# Mainboard.net
KiCad netlist of a schematic drawn in EAGLE
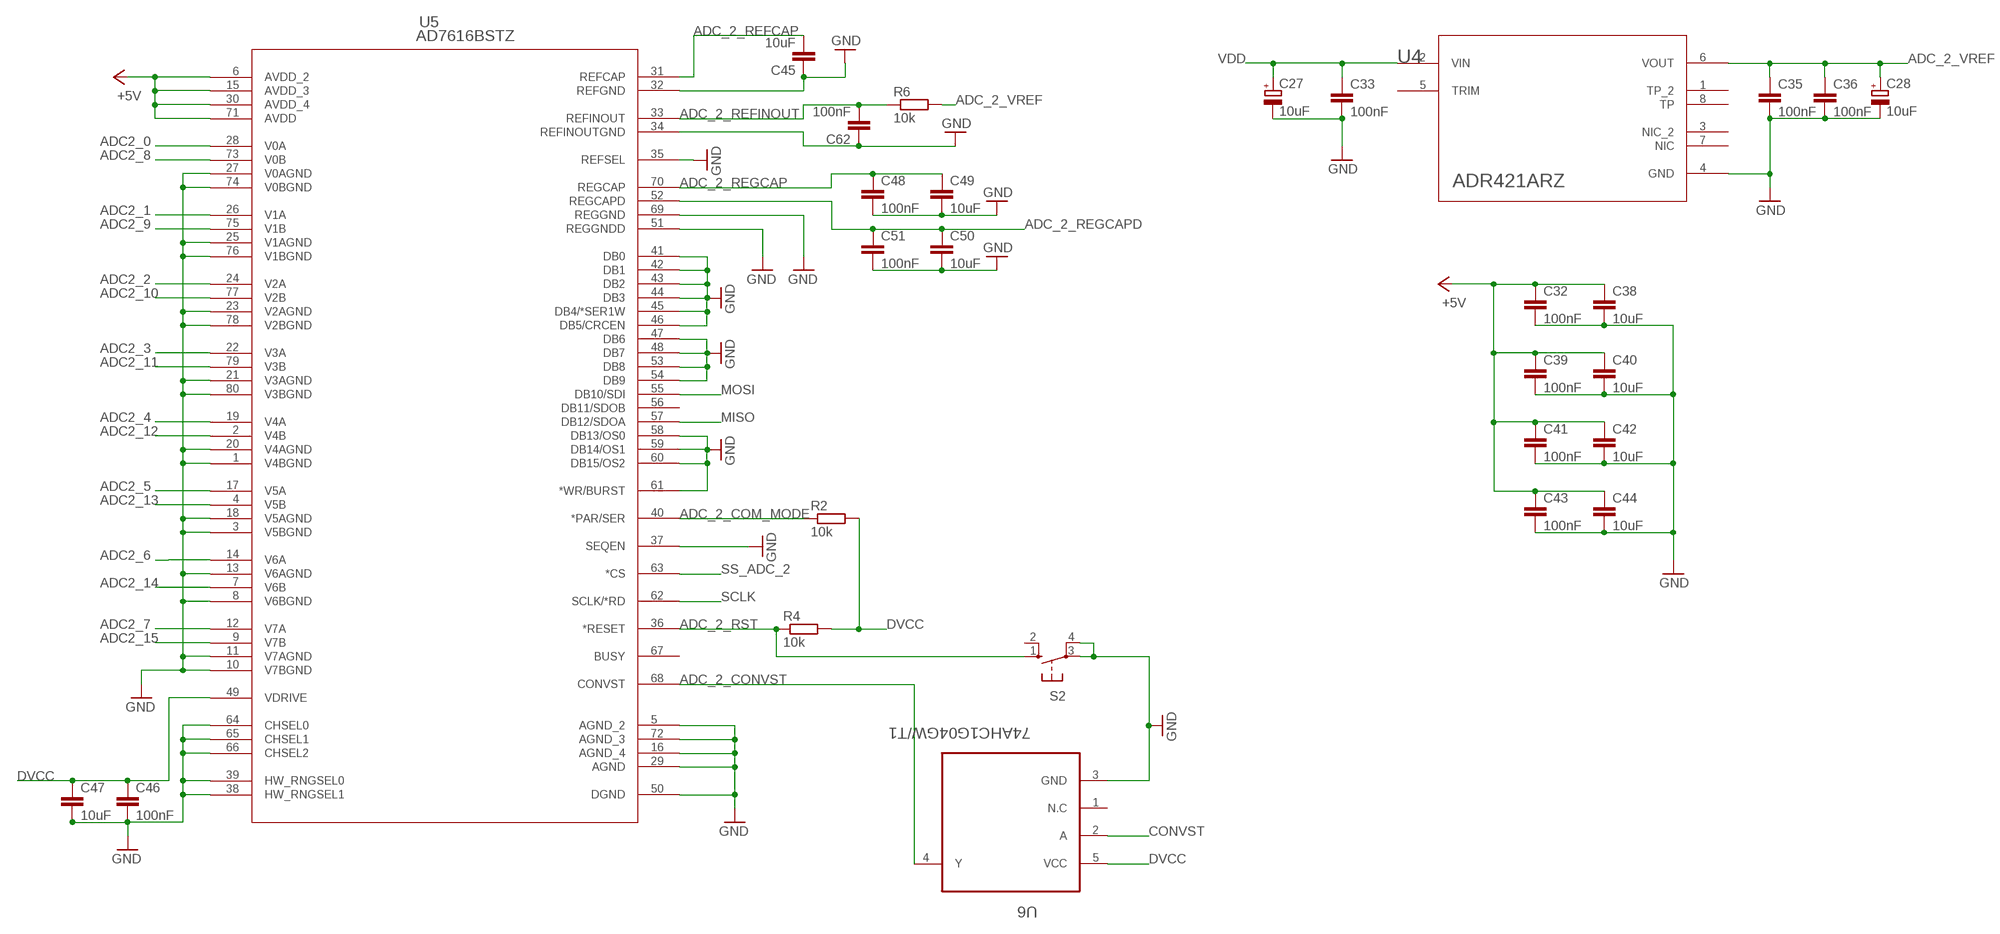
[diagram p0: schematic, sheet 1, part 1 of 2]
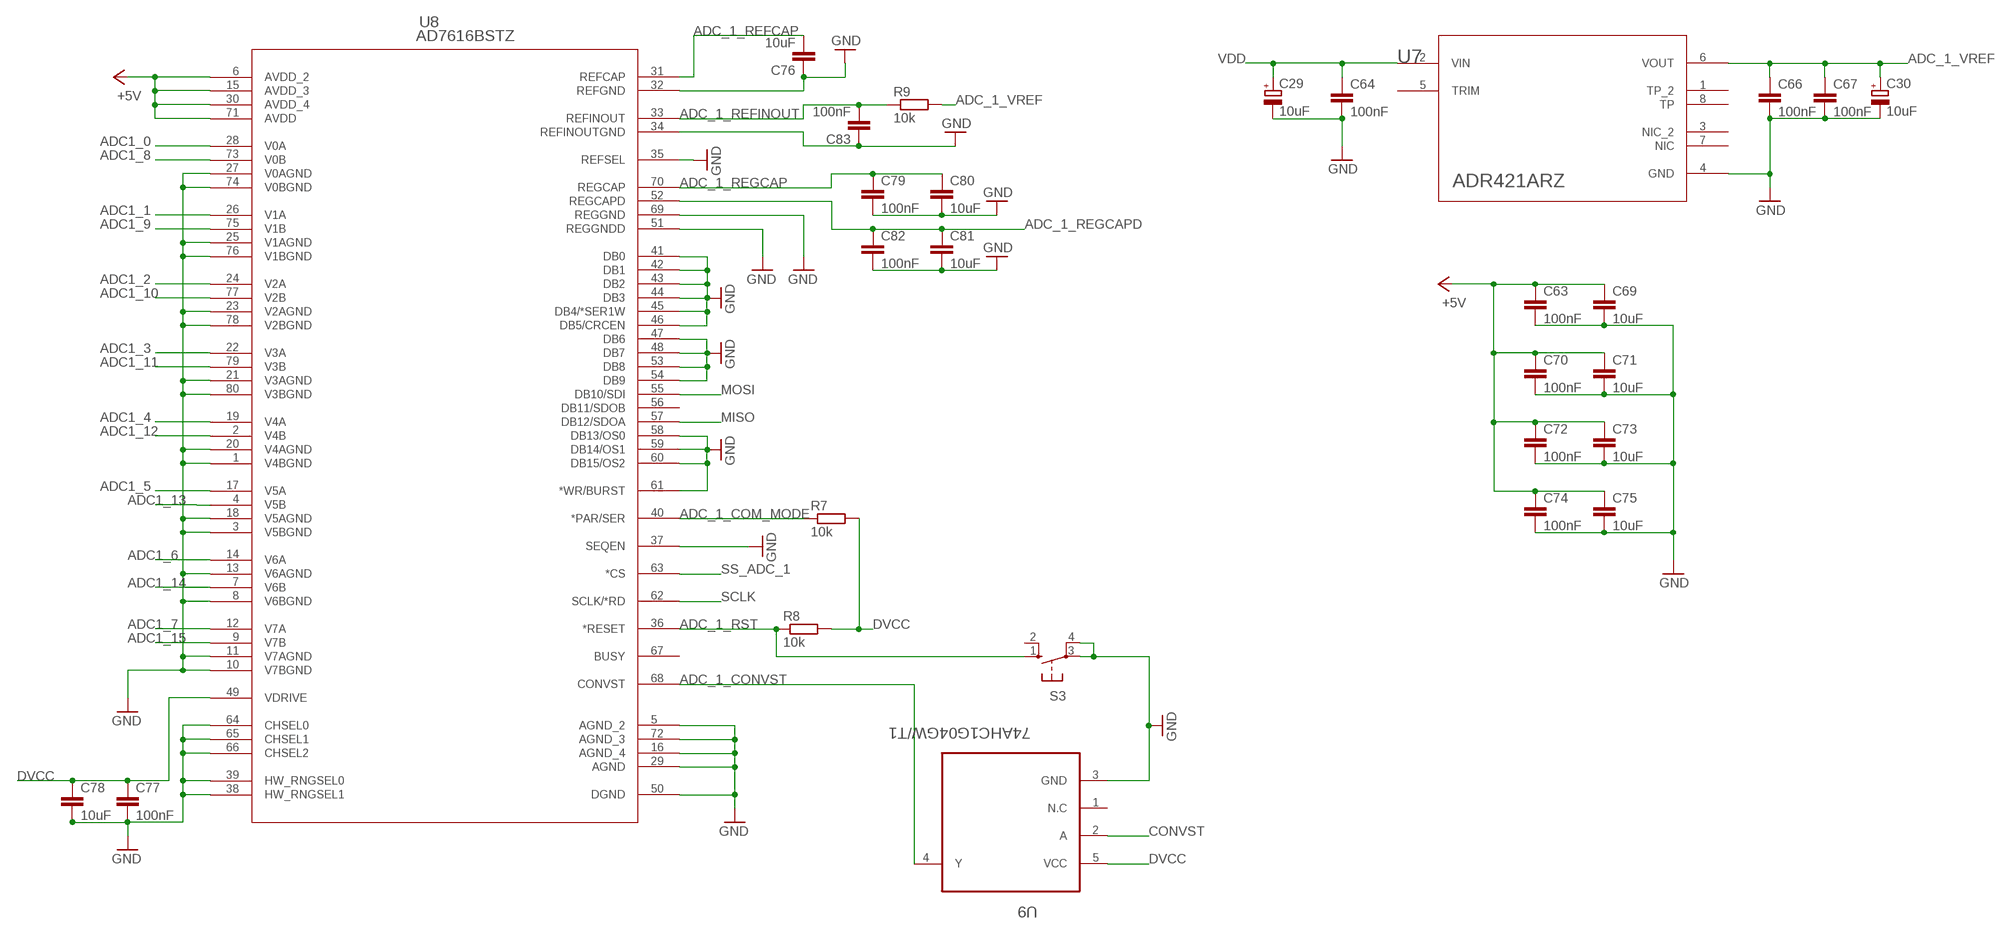
[diagram p1: schematic, sheet 1, part 2 of 2]
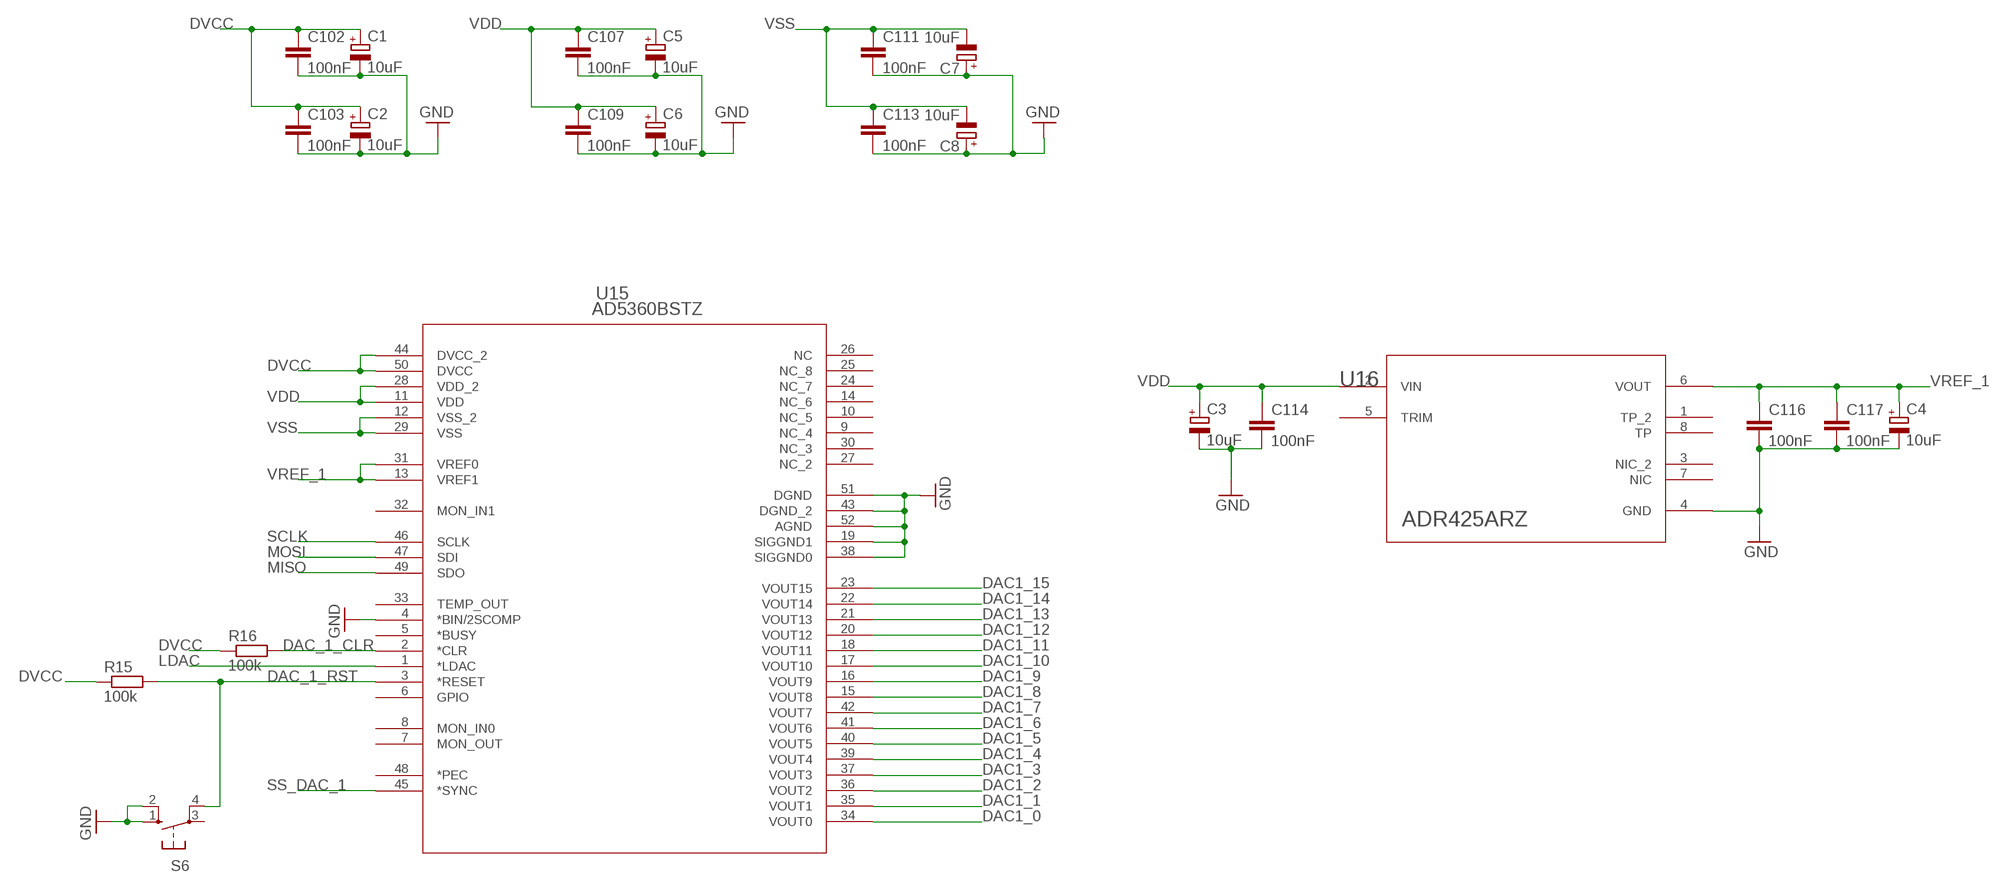
[diagram p2: schematic, sheet 2, part 1 of 2]
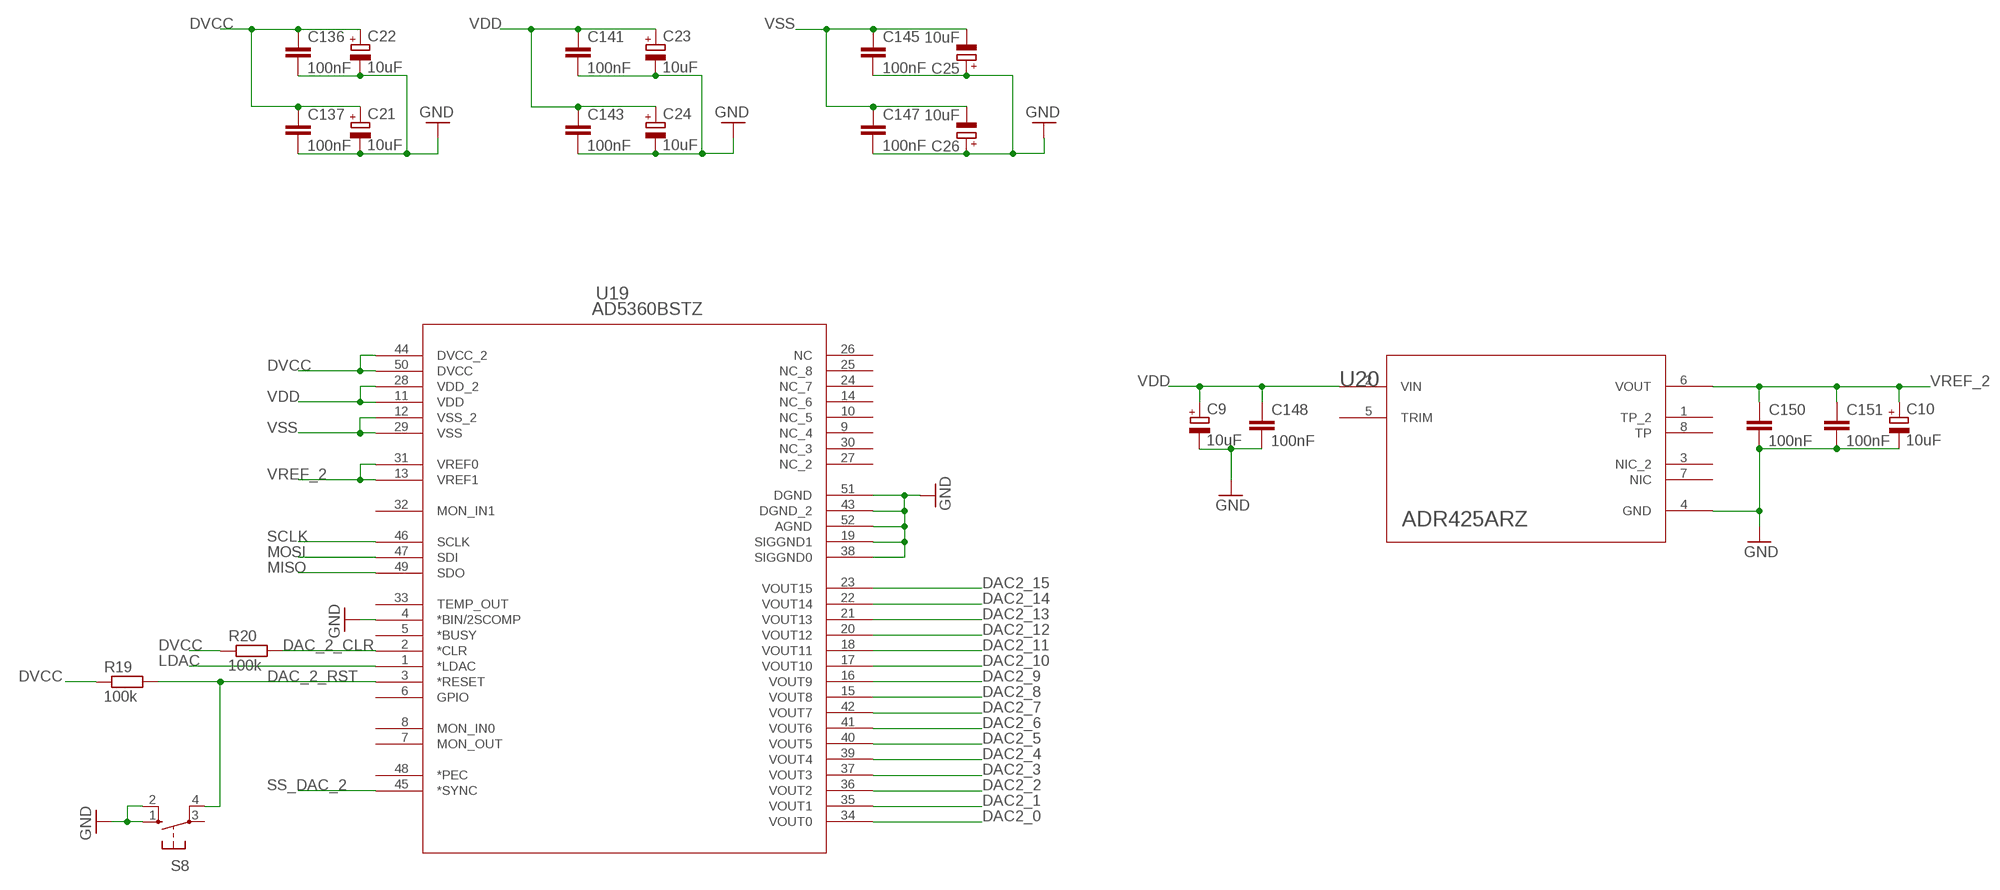
[diagram p3: schematic, sheet 2, part 2 of 2]
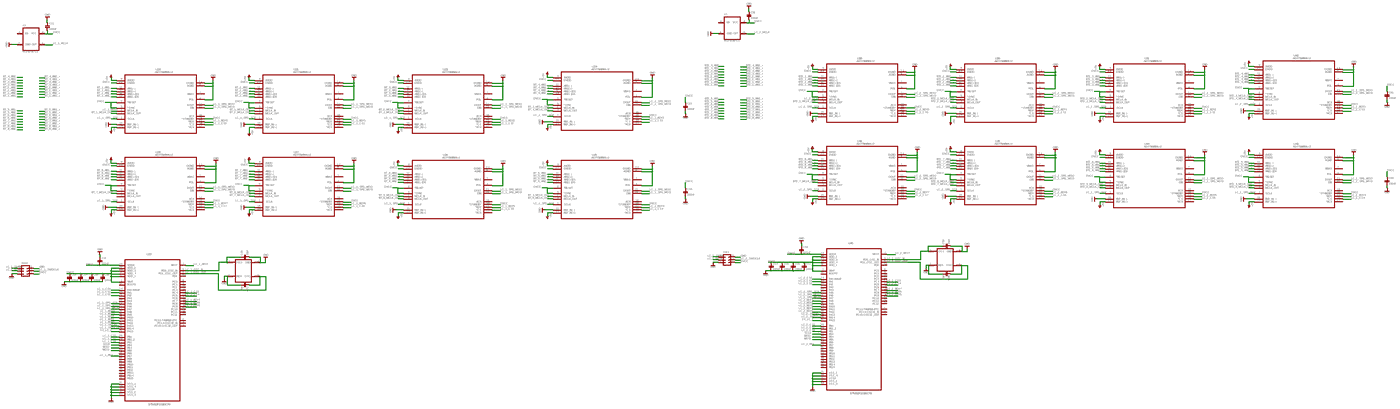
[diagram p4: schematic, sheet 3, overview]
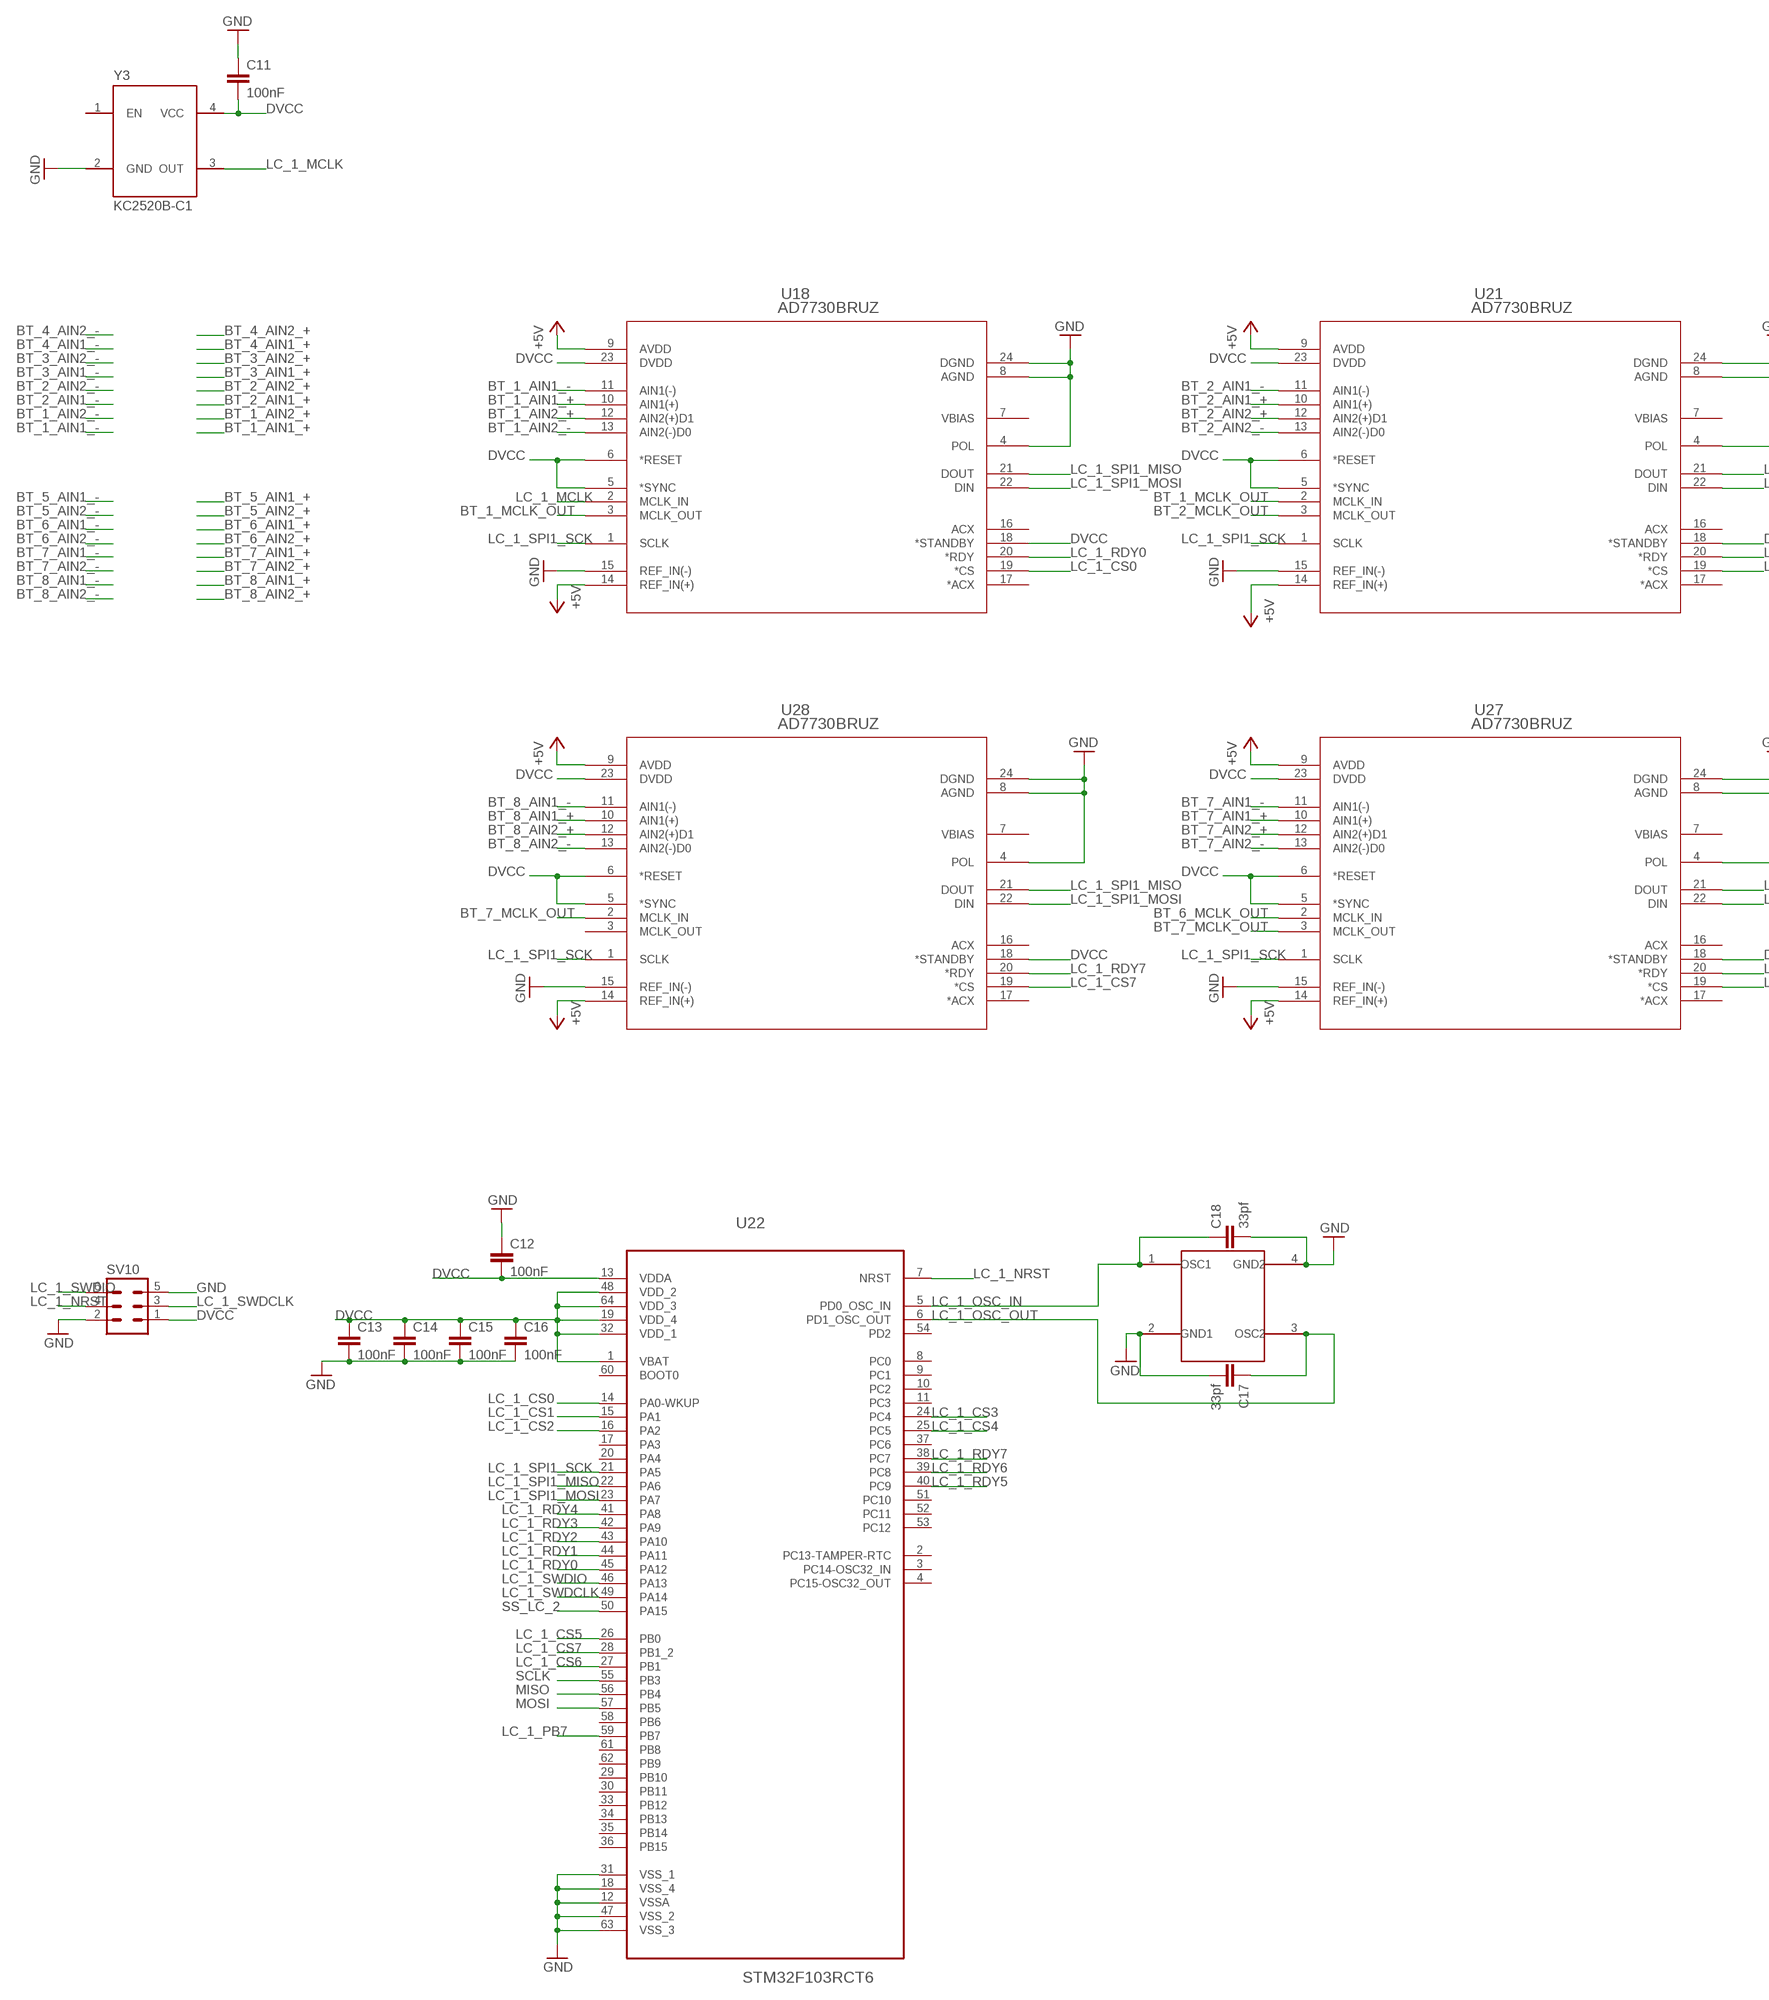
[diagram p5: schematic, sheet 3, part 1 of 4]
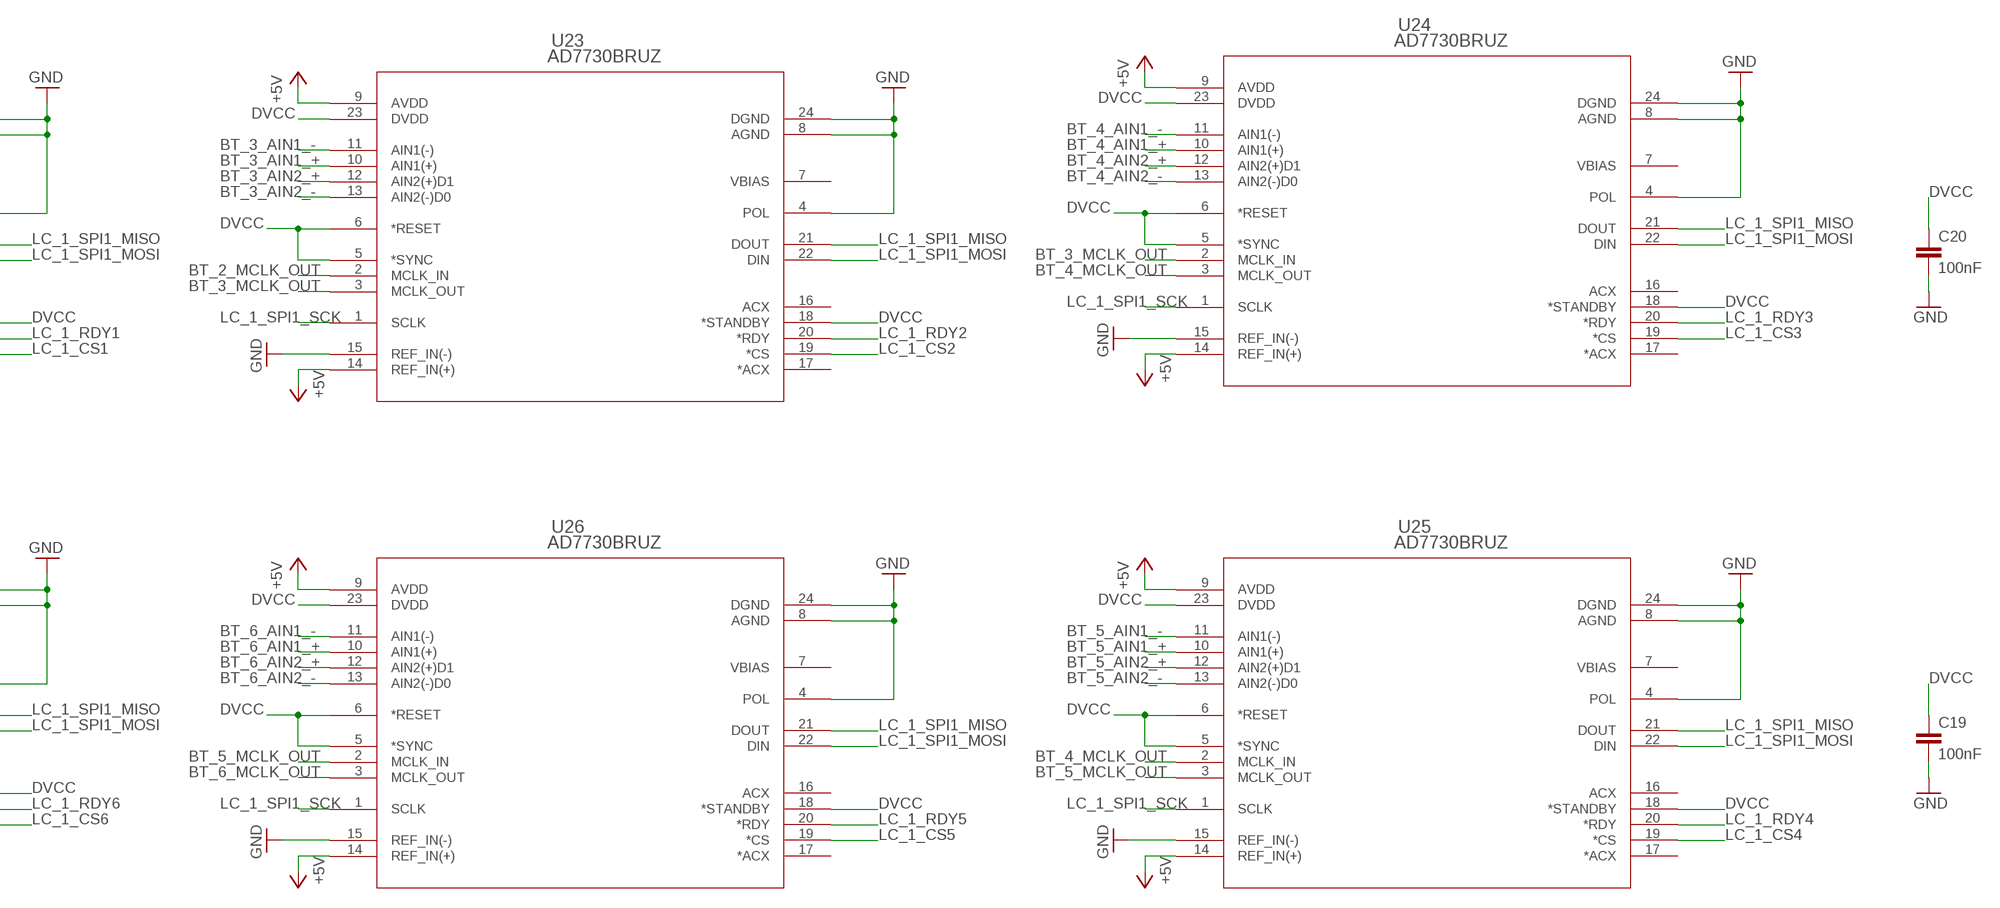
[diagram p6: schematic, sheet 3, part 2 of 4]
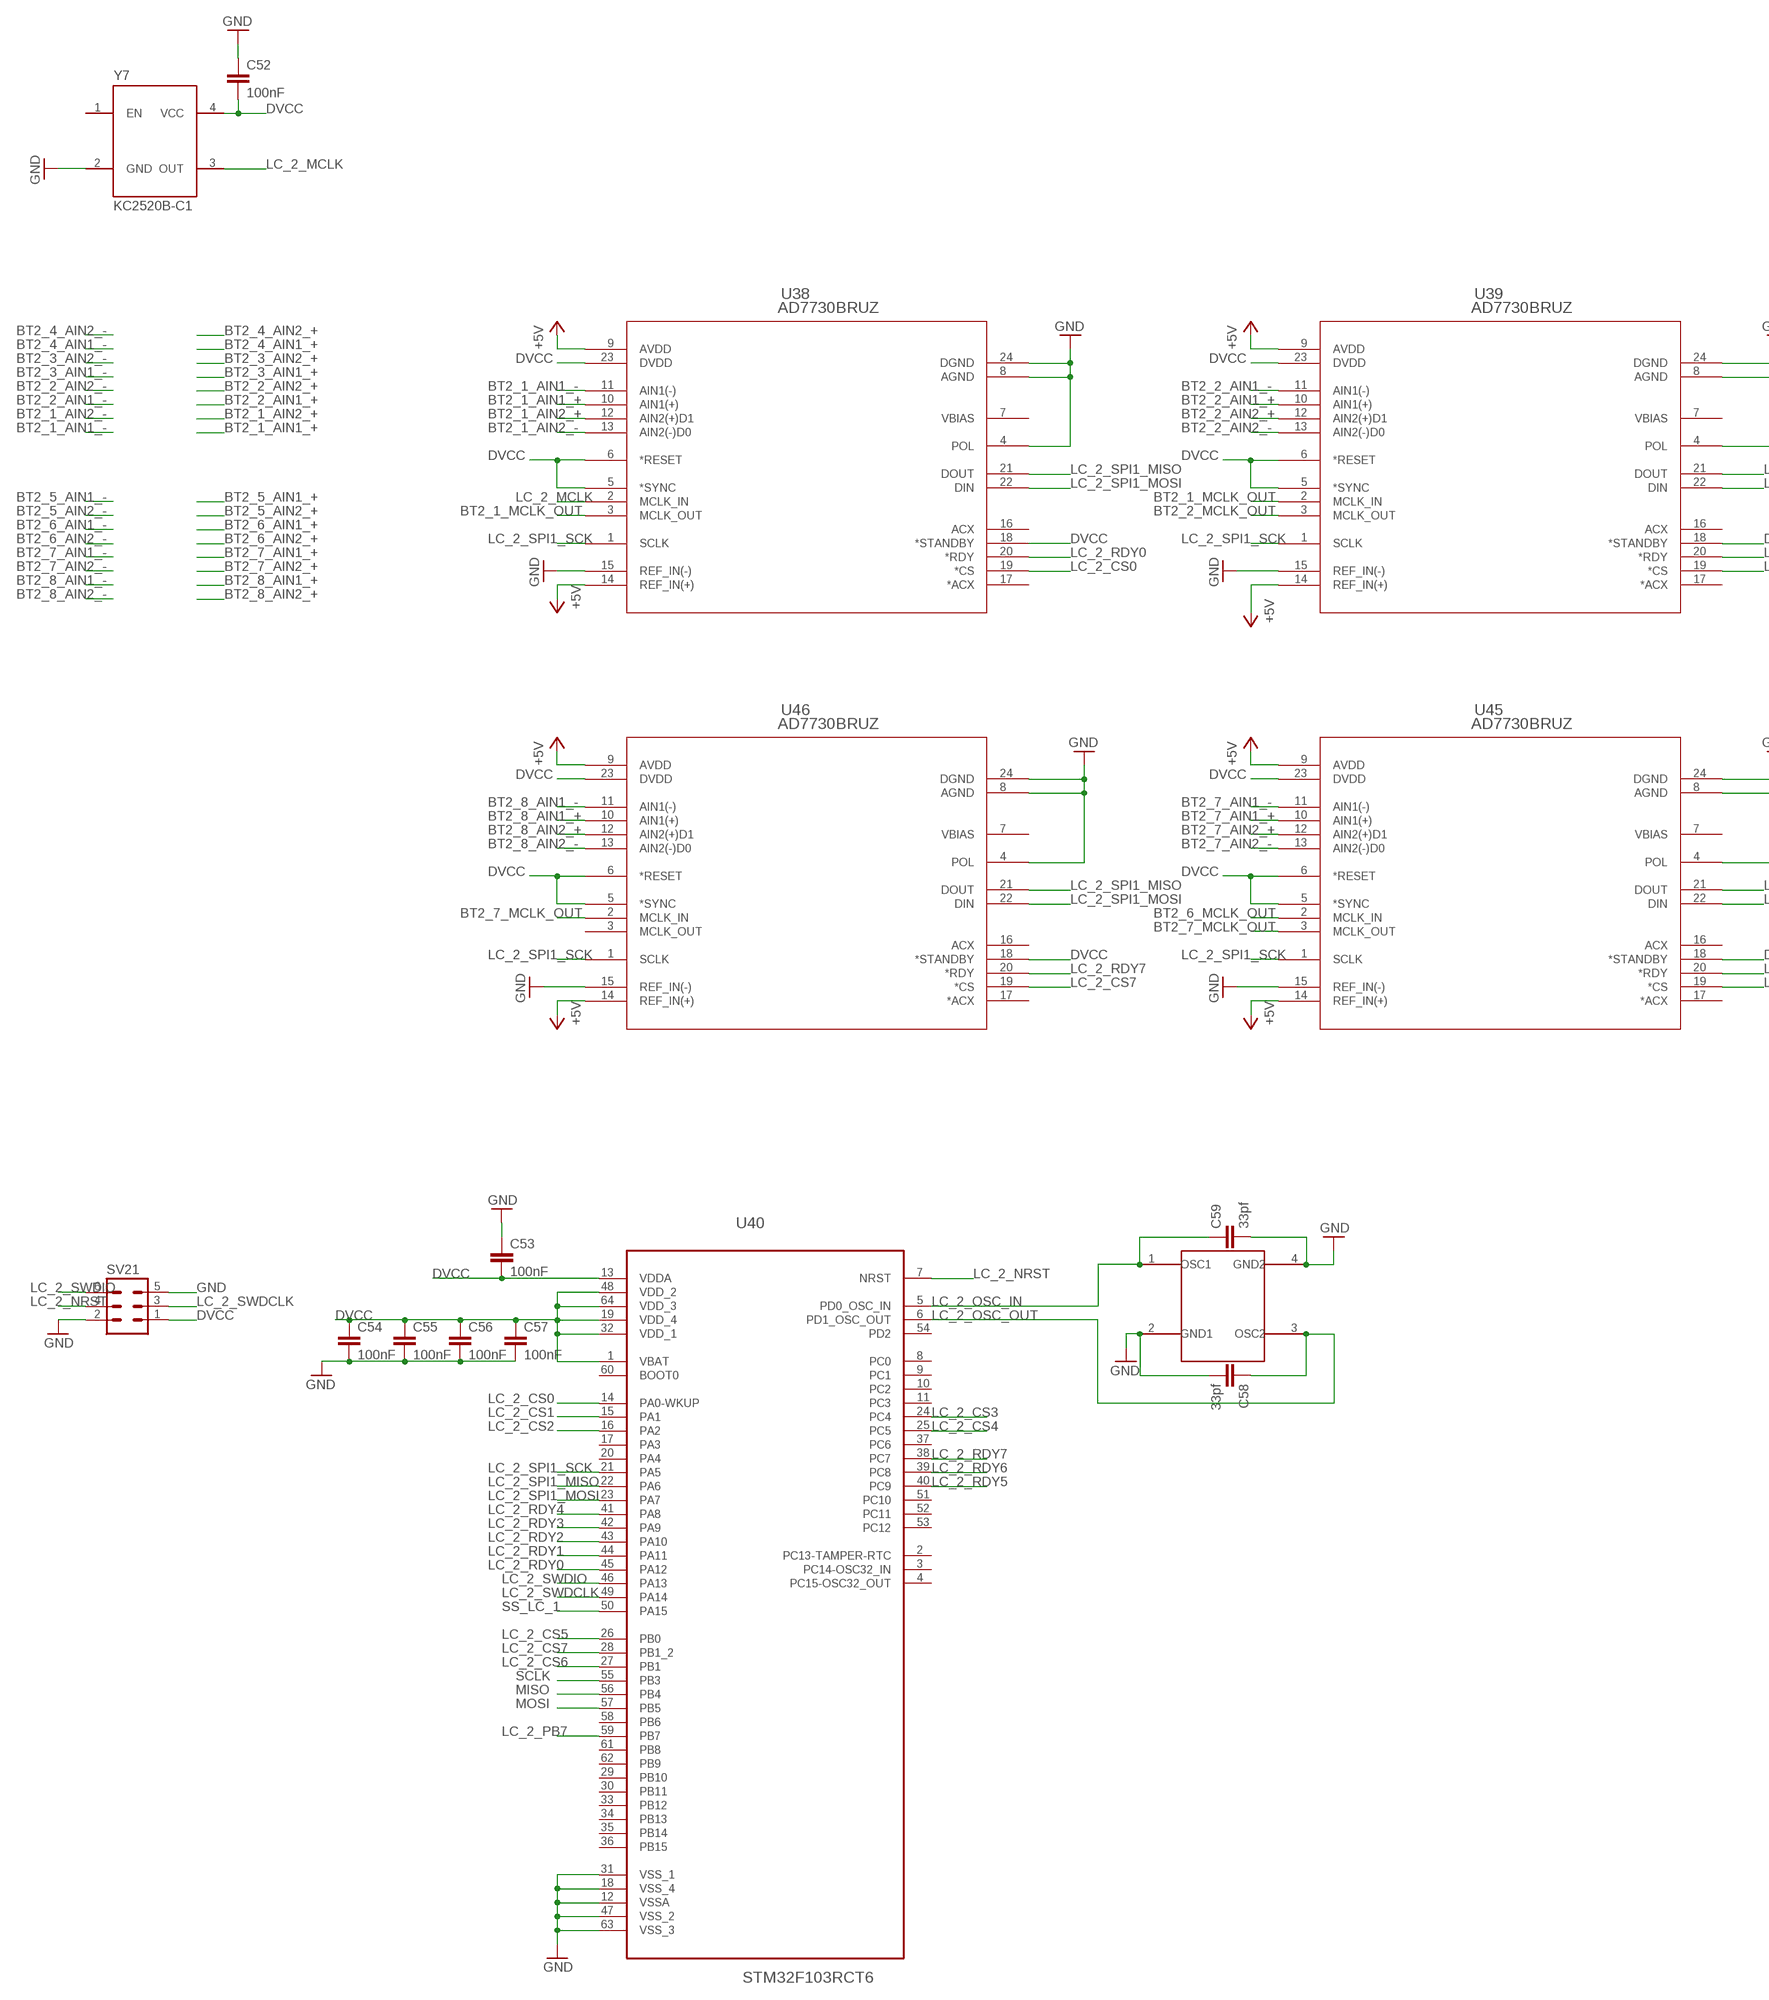
[diagram p7: schematic, sheet 3, part 3 of 4]
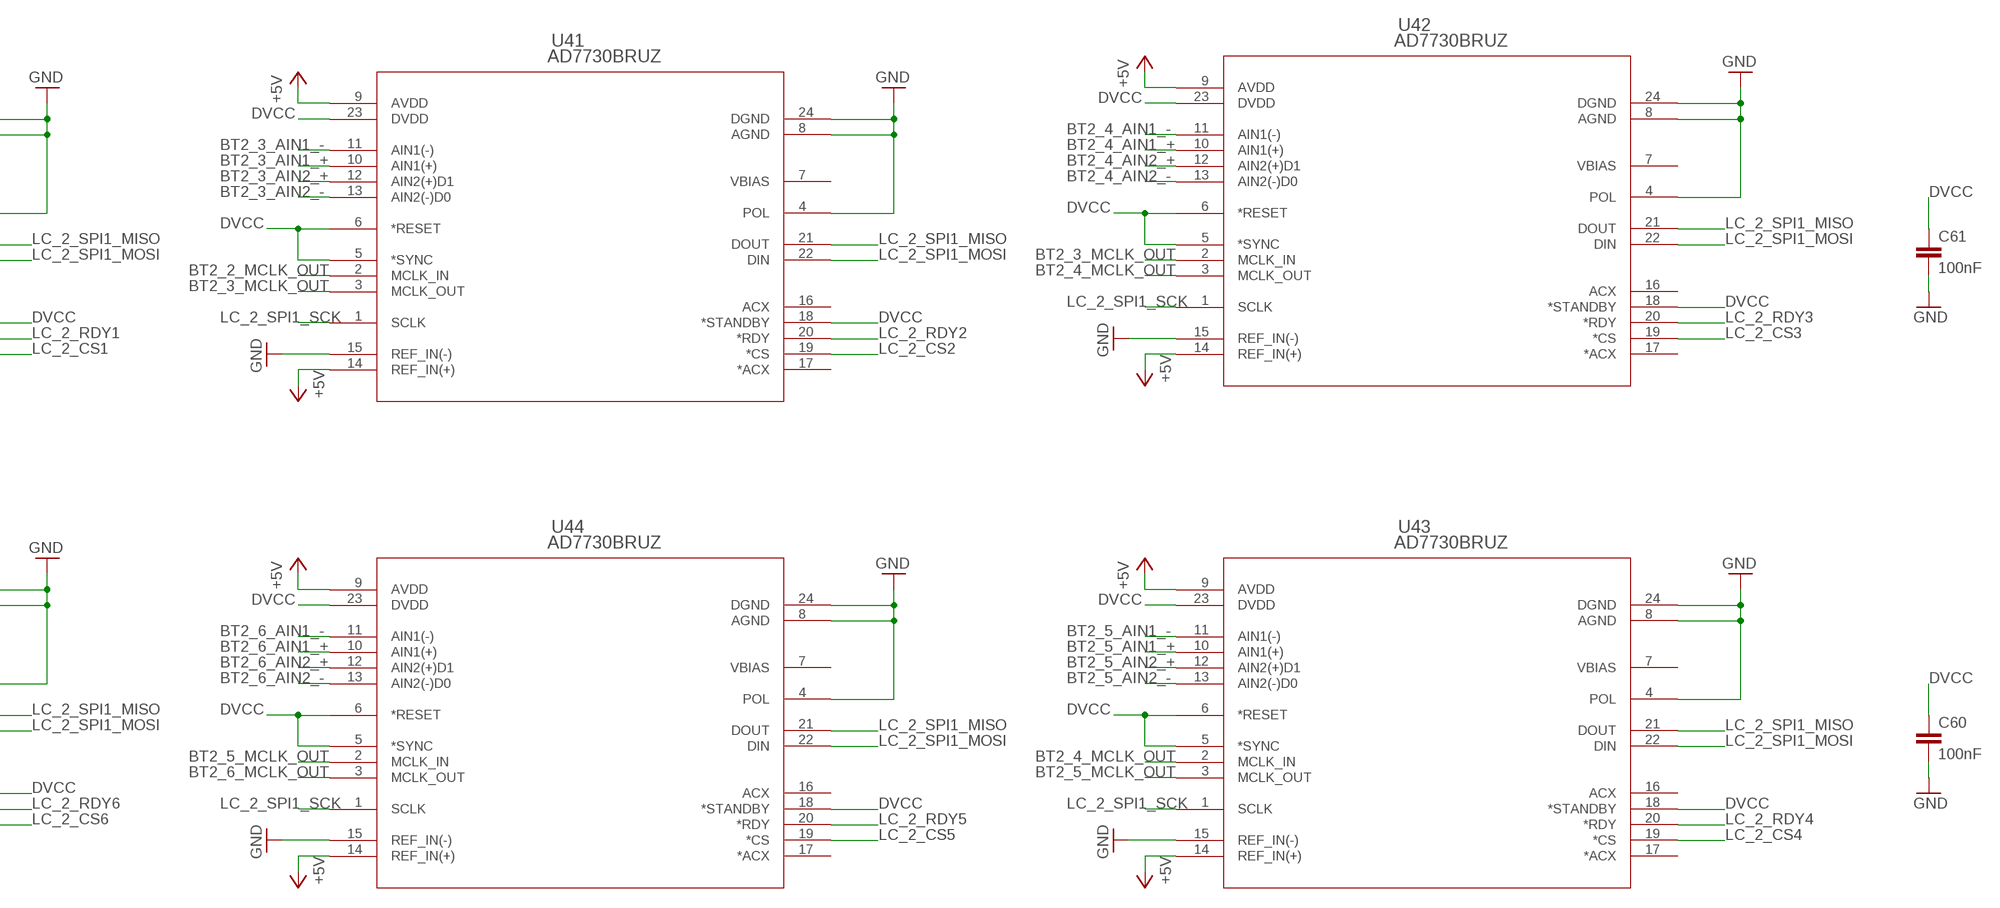
[diagram p8: schematic, sheet 3, part 4 of 4]
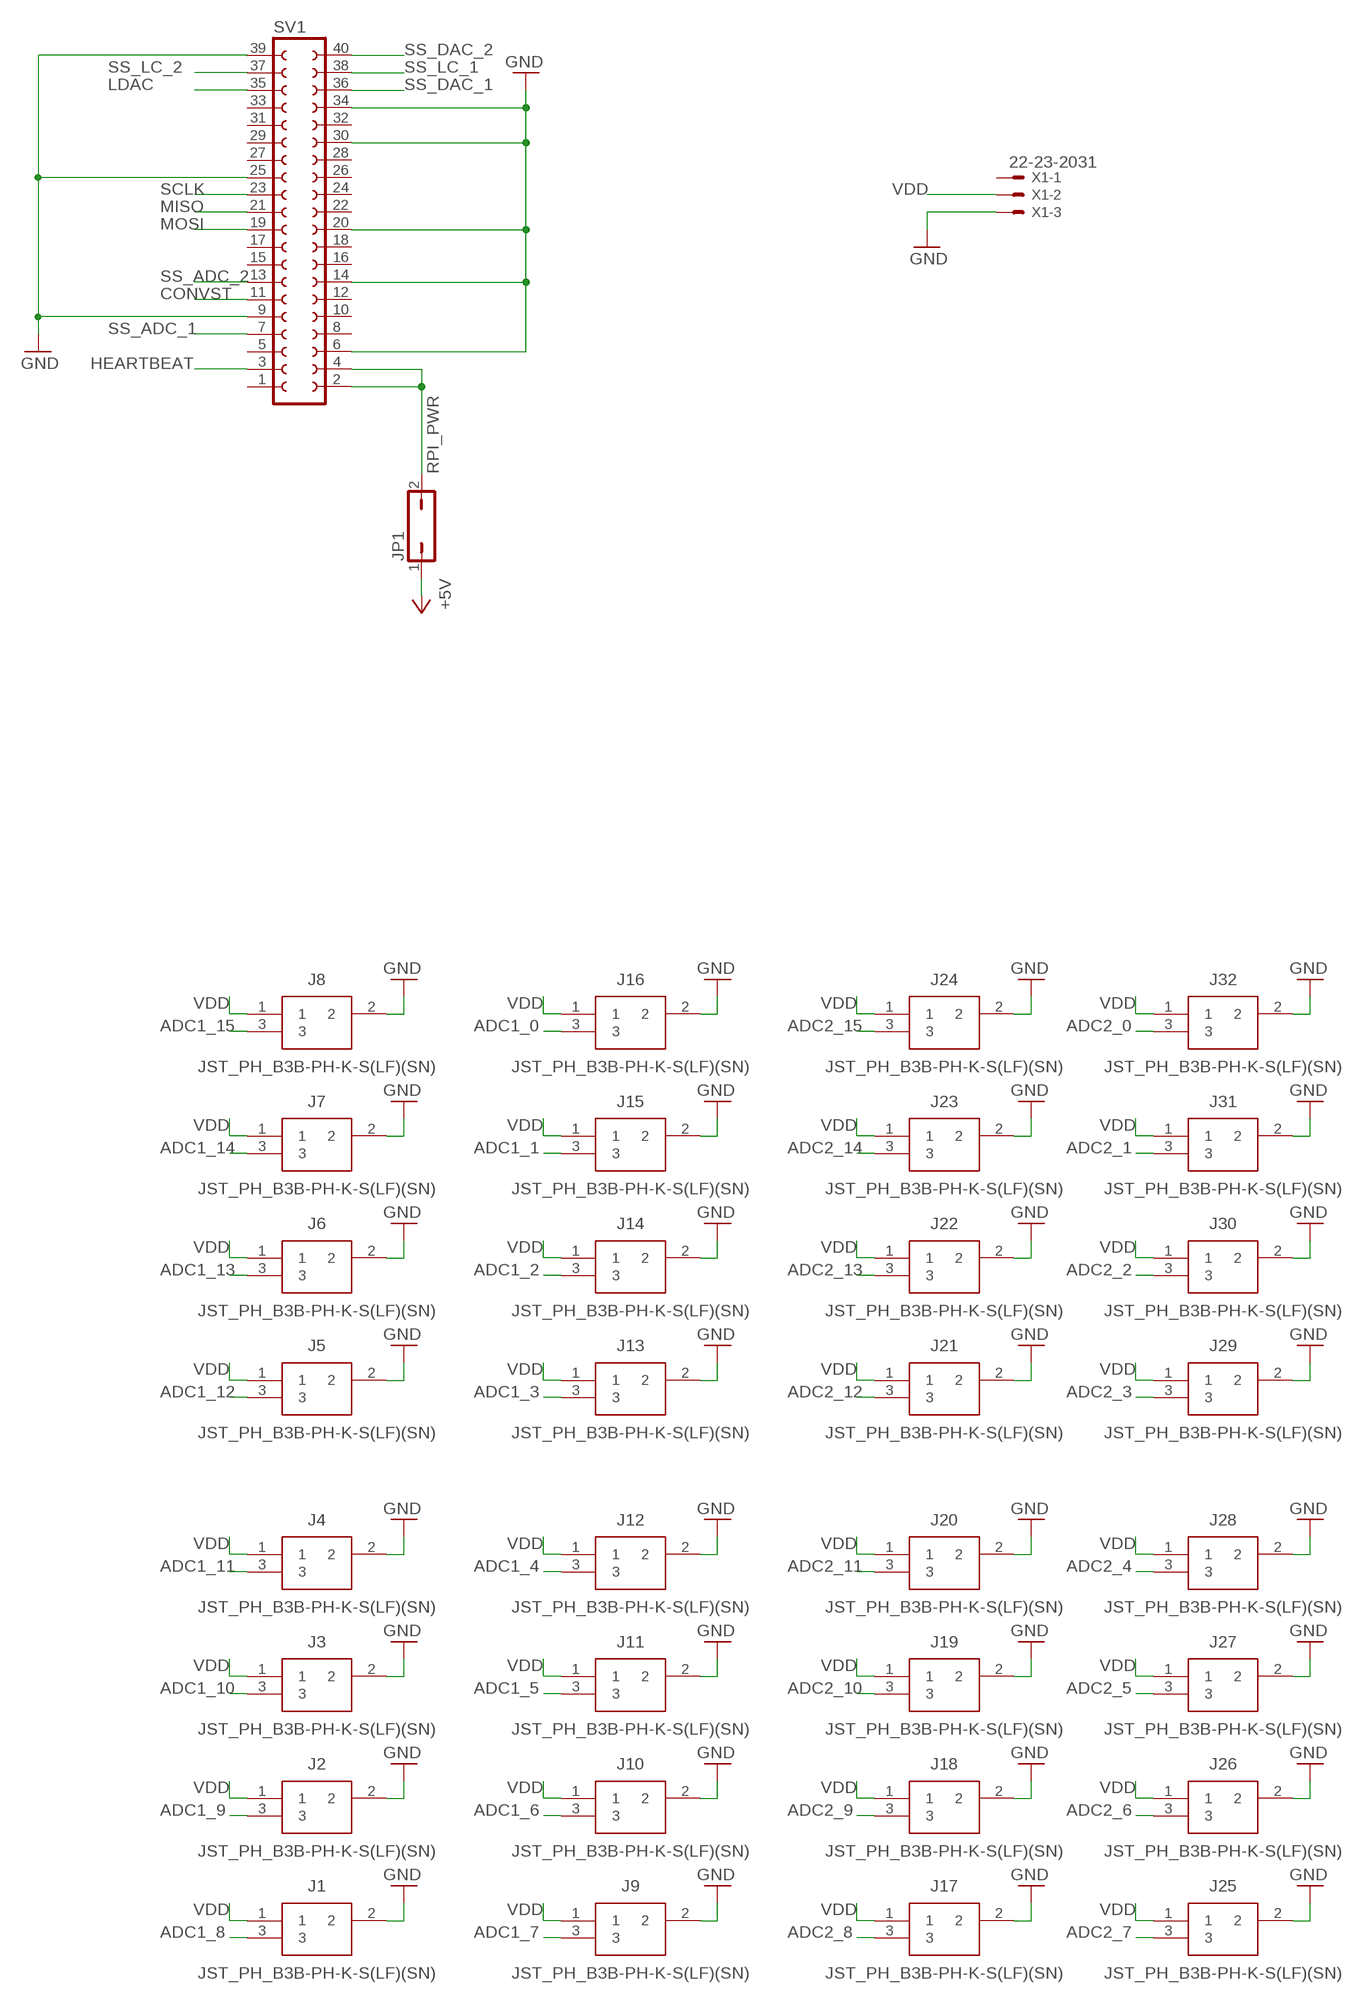
[diagram p9: schematic, sheet 4, part 1 of 2]
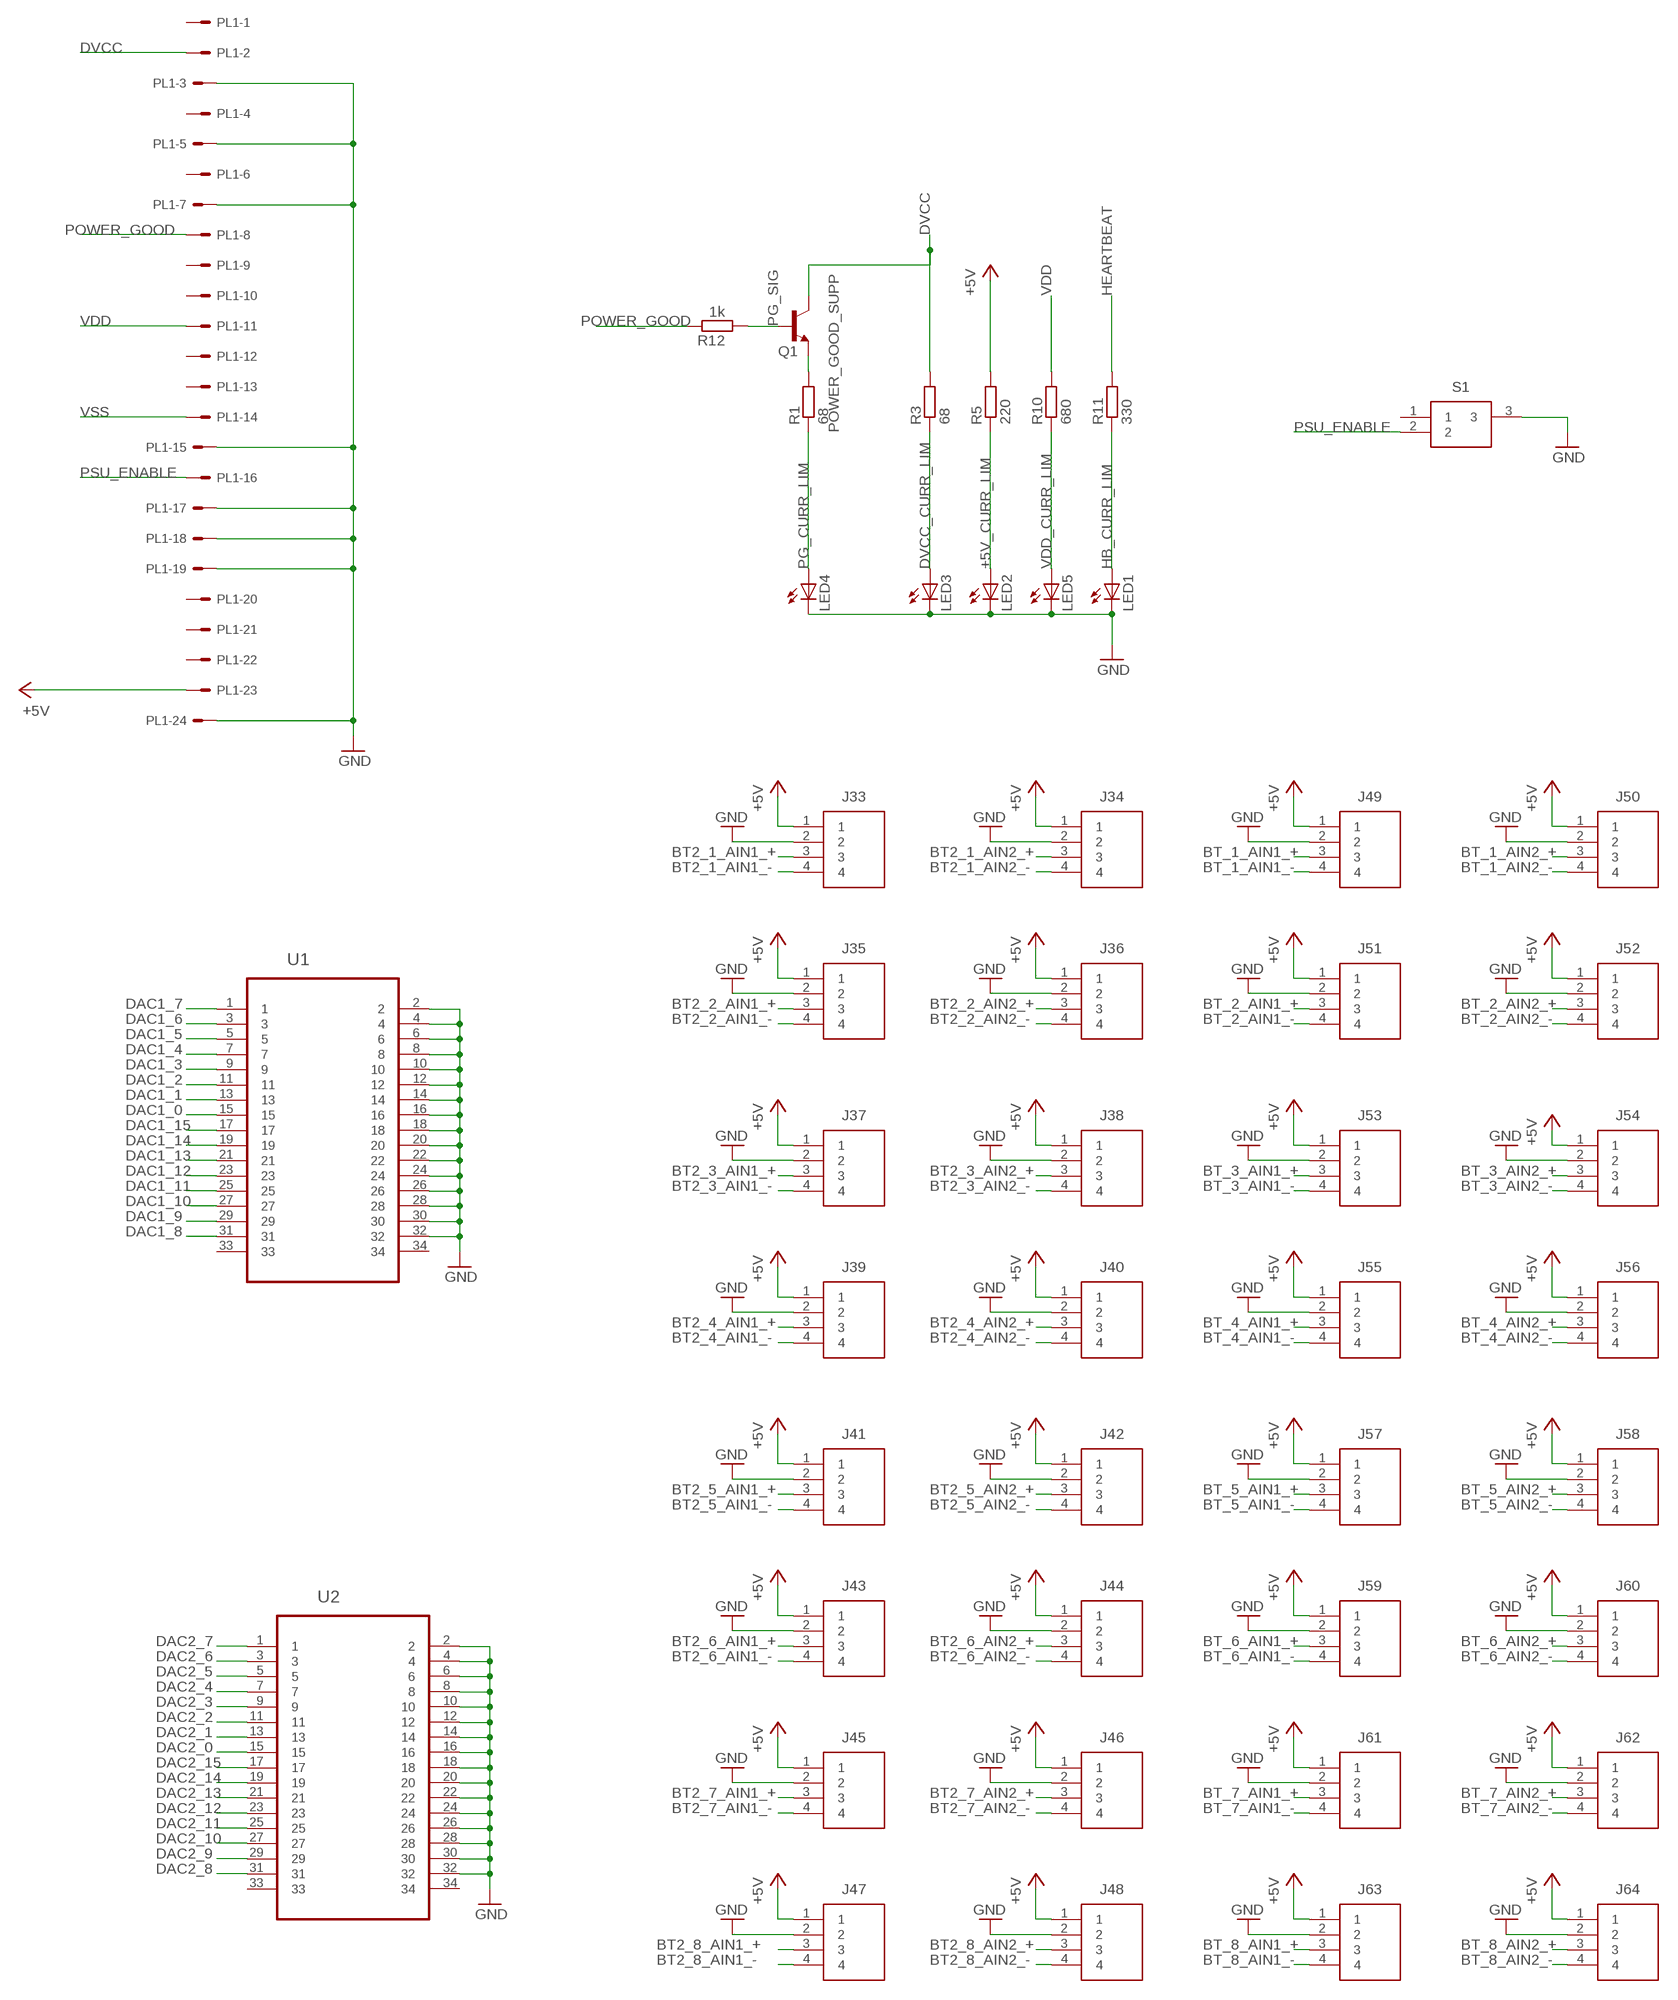
[diagram p10: schematic, sheet 4, part 2 of 2]

(export (version "E")
  (design (tool "Eeschema 10.0.6"))
  (components
    (comp (ref "C1")
      (value "10uF")
      (footprint "eagle-import:SMC_A")
      (libsource (lib "eagle-import") (part "CPOL-EUSMCA"))
    )
    (comp (ref "C2")
      (value "10uF")
      (footprint "eagle-import:SMC_A")
      (libsource (lib "eagle-import") (part "CPOL-EUSMCA"))
    )
    (comp (ref "C3")
      (value "10uF")
      (footprint "eagle-import:SMC_A")
      (libsource (lib "eagle-import") (part "CPOL-EUSMCA"))
    )
    (comp (ref "C4")
      (value "10uF")
      (footprint "eagle-import:SMC_A")
      (libsource (lib "eagle-import") (part "CPOL-EUSMCA"))
    )
    (comp (ref "C5")
      (value "10uF")
      (footprint "eagle-import:SMC_A")
      (libsource (lib "eagle-import") (part "CPOL-EUSMCA"))
    )
    (comp (ref "C6")
      (value "10uF")
      (footprint "eagle-import:SMC_A")
      (libsource (lib "eagle-import") (part "CPOL-EUSMCA"))
    )
    (comp (ref "C7")
      (value "10uF")
      (footprint "eagle-import:SMC_A")
      (libsource (lib "eagle-import") (part "CPOL-EUSMCA"))
    )
    (comp (ref "C8")
      (value "10uF")
      (footprint "eagle-import:SMC_A")
      (libsource (lib "eagle-import") (part "CPOL-EUSMCA"))
    )
    (comp (ref "C9")
      (value "10uF")
      (footprint "eagle-import:SMC_A")
      (libsource (lib "eagle-import") (part "CPOL-EUSMCA"))
    )
    (comp (ref "C10")
      (value "10uF")
      (footprint "eagle-import:SMC_A")
      (libsource (lib "eagle-import") (part "CPOL-EUSMCA"))
    )
    (comp (ref "C21")
      (value "10uF")
      (footprint "eagle-import:SMC_A")
      (libsource (lib "eagle-import") (part "CPOL-EUSMCA"))
    )
    (comp (ref "C22")
      (value "10uF")
      (footprint "eagle-import:SMC_A")
      (libsource (lib "eagle-import") (part "CPOL-EUSMCA"))
    )
    (comp (ref "C23")
      (value "10uF")
      (footprint "eagle-import:SMC_A")
      (libsource (lib "eagle-import") (part "CPOL-EUSMCA"))
    )
    (comp (ref "C24")
      (value "10uF")
      (footprint "eagle-import:SMC_A")
      (libsource (lib "eagle-import") (part "CPOL-EUSMCA"))
    )
    (comp (ref "C25")
      (value "10uF")
      (footprint "eagle-import:SMC_A")
      (libsource (lib "eagle-import") (part "CPOL-EUSMCA"))
    )
    (comp (ref "C26")
      (value "10uF")
      (footprint "eagle-import:SMC_A")
      (libsource (lib "eagle-import") (part "CPOL-EUSMCA"))
    )
    (comp (ref "C102")
      (value "100nF")
      (footprint "eagle-import:C0603")
      (libsource (lib "eagle-import") (part "C-EUC0603"))
    )
    (comp (ref "C103")
      (value "100nF")
      (footprint "eagle-import:C0603")
      (libsource (lib "eagle-import") (part "C-EUC0603"))
    )
    (comp (ref "C107")
      (value "100nF")
      (footprint "eagle-import:C0603")
      (libsource (lib "eagle-import") (part "C-EUC0603"))
    )
    (comp (ref "C109")
      (value "100nF")
      (footprint "eagle-import:C0603")
      (libsource (lib "eagle-import") (part "C-EUC0603"))
    )
    (comp (ref "C111")
      (value "100nF")
      (footprint "eagle-import:C0603")
      (libsource (lib "eagle-import") (part "C-EUC0603"))
    )
    (comp (ref "C113")
      (value "100nF")
      (footprint "eagle-import:C0603")
      (libsource (lib "eagle-import") (part "C-EUC0603"))
    )
    (comp (ref "C114")
      (value "100nF")
      (footprint "eagle-import:C0603")
      (libsource (lib "eagle-import") (part "C-EUC0603"))
    )
    (comp (ref "C116")
      (value "100nF")
      (footprint "eagle-import:C0603")
      (libsource (lib "eagle-import") (part "C-EUC0603"))
    )
    (comp (ref "C117")
      (value "100nF")
      (footprint "eagle-import:C0603")
      (libsource (lib "eagle-import") (part "C-EUC0603"))
    )
    (comp (ref "C136")
      (value "100nF")
      (footprint "eagle-import:C0603")
      (libsource (lib "eagle-import") (part "C-EUC0603"))
    )
    (comp (ref "C137")
      (value "100nF")
      (footprint "eagle-import:C0603")
      (libsource (lib "eagle-import") (part "C-EUC0603"))
    )
    (comp (ref "C141")
      (value "100nF")
      (footprint "eagle-import:C0603")
      (libsource (lib "eagle-import") (part "C-EUC0603"))
    )
    (comp (ref "C143")
      (value "100nF")
      (footprint "eagle-import:C0603")
      (libsource (lib "eagle-import") (part "C-EUC0603"))
    )
    (comp (ref "C145")
      (value "100nF")
      (footprint "eagle-import:C0603")
      (libsource (lib "eagle-import") (part "C-EUC0603"))
    )
    (comp (ref "C147")
      (value "100nF")
      (footprint "eagle-import:C0603")
      (libsource (lib "eagle-import") (part "C-EUC0603"))
    )
    (comp (ref "C148")
      (value "100nF")
      (footprint "eagle-import:C0603")
      (libsource (lib "eagle-import") (part "C-EUC0603"))
    )
    (comp (ref "C150")
      (value "100nF")
      (footprint "eagle-import:C0603")
      (libsource (lib "eagle-import") (part "C-EUC0603"))
    )
    (comp (ref "C151")
      (value "100nF")
      (footprint "eagle-import:C0603")
      (libsource (lib "eagle-import") (part "C-EUC0603"))
    )
    (comp (ref "R15")
      (value "100k")
      (footprint "eagle-import:R0603")
      (libsource (lib "eagle-import") (part "R-EU_R0603"))
    )
    (comp (ref "R16")
      (value "100k")
      (footprint "eagle-import:R0603")
      (libsource (lib "eagle-import") (part "R-EU_R0603"))
    )
    (comp (ref "R19")
      (value "100k")
      (footprint "eagle-import:R0603")
      (libsource (lib "eagle-import") (part "R-EU_R0603"))
    )
    (comp (ref "R20")
      (value "100k")
      (footprint "eagle-import:R0603")
      (libsource (lib "eagle-import") (part "R-EU_R0603"))
    )
    (comp (ref "S6")
      (value "10-XX")
      (footprint "eagle-import:B3F-10XX")
      (fields (field (name "MPN") "B3F-1000"))
      (libsource (lib "eagle-import") (part "10-XX"))
    )
    (comp (ref "S8")
      (value "10-XX")
      (footprint "eagle-import:B3F-10XX")
      (fields (field (name "MPN") "B3F-1000"))
      (libsource (lib "eagle-import") (part "10-XX"))
    )
    (comp (ref "U15")
      (value "AD5360BSTZ")
      (footprint "eagle-import:ST_52")
      (libsource (lib "eagle-import") (part "AD5360BSTZ"))
    )
    (comp (ref "U16")
      (value "ADR425ARZ")
      (footprint "eagle-import:R_8")
      (fields (field (name "MANUFACTURER_PART_NUMBER") "ADR423ARZ"))
      (libsource (lib "eagle-import") (part "ADR423ARZ"))
    )
    (comp (ref "U19")
      (value "AD5360BSTZ")
      (footprint "eagle-import:ST_52")
      (libsource (lib "eagle-import") (part "AD5360BSTZ"))
    )
    (comp (ref "U20")
      (value "ADR425ARZ")
      (footprint "eagle-import:R_8")
      (fields (field (name "MANUFACTURER_PART_NUMBER") "ADR423ARZ"))
      (libsource (lib "eagle-import") (part "ADR423ARZ"))
    )
    (comp (ref "C11")
      (value "100nF")
      (footprint "eagle-import:C0603")
      (libsource (lib "eagle-import") (part "C-EUC0603"))
    )
    (comp (ref "C12")
      (value "100nF")
      (footprint "eagle-import:C0603")
      (libsource (lib "eagle-import") (part "C-EUC0603"))
    )
    (comp (ref "C13")
      (value "100nF")
      (footprint "eagle-import:C0603")
      (libsource (lib "eagle-import") (part "C-EUC0603"))
    )
    (comp (ref "C14")
      (value "100nF")
      (footprint "eagle-import:C0603")
      (libsource (lib "eagle-import") (part "C-EUC0603"))
    )
    (comp (ref "C15")
      (value "100nF")
      (footprint "eagle-import:C0603")
      (libsource (lib "eagle-import") (part "C-EUC0603"))
    )
    (comp (ref "C16")
      (value "100nF")
      (footprint "eagle-import:C0603")
      (libsource (lib "eagle-import") (part "C-EUC0603"))
    )
    (comp (ref "C17")
      (value "33pf")
      (footprint "eagle-import:C0603")
      (libsource (lib "eagle-import") (part "C-EUC0603"))
    )
    (comp (ref "C18")
      (value "33pf")
      (footprint "eagle-import:C0603")
      (libsource (lib "eagle-import") (part "C-EUC0603"))
    )
    (comp (ref "C19")
      (value "100nF")
      (footprint "eagle-import:C0603")
      (libsource (lib "eagle-import") (part "C-EUC0603"))
    )
    (comp (ref "C20")
      (value "100nF")
      (footprint "eagle-import:C0603")
      (libsource (lib "eagle-import") (part "C-EUC0603"))
    )
    (comp (ref "C52")
      (value "100nF")
      (footprint "eagle-import:C0603")
      (libsource (lib "eagle-import") (part "C-EUC0603"))
    )
    (comp (ref "C53")
      (value "100nF")
      (footprint "eagle-import:C0603")
      (libsource (lib "eagle-import") (part "C-EUC0603"))
    )
    (comp (ref "C54")
      (value "100nF")
      (footprint "eagle-import:C0603")
      (libsource (lib "eagle-import") (part "C-EUC0603"))
    )
    (comp (ref "C55")
      (value "100nF")
      (footprint "eagle-import:C0603")
      (libsource (lib "eagle-import") (part "C-EUC0603"))
    )
    (comp (ref "C56")
      (value "100nF")
      (footprint "eagle-import:C0603")
      (libsource (lib "eagle-import") (part "C-EUC0603"))
    )
    (comp (ref "C57")
      (value "100nF")
      (footprint "eagle-import:C0603")
      (libsource (lib "eagle-import") (part "C-EUC0603"))
    )
    (comp (ref "C58")
      (value "33pf")
      (footprint "eagle-import:C0603")
      (libsource (lib "eagle-import") (part "C-EUC0603"))
    )
    (comp (ref "C59")
      (value "33pf")
      (footprint "eagle-import:C0603")
      (libsource (lib "eagle-import") (part "C-EUC0603"))
    )
    (comp (ref "C60")
      (value "100nF")
      (footprint "eagle-import:C0603")
      (libsource (lib "eagle-import") (part "C-EUC0603"))
    )
    (comp (ref "C61")
      (value "100nF")
      (footprint "eagle-import:C0603")
      (libsource (lib "eagle-import") (part "C-EUC0603"))
    )
    (comp (ref "SV10")
      (value "MA03-2")
      (footprint "eagle-import:MA03-2")
      (libsource (lib "eagle-import") (part "MA03-2"))
    )
    (comp (ref "SV21")
      (value "MA03-2")
      (footprint "eagle-import:MA03-2")
      (libsource (lib "eagle-import") (part "MA03-2"))
    )
    (comp (ref "U18")
      (value "AD7730BRUZ")
      (footprint "eagle-import:RU_24")
      (libsource (lib "eagle-import") (part "AD7730BRUZ"))
    )
    (comp (ref "U21")
      (value "AD7730BRUZ")
      (footprint "eagle-import:RU_24")
      (libsource (lib "eagle-import") (part "AD7730BRUZ"))
    )
    (comp (ref "U22")
      (value "STM32F103RCT6")
      (footprint "eagle-import:QFP50P1200X1200X160-64N")
      (libsource (lib "eagle-import") (part "STM32F103RCT6"))
    )
    (comp (ref "U23")
      (value "AD7730BRUZ")
      (footprint "eagle-import:RU_24")
      (libsource (lib "eagle-import") (part "AD7730BRUZ"))
    )
    (comp (ref "U24")
      (value "AD7730BRUZ")
      (footprint "eagle-import:RU_24")
      (libsource (lib "eagle-import") (part "AD7730BRUZ"))
    )
    (comp (ref "U25")
      (value "AD7730BRUZ")
      (footprint "eagle-import:RU_24")
      (libsource (lib "eagle-import") (part "AD7730BRUZ"))
    )
    (comp (ref "U26")
      (value "AD7730BRUZ")
      (footprint "eagle-import:RU_24")
      (libsource (lib "eagle-import") (part "AD7730BRUZ"))
    )
    (comp (ref "U27")
      (value "AD7730BRUZ")
      (footprint "eagle-import:RU_24")
      (libsource (lib "eagle-import") (part "AD7730BRUZ"))
    )
    (comp (ref "U28")
      (value "AD7730BRUZ")
      (footprint "eagle-import:RU_24")
      (libsource (lib "eagle-import") (part "AD7730BRUZ"))
    )
    (comp (ref "U38")
      (value "AD7730BRUZ")
      (footprint "eagle-import:RU_24")
      (libsource (lib "eagle-import") (part "AD7730BRUZ"))
    )
    (comp (ref "U39")
      (value "AD7730BRUZ")
      (footprint "eagle-import:RU_24")
      (libsource (lib "eagle-import") (part "AD7730BRUZ"))
    )
    (comp (ref "U40")
      (value "STM32F103RCT6")
      (footprint "eagle-import:QFP50P1200X1200X160-64N")
      (libsource (lib "eagle-import") (part "STM32F103RCT6"))
    )
    (comp (ref "U41")
      (value "AD7730BRUZ")
      (footprint "eagle-import:RU_24")
      (libsource (lib "eagle-import") (part "AD7730BRUZ"))
    )
    (comp (ref "U42")
      (value "AD7730BRUZ")
      (footprint "eagle-import:RU_24")
      (libsource (lib "eagle-import") (part "AD7730BRUZ"))
    )
    (comp (ref "U43")
      (value "AD7730BRUZ")
      (footprint "eagle-import:RU_24")
      (libsource (lib "eagle-import") (part "AD7730BRUZ"))
    )
    (comp (ref "U44")
      (value "AD7730BRUZ")
      (footprint "eagle-import:RU_24")
      (libsource (lib "eagle-import") (part "AD7730BRUZ"))
    )
    (comp (ref "U45")
      (value "AD7730BRUZ")
      (footprint "eagle-import:RU_24")
      (libsource (lib "eagle-import") (part "AD7730BRUZ"))
    )
    (comp (ref "U46")
      (value "AD7730BRUZ")
      (footprint "eagle-import:RU_24")
      (libsource (lib "eagle-import") (part "AD7730BRUZ"))
    )
    (comp (ref "Y3")
      (value "KC2520B-C1")
      (footprint "eagle-import:KC2520B-C1")
      (libsource (lib "eagle-import") (part "KC2520B-C1"))
    )
    (comp (ref "Y4")
      (value "ABM3B")
      (footprint "eagle-import:ABM3B")
      (libsource (lib "eagle-import") (part "ABM3B"))
    )
    (comp (ref "Y7")
      (value "KC2520B-C1")
      (footprint "eagle-import:KC2520B-C1")
      (libsource (lib "eagle-import") (part "KC2520B-C1"))
    )
    (comp (ref "Y8")
      (value "ABM3B")
      (footprint "eagle-import:ABM3B")
      (libsource (lib "eagle-import") (part "ABM3B"))
    )
    (comp (ref "C27")
      (value "10uF")
      (footprint "eagle-import:SMC_A")
      (libsource (lib "eagle-import") (part "CPOL-EUSMCA"))
    )
    (comp (ref "C28")
      (value "10uF")
      (footprint "eagle-import:SMC_A")
      (libsource (lib "eagle-import") (part "CPOL-EUSMCA"))
    )
    (comp (ref "C29")
      (value "10uF")
      (footprint "eagle-import:SMC_A")
      (libsource (lib "eagle-import") (part "CPOL-EUSMCA"))
    )
    (comp (ref "C30")
      (value "10uF")
      (footprint "eagle-import:SMC_A")
      (libsource (lib "eagle-import") (part "CPOL-EUSMCA"))
    )
    (comp (ref "C32")
      (value "100nF")
      (footprint "eagle-import:C0603")
      (libsource (lib "eagle-import") (part "C-EUC0603"))
    )
    (comp (ref "C33")
      (value "100nF")
      (footprint "eagle-import:C0603")
      (libsource (lib "eagle-import") (part "C-EUC0603"))
    )
    (comp (ref "C35")
      (value "100nF")
      (footprint "eagle-import:C0603")
      (libsource (lib "eagle-import") (part "C-EUC0603"))
    )
    (comp (ref "C36")
      (value "100nF")
      (footprint "eagle-import:C0603")
      (libsource (lib "eagle-import") (part "C-EUC0603"))
    )
    (comp (ref "C38")
      (value "10uF")
      (footprint "eagle-import:C0603")
      (libsource (lib "eagle-import") (part "C-EUC0603"))
    )
    (comp (ref "C39")
      (value "100nF")
      (footprint "eagle-import:C0603")
      (libsource (lib "eagle-import") (part "C-EUC0603"))
    )
    (comp (ref "C40")
      (value "10uF")
      (footprint "eagle-import:C0603")
      (libsource (lib "eagle-import") (part "C-EUC0603"))
    )
    (comp (ref "C41")
      (value "100nF")
      (footprint "eagle-import:C0603")
      (libsource (lib "eagle-import") (part "C-EUC0603"))
    )
    (comp (ref "C42")
      (value "10uF")
      (footprint "eagle-import:C0603")
      (libsource (lib "eagle-import") (part "C-EUC0603"))
    )
    (comp (ref "C43")
      (value "100nF")
      (footprint "eagle-import:C0603")
      (libsource (lib "eagle-import") (part "C-EUC0603"))
    )
    (comp (ref "C44")
      (value "10uF")
      (footprint "eagle-import:C0603")
      (libsource (lib "eagle-import") (part "C-EUC0603"))
    )
    (comp (ref "C45")
      (value "10uF")
      (footprint "eagle-import:C0603")
      (libsource (lib "eagle-import") (part "C-EUC0603"))
    )
    (comp (ref "C46")
      (value "100nF")
      (footprint "eagle-import:C0603")
      (libsource (lib "eagle-import") (part "C-EUC0603"))
    )
    (comp (ref "C47")
      (value "10uF")
      (footprint "eagle-import:C0603")
      (libsource (lib "eagle-import") (part "C-EUC0603"))
    )
    (comp (ref "C48")
      (value "100nF")
      (footprint "eagle-import:C0603")
      (libsource (lib "eagle-import") (part "C-EUC0603"))
    )
    (comp (ref "C49")
      (value "10uF")
      (footprint "eagle-import:C0603")
      (libsource (lib "eagle-import") (part "C-EUC0603"))
    )
    (comp (ref "C50")
      (value "10uF")
      (footprint "eagle-import:C0603")
      (libsource (lib "eagle-import") (part "C-EUC0603"))
    )
    (comp (ref "C51")
      (value "100nF")
      (footprint "eagle-import:C0603")
      (libsource (lib "eagle-import") (part "C-EUC0603"))
    )
    (comp (ref "C62")
      (value "100nF")
      (footprint "eagle-import:C0603")
      (libsource (lib "eagle-import") (part "C-EUC0603"))
    )
    (comp (ref "C63")
      (value "100nF")
      (footprint "eagle-import:C0603")
      (libsource (lib "eagle-import") (part "C-EUC0603"))
    )
    (comp (ref "C64")
      (value "100nF")
      (footprint "eagle-import:C0603")
      (libsource (lib "eagle-import") (part "C-EUC0603"))
    )
    (comp (ref "C66")
      (value "100nF")
      (footprint "eagle-import:C0603")
      (libsource (lib "eagle-import") (part "C-EUC0603"))
    )
    (comp (ref "C67")
      (value "100nF")
      (footprint "eagle-import:C0603")
      (libsource (lib "eagle-import") (part "C-EUC0603"))
    )
    (comp (ref "C69")
      (value "10uF")
      (footprint "eagle-import:C0603")
      (libsource (lib "eagle-import") (part "C-EUC0603"))
    )
    (comp (ref "C70")
      (value "100nF")
      (footprint "eagle-import:C0603")
      (libsource (lib "eagle-import") (part "C-EUC0603"))
    )
    (comp (ref "C71")
      (value "10uF")
      (footprint "eagle-import:C0603")
      (libsource (lib "eagle-import") (part "C-EUC0603"))
    )
    (comp (ref "C72")
      (value "100nF")
      (footprint "eagle-import:C0603")
      (libsource (lib "eagle-import") (part "C-EUC0603"))
    )
    (comp (ref "C73")
      (value "10uF")
      (footprint "eagle-import:C0603")
      (libsource (lib "eagle-import") (part "C-EUC0603"))
    )
    (comp (ref "C74")
      (value "100nF")
      (footprint "eagle-import:C0603")
      (libsource (lib "eagle-import") (part "C-EUC0603"))
    )
    (comp (ref "C75")
      (value "10uF")
      (footprint "eagle-import:C0603")
      (libsource (lib "eagle-import") (part "C-EUC0603"))
    )
    (comp (ref "C76")
      (value "10uF")
      (footprint "eagle-import:C0603")
      (libsource (lib "eagle-import") (part "C-EUC0603"))
    )
    (comp (ref "C77")
      (value "100nF")
      (footprint "eagle-import:C0603")
      (libsource (lib "eagle-import") (part "C-EUC0603"))
    )
    (comp (ref "C78")
      (value "10uF")
      (footprint "eagle-import:C0603")
      (libsource (lib "eagle-import") (part "C-EUC0603"))
    )
    (comp (ref "C79")
      (value "100nF")
      (footprint "eagle-import:C0603")
      (libsource (lib "eagle-import") (part "C-EUC0603"))
    )
    (comp (ref "C80")
      (value "10uF")
      (footprint "eagle-import:C0603")
      (libsource (lib "eagle-import") (part "C-EUC0603"))
    )
    (comp (ref "C81")
      (value "10uF")
      (footprint "eagle-import:C0603")
      (libsource (lib "eagle-import") (part "C-EUC0603"))
    )
    (comp (ref "C82")
      (value "100nF")
      (footprint "eagle-import:C0603")
      (libsource (lib "eagle-import") (part "C-EUC0603"))
    )
    (comp (ref "C83")
      (value "100nF")
      (footprint "eagle-import:C0603")
      (libsource (lib "eagle-import") (part "C-EUC0603"))
    )
    (comp (ref "R2")
      (value "10k")
      (footprint "eagle-import:R0603")
      (libsource (lib "eagle-import") (part "R-EU_R0603"))
    )
    (comp (ref "R4")
      (value "10k")
      (footprint "eagle-import:R0603")
      (libsource (lib "eagle-import") (part "R-EU_R0603"))
    )
    (comp (ref "R6")
      (value "10k")
      (footprint "eagle-import:R0603")
      (libsource (lib "eagle-import") (part "R-EU_R0603"))
    )
    (comp (ref "R7")
      (value "10k")
      (footprint "eagle-import:R0603")
      (libsource (lib "eagle-import") (part "R-EU_R0603"))
    )
    (comp (ref "R8")
      (value "10k")
      (footprint "eagle-import:R0603")
      (libsource (lib "eagle-import") (part "R-EU_R0603"))
    )
    (comp (ref "R9")
      (value "10k")
      (footprint "eagle-import:R0603")
      (libsource (lib "eagle-import") (part "R-EU_R0603"))
    )
    (comp (ref "S2")
      (value "10-XX")
      (footprint "eagle-import:B3F-10XX")
      (fields (field (name "MPN") "B3F-1000"))
      (libsource (lib "eagle-import") (part "10-XX"))
    )
    (comp (ref "S3")
      (value "10-XX")
      (footprint "eagle-import:B3F-10XX")
      (fields (field (name "MPN") "B3F-1000"))
      (libsource (lib "eagle-import") (part "10-XX"))
    )
    (comp (ref "U4")
      (value "ADR421ARZ")
      (footprint "eagle-import:R_8")
      (fields (field (name "MANUFACTURER_PART_NUMBER") "ADR423ARZ"))
      (libsource (lib "eagle-import") (part "ADR423ARZ"))
    )
    (comp (ref "U5")
      (value "AD7616BSTZ")
      (footprint "eagle-import:ST_80_2")
      (libsource (lib "eagle-import") (part "AD7616BSTZ"))
    )
    (comp (ref "U6")
      (value "74AHC1G04GW/T1")
      (footprint "eagle-import:SOT65P210X110-5N")
      (libsource (lib "eagle-import") (part "74AHC1G04GW/T1"))
    )
    (comp (ref "U7")
      (value "ADR421ARZ")
      (footprint "eagle-import:R_8")
      (fields (field (name "MANUFACTURER_PART_NUMBER") "ADR423ARZ"))
      (libsource (lib "eagle-import") (part "ADR423ARZ"))
    )
    (comp (ref "U8")
      (value "AD7616BSTZ")
      (footprint "eagle-import:ST_80_2")
      (libsource (lib "eagle-import") (part "AD7616BSTZ"))
    )
    (comp (ref "U9")
      (value "74AHC1G04GW/T1")
      (footprint "eagle-import:SOT65P210X110-5N")
      (libsource (lib "eagle-import") (part "74AHC1G04GW/T1"))
    )
    (comp (ref "J1")
      (value "JST_PH_B3B-PH-K-S(LF)(SN)")
      (footprint "eagle-import:JST_PH_SHDR3W50P0X200_1X3_790X450X600")
      (fields
        (field (name "MANUFACTURER_PART_NUMBER") "B3B-PH-K-S(LF)(SN)")
        (field (name "RS_PART_NUMBER") "8201431P")
      )
      (libsource (lib "eagle-import") (part "JST_PH_B3B-PH-K-S(LF)(SN)"))
    )
    (comp (ref "J2")
      (value "JST_PH_B3B-PH-K-S(LF)(SN)")
      (footprint "eagle-import:JST_PH_SHDR3W50P0X200_1X3_790X450X600")
      (fields
        (field (name "MANUFACTURER_PART_NUMBER") "B3B-PH-K-S(LF)(SN)")
        (field (name "RS_PART_NUMBER") "8201431P")
      )
      (libsource (lib "eagle-import") (part "JST_PH_B3B-PH-K-S(LF)(SN)"))
    )
    (comp (ref "J3")
      (value "JST_PH_B3B-PH-K-S(LF)(SN)")
      (footprint "eagle-import:JST_PH_SHDR3W50P0X200_1X3_790X450X600")
      (fields
        (field (name "MANUFACTURER_PART_NUMBER") "B3B-PH-K-S(LF)(SN)")
        (field (name "RS_PART_NUMBER") "8201431P")
      )
      (libsource (lib "eagle-import") (part "JST_PH_B3B-PH-K-S(LF)(SN)"))
    )
    (comp (ref "J4")
      (value "JST_PH_B3B-PH-K-S(LF)(SN)")
      (footprint "eagle-import:JST_PH_SHDR3W50P0X200_1X3_790X450X600")
      (fields
        (field (name "MANUFACTURER_PART_NUMBER") "B3B-PH-K-S(LF)(SN)")
        (field (name "RS_PART_NUMBER") "8201431P")
      )
      (libsource (lib "eagle-import") (part "JST_PH_B3B-PH-K-S(LF)(SN)"))
    )
    (comp (ref "J5")
      (value "JST_PH_B3B-PH-K-S(LF)(SN)")
      (footprint "eagle-import:JST_PH_SHDR3W50P0X200_1X3_790X450X600")
      (fields
        (field (name "MANUFACTURER_PART_NUMBER") "B3B-PH-K-S(LF)(SN)")
        (field (name "RS_PART_NUMBER") "8201431P")
      )
      (libsource (lib "eagle-import") (part "JST_PH_B3B-PH-K-S(LF)(SN)"))
    )
    (comp (ref "J6")
      (value "JST_PH_B3B-PH-K-S(LF)(SN)")
      (footprint "eagle-import:JST_PH_SHDR3W50P0X200_1X3_790X450X600")
      (fields
        (field (name "MANUFACTURER_PART_NUMBER") "B3B-PH-K-S(LF)(SN)")
        (field (name "RS_PART_NUMBER") "8201431P")
      )
      (libsource (lib "eagle-import") (part "JST_PH_B3B-PH-K-S(LF)(SN)"))
    )
    (comp (ref "J7")
      (value "JST_PH_B3B-PH-K-S(LF)(SN)")
      (footprint "eagle-import:JST_PH_SHDR3W50P0X200_1X3_790X450X600")
      (fields
        (field (name "MANUFACTURER_PART_NUMBER") "B3B-PH-K-S(LF)(SN)")
        (field (name "RS_PART_NUMBER") "8201431P")
      )
      (libsource (lib "eagle-import") (part "JST_PH_B3B-PH-K-S(LF)(SN)"))
    )
    (comp (ref "J8")
      (value "JST_PH_B3B-PH-K-S(LF)(SN)")
      (footprint "eagle-import:JST_PH_SHDR3W50P0X200_1X3_790X450X600")
      (fields
        (field (name "MANUFACTURER_PART_NUMBER") "B3B-PH-K-S(LF)(SN)")
        (field (name "RS_PART_NUMBER") "8201431P")
      )
      (libsource (lib "eagle-import") (part "JST_PH_B3B-PH-K-S(LF)(SN)"))
    )
    (comp (ref "J9")
      (value "JST_PH_B3B-PH-K-S(LF)(SN)")
      (footprint "eagle-import:JST_PH_SHDR3W50P0X200_1X3_790X450X600")
      (fields
        (field (name "MANUFACTURER_PART_NUMBER") "B3B-PH-K-S(LF)(SN)")
        (field (name "RS_PART_NUMBER") "8201431P")
      )
      (libsource (lib "eagle-import") (part "JST_PH_B3B-PH-K-S(LF)(SN)"))
    )
    (comp (ref "J10")
      (value "JST_PH_B3B-PH-K-S(LF)(SN)")
      (footprint "eagle-import:JST_PH_SHDR3W50P0X200_1X3_790X450X600")
      (fields
        (field (name "MANUFACTURER_PART_NUMBER") "B3B-PH-K-S(LF)(SN)")
        (field (name "RS_PART_NUMBER") "8201431P")
      )
      (libsource (lib "eagle-import") (part "JST_PH_B3B-PH-K-S(LF)(SN)"))
    )
    (comp (ref "J11")
      (value "JST_PH_B3B-PH-K-S(LF)(SN)")
      (footprint "eagle-import:JST_PH_SHDR3W50P0X200_1X3_790X450X600")
      (fields
        (field (name "MANUFACTURER_PART_NUMBER") "B3B-PH-K-S(LF)(SN)")
        (field (name "RS_PART_NUMBER") "8201431P")
      )
      (libsource (lib "eagle-import") (part "JST_PH_B3B-PH-K-S(LF)(SN)"))
    )
    (comp (ref "J12")
      (value "JST_PH_B3B-PH-K-S(LF)(SN)")
      (footprint "eagle-import:JST_PH_SHDR3W50P0X200_1X3_790X450X600")
      (fields
        (field (name "MANUFACTURER_PART_NUMBER") "B3B-PH-K-S(LF)(SN)")
        (field (name "RS_PART_NUMBER") "8201431P")
      )
      (libsource (lib "eagle-import") (part "JST_PH_B3B-PH-K-S(LF)(SN)"))
    )
    (comp (ref "J13")
      (value "JST_PH_B3B-PH-K-S(LF)(SN)")
      (footprint "eagle-import:JST_PH_SHDR3W50P0X200_1X3_790X450X600")
      (fields
        (field (name "MANUFACTURER_PART_NUMBER") "B3B-PH-K-S(LF)(SN)")
        (field (name "RS_PART_NUMBER") "8201431P")
      )
      (libsource (lib "eagle-import") (part "JST_PH_B3B-PH-K-S(LF)(SN)"))
    )
    (comp (ref "J14")
      (value "JST_PH_B3B-PH-K-S(LF)(SN)")
      (footprint "eagle-import:JST_PH_SHDR3W50P0X200_1X3_790X450X600")
      (fields
        (field (name "MANUFACTURER_PART_NUMBER") "B3B-PH-K-S(LF)(SN)")
        (field (name "RS_PART_NUMBER") "8201431P")
      )
      (libsource (lib "eagle-import") (part "JST_PH_B3B-PH-K-S(LF)(SN)"))
    )
    (comp (ref "J15")
      (value "JST_PH_B3B-PH-K-S(LF)(SN)")
      (footprint "eagle-import:JST_PH_SHDR3W50P0X200_1X3_790X450X600")
      (fields
        (field (name "MANUFACTURER_PART_NUMBER") "B3B-PH-K-S(LF)(SN)")
        (field (name "RS_PART_NUMBER") "8201431P")
      )
      (libsource (lib "eagle-import") (part "JST_PH_B3B-PH-K-S(LF)(SN)"))
    )
    (comp (ref "J16")
      (value "JST_PH_B3B-PH-K-S(LF)(SN)")
      (footprint "eagle-import:JST_PH_SHDR3W50P0X200_1X3_790X450X600")
      (fields
        (field (name "MANUFACTURER_PART_NUMBER") "B3B-PH-K-S(LF)(SN)")
        (field (name "RS_PART_NUMBER") "8201431P")
      )
      (libsource (lib "eagle-import") (part "JST_PH_B3B-PH-K-S(LF)(SN)"))
    )
    (comp (ref "J17")
      (value "JST_PH_B3B-PH-K-S(LF)(SN)")
      (footprint "eagle-import:JST_PH_SHDR3W50P0X200_1X3_790X450X600")
      (fields
        (field (name "MANUFACTURER_PART_NUMBER") "B3B-PH-K-S(LF)(SN)")
        (field (name "RS_PART_NUMBER") "8201431P")
      )
      (libsource (lib "eagle-import") (part "JST_PH_B3B-PH-K-S(LF)(SN)"))
    )
    (comp (ref "J18")
      (value "JST_PH_B3B-PH-K-S(LF)(SN)")
      (footprint "eagle-import:JST_PH_SHDR3W50P0X200_1X3_790X450X600")
      (fields
        (field (name "MANUFACTURER_PART_NUMBER") "B3B-PH-K-S(LF)(SN)")
        (field (name "RS_PART_NUMBER") "8201431P")
      )
      (libsource (lib "eagle-import") (part "JST_PH_B3B-PH-K-S(LF)(SN)"))
    )
    (comp (ref "J19")
      (value "JST_PH_B3B-PH-K-S(LF)(SN)")
      (footprint "eagle-import:JST_PH_SHDR3W50P0X200_1X3_790X450X600")
      (fields
        (field (name "MANUFACTURER_PART_NUMBER") "B3B-PH-K-S(LF)(SN)")
        (field (name "RS_PART_NUMBER") "8201431P")
      )
      (libsource (lib "eagle-import") (part "JST_PH_B3B-PH-K-S(LF)(SN)"))
    )
    (comp (ref "J20")
      (value "JST_PH_B3B-PH-K-S(LF)(SN)")
      (footprint "eagle-import:JST_PH_SHDR3W50P0X200_1X3_790X450X600")
      (fields
        (field (name "MANUFACTURER_PART_NUMBER") "B3B-PH-K-S(LF)(SN)")
        (field (name "RS_PART_NUMBER") "8201431P")
      )
      (libsource (lib "eagle-import") (part "JST_PH_B3B-PH-K-S(LF)(SN)"))
    )
    (comp (ref "J21")
      (value "JST_PH_B3B-PH-K-S(LF)(SN)")
      (footprint "eagle-import:JST_PH_SHDR3W50P0X200_1X3_790X450X600")
      (fields
        (field (name "MANUFACTURER_PART_NUMBER") "B3B-PH-K-S(LF)(SN)")
        (field (name "RS_PART_NUMBER") "8201431P")
      )
      (libsource (lib "eagle-import") (part "JST_PH_B3B-PH-K-S(LF)(SN)"))
    )
    (comp (ref "J22")
      (value "JST_PH_B3B-PH-K-S(LF)(SN)")
      (footprint "eagle-import:JST_PH_SHDR3W50P0X200_1X3_790X450X600")
      (fields
        (field (name "MANUFACTURER_PART_NUMBER") "B3B-PH-K-S(LF)(SN)")
        (field (name "RS_PART_NUMBER") "8201431P")
      )
      (libsource (lib "eagle-import") (part "JST_PH_B3B-PH-K-S(LF)(SN)"))
    )
    (comp (ref "J23")
      (value "JST_PH_B3B-PH-K-S(LF)(SN)")
      (footprint "eagle-import:JST_PH_SHDR3W50P0X200_1X3_790X450X600")
      (fields
        (field (name "MANUFACTURER_PART_NUMBER") "B3B-PH-K-S(LF)(SN)")
        (field (name "RS_PART_NUMBER") "8201431P")
      )
      (libsource (lib "eagle-import") (part "JST_PH_B3B-PH-K-S(LF)(SN)"))
    )
    (comp (ref "J24")
      (value "JST_PH_B3B-PH-K-S(LF)(SN)")
      (footprint "eagle-import:JST_PH_SHDR3W50P0X200_1X3_790X450X600")
      (fields
        (field (name "MANUFACTURER_PART_NUMBER") "B3B-PH-K-S(LF)(SN)")
        (field (name "RS_PART_NUMBER") "8201431P")
      )
      (libsource (lib "eagle-import") (part "JST_PH_B3B-PH-K-S(LF)(SN)"))
    )
    (comp (ref "J25")
      (value "JST_PH_B3B-PH-K-S(LF)(SN)")
      (footprint "eagle-import:JST_PH_SHDR3W50P0X200_1X3_790X450X600")
      (fields
        (field (name "MANUFACTURER_PART_NUMBER") "B3B-PH-K-S(LF)(SN)")
        (field (name "RS_PART_NUMBER") "8201431P")
      )
      (libsource (lib "eagle-import") (part "JST_PH_B3B-PH-K-S(LF)(SN)"))
    )
    (comp (ref "J26")
      (value "JST_PH_B3B-PH-K-S(LF)(SN)")
      (footprint "eagle-import:JST_PH_SHDR3W50P0X200_1X3_790X450X600")
      (fields
        (field (name "MANUFACTURER_PART_NUMBER") "B3B-PH-K-S(LF)(SN)")
        (field (name "RS_PART_NUMBER") "8201431P")
      )
      (libsource (lib "eagle-import") (part "JST_PH_B3B-PH-K-S(LF)(SN)"))
    )
    (comp (ref "J27")
      (value "JST_PH_B3B-PH-K-S(LF)(SN)")
      (footprint "eagle-import:JST_PH_SHDR3W50P0X200_1X3_790X450X600")
      (fields
        (field (name "MANUFACTURER_PART_NUMBER") "B3B-PH-K-S(LF)(SN)")
        (field (name "RS_PART_NUMBER") "8201431P")
      )
      (libsource (lib "eagle-import") (part "JST_PH_B3B-PH-K-S(LF)(SN)"))
    )
    (comp (ref "J28")
      (value "JST_PH_B3B-PH-K-S(LF)(SN)")
      (footprint "eagle-import:JST_PH_SHDR3W50P0X200_1X3_790X450X600")
      (fields
        (field (name "MANUFACTURER_PART_NUMBER") "B3B-PH-K-S(LF)(SN)")
        (field (name "RS_PART_NUMBER") "8201431P")
      )
      (libsource (lib "eagle-import") (part "JST_PH_B3B-PH-K-S(LF)(SN)"))
    )
    (comp (ref "J29")
      (value "JST_PH_B3B-PH-K-S(LF)(SN)")
      (footprint "eagle-import:JST_PH_SHDR3W50P0X200_1X3_790X450X600")
      (fields
        (field (name "MANUFACTURER_PART_NUMBER") "B3B-PH-K-S(LF)(SN)")
        (field (name "RS_PART_NUMBER") "8201431P")
      )
      (libsource (lib "eagle-import") (part "JST_PH_B3B-PH-K-S(LF)(SN)"))
    )
    (comp (ref "J30")
      (value "JST_PH_B3B-PH-K-S(LF)(SN)")
      (footprint "eagle-import:JST_PH_SHDR3W50P0X200_1X3_790X450X600")
      (fields
        (field (name "MANUFACTURER_PART_NUMBER") "B3B-PH-K-S(LF)(SN)")
        (field (name "RS_PART_NUMBER") "8201431P")
      )
      (libsource (lib "eagle-import") (part "JST_PH_B3B-PH-K-S(LF)(SN)"))
    )
    (comp (ref "J31")
      (value "JST_PH_B3B-PH-K-S(LF)(SN)")
      (footprint "eagle-import:JST_PH_SHDR3W50P0X200_1X3_790X450X600")
      (fields
        (field (name "MANUFACTURER_PART_NUMBER") "B3B-PH-K-S(LF)(SN)")
        (field (name "RS_PART_NUMBER") "8201431P")
      )
      (libsource (lib "eagle-import") (part "JST_PH_B3B-PH-K-S(LF)(SN)"))
    )
    (comp (ref "J32")
      (value "JST_PH_B3B-PH-K-S(LF)(SN)")
      (footprint "eagle-import:JST_PH_SHDR3W50P0X200_1X3_790X450X600")
      (fields
        (field (name "MANUFACTURER_PART_NUMBER") "B3B-PH-K-S(LF)(SN)")
        (field (name "RS_PART_NUMBER") "8201431P")
      )
      (libsource (lib "eagle-import") (part "JST_PH_B3B-PH-K-S(LF)(SN)"))
    )
    (comp (ref "J33")
      (value "B4B-PH-K-S(LF)(SN)")
      (footprint "eagle-import:SHDR4W50P0X200_1X4_990X450X600")
      (fields (field (name "RS_PART_NUMBER") "8201434P"))
      (libsource (lib "eagle-import") (part "B4B-PH-K-S(LF)(SN)"))
    )
    (comp (ref "J34")
      (value "B4B-PH-K-S(LF)(SN)")
      (footprint "eagle-import:SHDR4W50P0X200_1X4_990X450X600")
      (fields (field (name "RS_PART_NUMBER") "8201434P"))
      (libsource (lib "eagle-import") (part "B4B-PH-K-S(LF)(SN)"))
    )
    (comp (ref "J35")
      (value "B4B-PH-K-S(LF)(SN)")
      (footprint "eagle-import:SHDR4W50P0X200_1X4_990X450X600")
      (fields (field (name "RS_PART_NUMBER") "8201434P"))
      (libsource (lib "eagle-import") (part "B4B-PH-K-S(LF)(SN)"))
    )
    (comp (ref "J36")
      (value "B4B-PH-K-S(LF)(SN)")
      (footprint "eagle-import:SHDR4W50P0X200_1X4_990X450X600")
      (fields (field (name "RS_PART_NUMBER") "8201434P"))
      (libsource (lib "eagle-import") (part "B4B-PH-K-S(LF)(SN)"))
    )
    (comp (ref "J37")
      (value "B4B-PH-K-S(LF)(SN)")
      (footprint "eagle-import:SHDR4W50P0X200_1X4_990X450X600")
      (fields (field (name "RS_PART_NUMBER") "8201434P"))
      (libsource (lib "eagle-import") (part "B4B-PH-K-S(LF)(SN)"))
    )
    (comp (ref "J38")
      (value "B4B-PH-K-S(LF)(SN)")
      (footprint "eagle-import:SHDR4W50P0X200_1X4_990X450X600")
      (fields (field (name "RS_PART_NUMBER") "8201434P"))
      (libsource (lib "eagle-import") (part "B4B-PH-K-S(LF)(SN)"))
    )
    (comp (ref "J39")
      (value "B4B-PH-K-S(LF)(SN)")
      (footprint "eagle-import:SHDR4W50P0X200_1X4_990X450X600")
      (fields (field (name "RS_PART_NUMBER") "8201434P"))
      (libsource (lib "eagle-import") (part "B4B-PH-K-S(LF)(SN)"))
    )
    (comp (ref "J40")
      (value "B4B-PH-K-S(LF)(SN)")
      (footprint "eagle-import:SHDR4W50P0X200_1X4_990X450X600")
      (fields (field (name "RS_PART_NUMBER") "8201434P"))
      (libsource (lib "eagle-import") (part "B4B-PH-K-S(LF)(SN)"))
    )
    (comp (ref "J41")
      (value "B4B-PH-K-S(LF)(SN)")
      (footprint "eagle-import:SHDR4W50P0X200_1X4_990X450X600")
      (fields (field (name "RS_PART_NUMBER") "8201434P"))
      (libsource (lib "eagle-import") (part "B4B-PH-K-S(LF)(SN)"))
    )
    (comp (ref "J42")
      (value "B4B-PH-K-S(LF)(SN)")
      (footprint "eagle-import:SHDR4W50P0X200_1X4_990X450X600")
      (fields (field (name "RS_PART_NUMBER") "8201434P"))
      (libsource (lib "eagle-import") (part "B4B-PH-K-S(LF)(SN)"))
    )
    (comp (ref "J43")
      (value "B4B-PH-K-S(LF)(SN)")
      (footprint "eagle-import:SHDR4W50P0X200_1X4_990X450X600")
      (fields (field (name "RS_PART_NUMBER") "8201434P"))
      (libsource (lib "eagle-import") (part "B4B-PH-K-S(LF)(SN)"))
    )
    (comp (ref "J44")
      (value "B4B-PH-K-S(LF)(SN)")
      (footprint "eagle-import:SHDR4W50P0X200_1X4_990X450X600")
      (fields (field (name "RS_PART_NUMBER") "8201434P"))
      (libsource (lib "eagle-import") (part "B4B-PH-K-S(LF)(SN)"))
    )
    (comp (ref "J45")
      (value "B4B-PH-K-S(LF)(SN)")
      (footprint "eagle-import:SHDR4W50P0X200_1X4_990X450X600")
      (fields (field (name "RS_PART_NUMBER") "8201434P"))
      (libsource (lib "eagle-import") (part "B4B-PH-K-S(LF)(SN)"))
    )
    (comp (ref "J46")
      (value "B4B-PH-K-S(LF)(SN)")
      (footprint "eagle-import:SHDR4W50P0X200_1X4_990X450X600")
      (fields (field (name "RS_PART_NUMBER") "8201434P"))
      (libsource (lib "eagle-import") (part "B4B-PH-K-S(LF)(SN)"))
    )
    (comp (ref "J47")
      (value "B4B-PH-K-S(LF)(SN)")
      (footprint "eagle-import:SHDR4W50P0X200_1X4_990X450X600")
      (fields (field (name "RS_PART_NUMBER") "8201434P"))
      (libsource (lib "eagle-import") (part "B4B-PH-K-S(LF)(SN)"))
    )
    (comp (ref "J48")
      (value "B4B-PH-K-S(LF)(SN)")
      (footprint "eagle-import:SHDR4W50P0X200_1X4_990X450X600")
      (fields (field (name "RS_PART_NUMBER") "8201434P"))
      (libsource (lib "eagle-import") (part "B4B-PH-K-S(LF)(SN)"))
    )
    (comp (ref "J49")
      (value "B4B-PH-K-S(LF)(SN)")
      (footprint "eagle-import:SHDR4W50P0X200_1X4_990X450X600")
      (fields (field (name "RS_PART_NUMBER") "8201434P"))
      (libsource (lib "eagle-import") (part "B4B-PH-K-S(LF)(SN)"))
    )
    (comp (ref "J50")
      (value "B4B-PH-K-S(LF)(SN)")
      (footprint "eagle-import:SHDR4W50P0X200_1X4_990X450X600")
      (fields (field (name "RS_PART_NUMBER") "8201434P"))
      (libsource (lib "eagle-import") (part "B4B-PH-K-S(LF)(SN)"))
    )
    (comp (ref "J51")
      (value "B4B-PH-K-S(LF)(SN)")
      (footprint "eagle-import:SHDR4W50P0X200_1X4_990X450X600")
      (fields (field (name "RS_PART_NUMBER") "8201434P"))
      (libsource (lib "eagle-import") (part "B4B-PH-K-S(LF)(SN)"))
    )
    (comp (ref "J52")
      (value "B4B-PH-K-S(LF)(SN)")
      (footprint "eagle-import:SHDR4W50P0X200_1X4_990X450X600")
      (fields (field (name "RS_PART_NUMBER") "8201434P"))
      (libsource (lib "eagle-import") (part "B4B-PH-K-S(LF)(SN)"))
    )
    (comp (ref "J53")
      (value "B4B-PH-K-S(LF)(SN)")
      (footprint "eagle-import:SHDR4W50P0X200_1X4_990X450X600")
      (fields (field (name "RS_PART_NUMBER") "8201434P"))
      (libsource (lib "eagle-import") (part "B4B-PH-K-S(LF)(SN)"))
    )
    (comp (ref "J54")
      (value "B4B-PH-K-S(LF)(SN)")
      (footprint "eagle-import:SHDR4W50P0X200_1X4_990X450X600")
      (fields (field (name "RS_PART_NUMBER") "8201434P"))
      (libsource (lib "eagle-import") (part "B4B-PH-K-S(LF)(SN)"))
    )
    (comp (ref "J55")
      (value "B4B-PH-K-S(LF)(SN)")
      (footprint "eagle-import:SHDR4W50P0X200_1X4_990X450X600")
      (fields (field (name "RS_PART_NUMBER") "8201434P"))
      (libsource (lib "eagle-import") (part "B4B-PH-K-S(LF)(SN)"))
    )
    (comp (ref "J56")
      (value "B4B-PH-K-S(LF)(SN)")
      (footprint "eagle-import:SHDR4W50P0X200_1X4_990X450X600")
      (fields (field (name "RS_PART_NUMBER") "8201434P"))
      (libsource (lib "eagle-import") (part "B4B-PH-K-S(LF)(SN)"))
    )
    (comp (ref "J57")
      (value "B4B-PH-K-S(LF)(SN)")
      (footprint "eagle-import:SHDR4W50P0X200_1X4_990X450X600")
      (fields (field (name "RS_PART_NUMBER") "8201434P"))
      (libsource (lib "eagle-import") (part "B4B-PH-K-S(LF)(SN)"))
    )
    (comp (ref "J58")
      (value "B4B-PH-K-S(LF)(SN)")
      (footprint "eagle-import:SHDR4W50P0X200_1X4_990X450X600")
      (fields (field (name "RS_PART_NUMBER") "8201434P"))
      (libsource (lib "eagle-import") (part "B4B-PH-K-S(LF)(SN)"))
    )
    (comp (ref "J59")
      (value "B4B-PH-K-S(LF)(SN)")
      (footprint "eagle-import:SHDR4W50P0X200_1X4_990X450X600")
      (fields (field (name "RS_PART_NUMBER") "8201434P"))
      (libsource (lib "eagle-import") (part "B4B-PH-K-S(LF)(SN)"))
    )
    (comp (ref "J60")
      (value "B4B-PH-K-S(LF)(SN)")
      (footprint "eagle-import:SHDR4W50P0X200_1X4_990X450X600")
      (fields (field (name "RS_PART_NUMBER") "8201434P"))
      (libsource (lib "eagle-import") (part "B4B-PH-K-S(LF)(SN)"))
    )
    (comp (ref "J61")
      (value "B4B-PH-K-S(LF)(SN)")
      (footprint "eagle-import:SHDR4W50P0X200_1X4_990X450X600")
      (fields (field (name "RS_PART_NUMBER") "8201434P"))
      (libsource (lib "eagle-import") (part "B4B-PH-K-S(LF)(SN)"))
    )
    (comp (ref "J62")
      (value "B4B-PH-K-S(LF)(SN)")
      (footprint "eagle-import:SHDR4W50P0X200_1X4_990X450X600")
      (fields (field (name "RS_PART_NUMBER") "8201434P"))
      (libsource (lib "eagle-import") (part "B4B-PH-K-S(LF)(SN)"))
    )
    (comp (ref "J63")
      (value "B4B-PH-K-S(LF)(SN)")
      (footprint "eagle-import:SHDR4W50P0X200_1X4_990X450X600")
      (fields (field (name "RS_PART_NUMBER") "8201434P"))
      (libsource (lib "eagle-import") (part "B4B-PH-K-S(LF)(SN)"))
    )
    (comp (ref "J64")
      (value "B4B-PH-K-S(LF)(SN)")
      (footprint "eagle-import:SHDR4W50P0X200_1X4_990X450X600")
      (fields (field (name "RS_PART_NUMBER") "8201434P"))
      (libsource (lib "eagle-import") (part "B4B-PH-K-S(LF)(SN)"))
    )
    (comp (ref "JP1")
      (value "JP1Q")
      (footprint "eagle-import:JP1")
      (libsource (lib "eagle-import") (part "JP1Q"))
    )
    (comp (ref "LED1")
      (value "LEDCHIP-LED0603")
      (footprint "eagle-import:CHIP-LED0603")
      (libsource (lib "eagle-import") (part "LEDCHIP-LED0603"))
    )
    (comp (ref "LED2")
      (value "LEDCHIP-LED0603")
      (footprint "eagle-import:CHIP-LED0603")
      (libsource (lib "eagle-import") (part "LEDCHIP-LED0603"))
    )
    (comp (ref "LED3")
      (value "LEDCHIP-LED0603")
      (footprint "eagle-import:CHIP-LED0603")
      (libsource (lib "eagle-import") (part "LEDCHIP-LED0603"))
    )
    (comp (ref "LED4")
      (value "LEDCHIP-LED0603")
      (footprint "eagle-import:CHIP-LED0603")
      (libsource (lib "eagle-import") (part "LEDCHIP-LED0603"))
    )
    (comp (ref "LED5")
      (value "LEDCHIP-LED0603")
      (footprint "eagle-import:CHIP-LED0603")
      (libsource (lib "eagle-import") (part "LEDCHIP-LED0603"))
    )
    (comp (ref "PL1")
      (value "555X-24V")
      (footprint "eagle-import:5566-24")
      (libsource (lib "eagle-import") (part "555X-24V"))
    )
    (comp (ref "Q1")
      (value "BCF29SMD")
      (footprint "eagle-import:SOT23-BEC")
      (libsource (lib "eagle-import") (part "BCF29SMD"))
    )
    (comp (ref "R1")
      (value "68")
      (footprint "eagle-import:R0805")
      (libsource (lib "eagle-import") (part "resistor_348_R-EU_R0805"))
    )
    (comp (ref "R3")
      (value "68")
      (footprint "eagle-import:R0805")
      (libsource (lib "eagle-import") (part "resistor_348_R-EU_R0805"))
    )
    (comp (ref "R5")
      (value "220")
      (footprint "eagle-import:R0805")
      (libsource (lib "eagle-import") (part "resistor_348_R-EU_R0805"))
    )
    (comp (ref "R10")
      (value "680")
      (footprint "eagle-import:R0805")
      (libsource (lib "eagle-import") (part "resistor_348_R-EU_R0805"))
    )
    (comp (ref "R11")
      (value "330")
      (footprint "eagle-import:R0805")
      (libsource (lib "eagle-import") (part "resistor_348_R-EU_R0805"))
    )
    (comp (ref "R12")
      (value "1k")
      (footprint "eagle-import:R0805")
      (libsource (lib "eagle-import") (part "resistor_348_R-EU_R0805"))
    )
    (comp (ref "S1")
      (value "1MS1T1B1M2QES-5")
      (footprint "eagle-import:1MS1T1B1M2QES-5")
      (fields (field (name "RS_PART_NUMBER") "7347066P"))
      (libsource (lib "eagle-import") (part "1MS1T1B1M2QES-5"))
    )
    (comp (ref "SV1")
      (value "FE20-2")
      (footprint "eagle-import:FE20-2")
      (libsource (lib "eagle-import") (part "FE20-2"))
    )
    (comp (ref "U1")
      (value "AMP-5103309-7-34PIN_5103309-7")
      (footprint "eagle-import:AMP-5103309-7-34PIN_TYCO_5103309-7")
      (fields (field (name "MPN") "5103309-7"))
      (libsource (lib "eagle-import") (part "AMP-5103309-7-34PIN_5103309-7"))
    )
    (comp (ref "U2")
      (value "AMP-5103309-7-34PIN_5103309-7")
      (footprint "eagle-import:AMP-5103309-7-34PIN_TYCO_5103309-7")
      (fields (field (name "MPN") "5103309-7"))
      (libsource (lib "eagle-import") (part "AMP-5103309-7-34PIN_5103309-7"))
    )
    (comp (ref "X1")
      (value "22-23-2031")
      (footprint "eagle-import:22-23-2031")
      (fields (field (name "MF") "MOLEX"))
      (libsource (lib "eagle-import") (part "22-23-2031"))
    )
  )
  (nets
    (net (code "1") (name "+5V") (class "Default")
      (node (ref "C32") (pin "1") (pinfunction "1_1") (pintype "passive"))
      (node (ref "C38") (pin "1") (pinfunction "1_1") (pintype "passive"))
      (node (ref "C39") (pin "1") (pinfunction "1_1") (pintype "passive"))
      (node (ref "C40") (pin "1") (pinfunction "1_1") (pintype "passive"))
      (node (ref "C41") (pin "1") (pinfunction "1_1") (pintype "passive"))
      (node (ref "C42") (pin "1") (pinfunction "1_1") (pintype "passive"))
      (node (ref "C43") (pin "1") (pinfunction "1_1") (pintype "passive"))
      (node (ref "C44") (pin "1") (pinfunction "1_1") (pintype "passive"))
      (node (ref "C63") (pin "1") (pinfunction "1_1") (pintype "passive"))
      (node (ref "C69") (pin "1") (pinfunction "1_1") (pintype "passive"))
      (node (ref "C70") (pin "1") (pinfunction "1_1") (pintype "passive"))
      (node (ref "C71") (pin "1") (pinfunction "1_1") (pintype "passive"))
      (node (ref "C72") (pin "1") (pinfunction "1_1") (pintype "passive"))
      (node (ref "C73") (pin "1") (pinfunction "1_1") (pintype "passive"))
      (node (ref "C74") (pin "1") (pinfunction "1_1") (pintype "passive"))
      (node (ref "C75") (pin "1") (pinfunction "1_1") (pintype "passive"))
      (node (ref "J33") (pin "1") (pinfunction "1_1") (pintype "passive"))
      (node (ref "J34") (pin "1") (pinfunction "1_1") (pintype "passive"))
      (node (ref "J35") (pin "1") (pinfunction "1_1") (pintype "passive"))
      (node (ref "J36") (pin "1") (pinfunction "1_1") (pintype "passive"))
      (node (ref "J37") (pin "1") (pinfunction "1_1") (pintype "passive"))
      (node (ref "J38") (pin "1") (pinfunction "1_1") (pintype "passive"))
      (node (ref "J39") (pin "1") (pinfunction "1_1") (pintype "passive"))
      (node (ref "J40") (pin "1") (pinfunction "1_1") (pintype "passive"))
      (node (ref "J41") (pin "1") (pinfunction "1_1") (pintype "passive"))
      (node (ref "J42") (pin "1") (pinfunction "1_1") (pintype "passive"))
      (node (ref "J43") (pin "1") (pinfunction "1_1") (pintype "passive"))
      (node (ref "J44") (pin "1") (pinfunction "1_1") (pintype "passive"))
      (node (ref "J45") (pin "1") (pinfunction "1_1") (pintype "passive"))
      (node (ref "J46") (pin "1") (pinfunction "1_1") (pintype "passive"))
      (node (ref "J47") (pin "1") (pinfunction "1_1") (pintype "passive"))
      (node (ref "J48") (pin "1") (pinfunction "1_1") (pintype "passive"))
      (node (ref "J49") (pin "1") (pinfunction "1_1") (pintype "passive"))
      (node (ref "J50") (pin "1") (pinfunction "1_1") (pintype "passive"))
      (node (ref "J51") (pin "1") (pinfunction "1_1") (pintype "passive"))
      (node (ref "J52") (pin "1") (pinfunction "1_1") (pintype "passive"))
      (node (ref "J53") (pin "1") (pinfunction "1_1") (pintype "passive"))
      (node (ref "J54") (pin "1") (pinfunction "1_1") (pintype "passive"))
      (node (ref "J55") (pin "1") (pinfunction "1_1") (pintype "passive"))
      (node (ref "J56") (pin "1") (pinfunction "1_1") (pintype "passive"))
      (node (ref "J57") (pin "1") (pinfunction "1_1") (pintype "passive"))
      (node (ref "J58") (pin "1") (pinfunction "1_1") (pintype "passive"))
      (node (ref "J59") (pin "1") (pinfunction "1_1") (pintype "passive"))
      (node (ref "J60") (pin "1") (pinfunction "1_1") (pintype "passive"))
      (node (ref "J61") (pin "1") (pinfunction "1_1") (pintype "passive"))
      (node (ref "J62") (pin "1") (pinfunction "1_1") (pintype "passive"))
      (node (ref "J63") (pin "1") (pinfunction "1_1") (pintype "passive"))
      (node (ref "J64") (pin "1") (pinfunction "1_1") (pintype "passive"))
      (node (ref "JP1") (pin "1") (pinfunction "1_1") (pintype "passive"))
      (node (ref "PL1") (pin "23") (pinfunction "S_23") (pintype "passive"))
      (node (ref "R5") (pin "2") (pinfunction "2_2") (pintype "passive"))
      (node (ref "U18") (pin "14") (pinfunction "REF_IN(+)_14") (pintype "passive"))
      (node (ref "U18") (pin "9") (pinfunction "AVDD_9") (pintype "passive"))
      (node (ref "U21") (pin "14") (pinfunction "REF_IN(+)_14") (pintype "passive"))
      (node (ref "U21") (pin "9") (pinfunction "AVDD_9") (pintype "passive"))
      (node (ref "U23") (pin "14") (pinfunction "REF_IN(+)_14") (pintype "passive"))
      (node (ref "U23") (pin "9") (pinfunction "AVDD_9") (pintype "passive"))
      (node (ref "U24") (pin "14") (pinfunction "REF_IN(+)_14") (pintype "passive"))
      (node (ref "U24") (pin "9") (pinfunction "AVDD_9") (pintype "passive"))
      (node (ref "U25") (pin "14") (pinfunction "REF_IN(+)_14") (pintype "passive"))
      (node (ref "U25") (pin "9") (pinfunction "AVDD_9") (pintype "passive"))
      (node (ref "U26") (pin "14") (pinfunction "REF_IN(+)_14") (pintype "passive"))
      (node (ref "U26") (pin "9") (pinfunction "AVDD_9") (pintype "passive"))
      (node (ref "U27") (pin "14") (pinfunction "REF_IN(+)_14") (pintype "passive"))
      (node (ref "U27") (pin "9") (pinfunction "AVDD_9") (pintype "passive"))
      (node (ref "U28") (pin "14") (pinfunction "REF_IN(+)_14") (pintype "passive"))
      (node (ref "U28") (pin "9") (pinfunction "AVDD_9") (pintype "passive"))
      (node (ref "U38") (pin "14") (pinfunction "REF_IN(+)_14") (pintype "passive"))
      (node (ref "U38") (pin "9") (pinfunction "AVDD_9") (pintype "passive"))
      (node (ref "U39") (pin "14") (pinfunction "REF_IN(+)_14") (pintype "passive"))
      (node (ref "U39") (pin "9") (pinfunction "AVDD_9") (pintype "passive"))
      (node (ref "U41") (pin "14") (pinfunction "REF_IN(+)_14") (pintype "passive"))
      (node (ref "U41") (pin "9") (pinfunction "AVDD_9") (pintype "passive"))
      (node (ref "U42") (pin "14") (pinfunction "REF_IN(+)_14") (pintype "passive"))
      (node (ref "U42") (pin "9") (pinfunction "AVDD_9") (pintype "passive"))
      (node (ref "U43") (pin "14") (pinfunction "REF_IN(+)_14") (pintype "passive"))
      (node (ref "U43") (pin "9") (pinfunction "AVDD_9") (pintype "passive"))
      (node (ref "U44") (pin "14") (pinfunction "REF_IN(+)_14") (pintype "passive"))
      (node (ref "U44") (pin "9") (pinfunction "AVDD_9") (pintype "passive"))
      (node (ref "U45") (pin "14") (pinfunction "REF_IN(+)_14") (pintype "passive"))
      (node (ref "U45") (pin "9") (pinfunction "AVDD_9") (pintype "passive"))
      (node (ref "U46") (pin "14") (pinfunction "REF_IN(+)_14") (pintype "passive"))
      (node (ref "U46") (pin "9") (pinfunction "AVDD_9") (pintype "passive"))
      (node (ref "U5") (pin "15") (pinfunction "AVDD_3_15") (pintype "passive"))
      (node (ref "U5") (pin "30") (pinfunction "AVDD_4_30") (pintype "passive"))
      (node (ref "U5") (pin "6") (pinfunction "AVDD_2_6") (pintype "passive"))
      (node (ref "U5") (pin "71") (pinfunction "AVDD_71") (pintype "passive"))
      (node (ref "U8") (pin "15") (pinfunction "AVDD_3_15") (pintype "passive"))
      (node (ref "U8") (pin "30") (pinfunction "AVDD_4_30") (pintype "passive"))
      (node (ref "U8") (pin "6") (pinfunction "AVDD_2_6") (pintype "passive"))
      (node (ref "U8") (pin "71") (pinfunction "AVDD_71") (pintype "passive"))
    )
    (net (code "2") (name "+5V_CURR_LIM") (class "Default")
      (node (ref "LED2") (pin "A") (pinfunction "A_A") (pintype "passive"))
      (node (ref "R5") (pin "1") (pinfunction "1_1") (pintype "passive"))
    )
    (net (code "3") (name "ADC1_0") (class "Default")
      (node (ref "J16") (pin "3") (pinfunction "3_3") (pintype "input"))
      (node (ref "U8") (pin "28") (pinfunction "V0A_28") (pintype "passive"))
    )
    (net (code "4") (name "ADC1_1") (class "Default")
      (node (ref "J15") (pin "3") (pinfunction "3_3") (pintype "input"))
      (node (ref "U8") (pin "26") (pinfunction "V1A_26") (pintype "passive"))
    )
    (net (code "5") (name "ADC1_2") (class "Default")
      (node (ref "J14") (pin "3") (pinfunction "3_3") (pintype "input"))
      (node (ref "U8") (pin "24") (pinfunction "V2A_24") (pintype "passive"))
    )
    (net (code "6") (name "ADC1_3") (class "Default")
      (node (ref "J13") (pin "3") (pinfunction "3_3") (pintype "input"))
      (node (ref "U8") (pin "22") (pinfunction "V3A_22") (pintype "passive"))
    )
    (net (code "7") (name "ADC1_4") (class "Default")
      (node (ref "J12") (pin "3") (pinfunction "3_3") (pintype "input"))
      (node (ref "U8") (pin "19") (pinfunction "V4A_19") (pintype "passive"))
    )
    (net (code "8") (name "ADC1_5") (class "Default")
      (node (ref "J11") (pin "3") (pinfunction "3_3") (pintype "input"))
      (node (ref "U8") (pin "17") (pinfunction "V5A_17") (pintype "passive"))
    )
    (net (code "9") (name "ADC1_6") (class "Default")
      (node (ref "J10") (pin "3") (pinfunction "3_3") (pintype "input"))
      (node (ref "U8") (pin "14") (pinfunction "V6A_14") (pintype "passive"))
    )
    (net (code "10") (name "ADC1_7") (class "Default")
      (node (ref "J9") (pin "3") (pinfunction "3_3") (pintype "input"))
      (node (ref "U8") (pin "12") (pinfunction "V7A_12") (pintype "passive"))
    )
    (net (code "11") (name "ADC1_8") (class "Default")
      (node (ref "J1") (pin "3") (pinfunction "3_3") (pintype "input"))
      (node (ref "U8") (pin "73") (pinfunction "V0B_73") (pintype "passive"))
    )
    (net (code "12") (name "ADC1_9") (class "Default")
      (node (ref "J2") (pin "3") (pinfunction "3_3") (pintype "input"))
      (node (ref "U8") (pin "75") (pinfunction "V1B_75") (pintype "passive"))
    )
    (net (code "13") (name "ADC1_10") (class "Default")
      (node (ref "J3") (pin "3") (pinfunction "3_3") (pintype "input"))
      (node (ref "U8") (pin "77") (pinfunction "V2B_77") (pintype "passive"))
    )
    (net (code "14") (name "ADC1_11") (class "Default")
      (node (ref "J4") (pin "3") (pinfunction "3_3") (pintype "input"))
      (node (ref "U8") (pin "79") (pinfunction "V3B_79") (pintype "passive"))
    )
    (net (code "15") (name "ADC1_12") (class "Default")
      (node (ref "J5") (pin "3") (pinfunction "3_3") (pintype "input"))
      (node (ref "U8") (pin "2") (pinfunction "V4B_2") (pintype "passive"))
    )
    (net (code "16") (name "ADC1_13") (class "Default")
      (node (ref "J6") (pin "3") (pinfunction "3_3") (pintype "input"))
      (node (ref "U8") (pin "4") (pinfunction "V5B_4") (pintype "passive"))
    )
    (net (code "17") (name "ADC1_14") (class "Default")
      (node (ref "J7") (pin "3") (pinfunction "3_3") (pintype "input"))
      (node (ref "U8") (pin "7") (pinfunction "V6B_7") (pintype "passive"))
    )
    (net (code "18") (name "ADC1_15") (class "Default")
      (node (ref "J8") (pin "3") (pinfunction "3_3") (pintype "input"))
      (node (ref "U8") (pin "9") (pinfunction "V7B_9") (pintype "passive"))
    )
    (net (code "19") (name "ADC2_0") (class "Default")
      (node (ref "J32") (pin "3") (pinfunction "3_3") (pintype "input"))
      (node (ref "U5") (pin "28") (pinfunction "V0A_28") (pintype "passive"))
    )
    (net (code "20") (name "ADC2_1") (class "Default")
      (node (ref "J31") (pin "3") (pinfunction "3_3") (pintype "input"))
      (node (ref "U5") (pin "26") (pinfunction "V1A_26") (pintype "passive"))
    )
    (net (code "21") (name "ADC2_2") (class "Default")
      (node (ref "J30") (pin "3") (pinfunction "3_3") (pintype "input"))
      (node (ref "U5") (pin "24") (pinfunction "V2A_24") (pintype "passive"))
    )
    (net (code "22") (name "ADC2_3") (class "Default")
      (node (ref "J29") (pin "3") (pinfunction "3_3") (pintype "input"))
      (node (ref "U5") (pin "22") (pinfunction "V3A_22") (pintype "passive"))
    )
    (net (code "23") (name "ADC2_4") (class "Default")
      (node (ref "J28") (pin "3") (pinfunction "3_3") (pintype "input"))
      (node (ref "U5") (pin "19") (pinfunction "V4A_19") (pintype "passive"))
    )
    (net (code "24") (name "ADC2_5") (class "Default")
      (node (ref "J27") (pin "3") (pinfunction "3_3") (pintype "input"))
      (node (ref "U5") (pin "17") (pinfunction "V5A_17") (pintype "passive"))
    )
    (net (code "25") (name "ADC2_6") (class "Default")
      (node (ref "J26") (pin "3") (pinfunction "3_3") (pintype "input"))
      (node (ref "U5") (pin "14") (pinfunction "V6A_14") (pintype "passive"))
    )
    (net (code "26") (name "ADC2_7") (class "Default")
      (node (ref "J25") (pin "3") (pinfunction "3_3") (pintype "input"))
      (node (ref "U5") (pin "12") (pinfunction "V7A_12") (pintype "passive"))
    )
    (net (code "27") (name "ADC2_8") (class "Default")
      (node (ref "J17") (pin "3") (pinfunction "3_3") (pintype "input"))
      (node (ref "U5") (pin "73") (pinfunction "V0B_73") (pintype "passive"))
    )
    (net (code "28") (name "ADC2_9") (class "Default")
      (node (ref "J18") (pin "3") (pinfunction "3_3") (pintype "input"))
      (node (ref "U5") (pin "75") (pinfunction "V1B_75") (pintype "passive"))
    )
    (net (code "29") (name "ADC2_10") (class "Default")
      (node (ref "J19") (pin "3") (pinfunction "3_3") (pintype "input"))
      (node (ref "U5") (pin "77") (pinfunction "V2B_77") (pintype "passive"))
    )
    (net (code "30") (name "ADC2_11") (class "Default")
      (node (ref "J20") (pin "3") (pinfunction "3_3") (pintype "input"))
      (node (ref "U5") (pin "79") (pinfunction "V3B_79") (pintype "passive"))
    )
    (net (code "31") (name "ADC2_12") (class "Default")
      (node (ref "J21") (pin "3") (pinfunction "3_3") (pintype "input"))
      (node (ref "U5") (pin "2") (pinfunction "V4B_2") (pintype "passive"))
    )
    (net (code "32") (name "ADC2_13") (class "Default")
      (node (ref "J22") (pin "3") (pinfunction "3_3") (pintype "input"))
      (node (ref "U5") (pin "4") (pinfunction "V5B_4") (pintype "passive"))
    )
    (net (code "33") (name "ADC2_14") (class "Default")
      (node (ref "J23") (pin "3") (pinfunction "3_3") (pintype "input"))
      (node (ref "U5") (pin "7") (pinfunction "V6B_7") (pintype "passive"))
    )
    (net (code "34") (name "ADC2_15") (class "Default")
      (node (ref "J24") (pin "3") (pinfunction "3_3") (pintype "input"))
      (node (ref "U5") (pin "9") (pinfunction "V7B_9") (pintype "passive"))
    )
    (net (code "35") (name "ADC_1_COM_MODE") (class "Default")
      (node (ref "R7") (pin "1") (pinfunction "1_1") (pintype "passive"))
      (node (ref "U8") (pin "40") (pinfunction "*PAR/SER_40") (pintype "passive"))
    )
    (net (code "36") (name "ADC_1_CONVST") (class "Default")
      (node (ref "U8") (pin "68") (pinfunction "CONVST_68") (pintype "passive"))
      (node (ref "U9") (pin "4") (pinfunction "Y_4") (pintype "output"))
    )
    (net (code "37") (name "ADC_1_REFCAP") (class "Default")
      (node (ref "C76") (pin "2") (pinfunction "2_2") (pintype "passive"))
      (node (ref "U8") (pin "31") (pinfunction "REFCAP_31") (pintype "passive"))
    )
    (net (code "38") (name "ADC_1_REFINOUT") (class "Default")
      (node (ref "C83") (pin "2") (pinfunction "2_2") (pintype "passive"))
      (node (ref "R9") (pin "1") (pinfunction "1_1") (pintype "passive"))
      (node (ref "U8") (pin "33") (pinfunction "REFINOUT_33") (pintype "passive"))
    )
    (net (code "39") (name "ADC_1_REGCAP") (class "Default")
      (node (ref "C79") (pin "1") (pinfunction "1_1") (pintype "passive"))
      (node (ref "C80") (pin "1") (pinfunction "1_1") (pintype "passive"))
      (node (ref "U8") (pin "70") (pinfunction "REGCAP_70") (pintype "passive"))
    )
    (net (code "40") (name "ADC_1_REGCAPD") (class "Default")
      (node (ref "C81") (pin "1") (pinfunction "1_1") (pintype "passive"))
      (node (ref "C82") (pin "1") (pinfunction "1_1") (pintype "passive"))
      (node (ref "U8") (pin "52") (pinfunction "REGCAPD_52") (pintype "passive"))
    )
    (net (code "41") (name "ADC_1_RST") (class "Default")
      (node (ref "R8") (pin "1") (pinfunction "1_1") (pintype "passive"))
      (node (ref "S3") (pin "1") (pinfunction "S_1") (pintype "passive"))
      (node (ref "U8") (pin "36") (pinfunction "*RESET_36") (pintype "passive"))
    )
    (net (code "42") (name "ADC_1_VREF") (class "Default")
      (node (ref "C30") (pin "+") (pinfunction "+_+") (pintype "passive"))
      (node (ref "C66") (pin "1") (pinfunction "1_1") (pintype "passive"))
      (node (ref "C67") (pin "1") (pinfunction "1_1") (pintype "passive"))
      (node (ref "R9") (pin "2") (pinfunction "2_2") (pintype "passive"))
      (node (ref "U7") (pin "6") (pinfunction "VOUT_6") (pintype "passive"))
    )
    (net (code "43") (name "ADC_2_COM_MODE") (class "Default")
      (node (ref "R2") (pin "1") (pinfunction "1_1") (pintype "passive"))
      (node (ref "U5") (pin "40") (pinfunction "*PAR/SER_40") (pintype "passive"))
    )
    (net (code "44") (name "ADC_2_CONVST") (class "Default")
      (node (ref "U5") (pin "68") (pinfunction "CONVST_68") (pintype "passive"))
      (node (ref "U6") (pin "4") (pinfunction "Y_4") (pintype "output"))
    )
    (net (code "45") (name "ADC_2_REFCAP") (class "Default")
      (node (ref "C45") (pin "2") (pinfunction "2_2") (pintype "passive"))
      (node (ref "U5") (pin "31") (pinfunction "REFCAP_31") (pintype "passive"))
    )
    (net (code "46") (name "ADC_2_REFINOUT") (class "Default")
      (node (ref "C62") (pin "2") (pinfunction "2_2") (pintype "passive"))
      (node (ref "R6") (pin "1") (pinfunction "1_1") (pintype "passive"))
      (node (ref "U5") (pin "33") (pinfunction "REFINOUT_33") (pintype "passive"))
    )
    (net (code "47") (name "ADC_2_REGCAP") (class "Default")
      (node (ref "C48") (pin "1") (pinfunction "1_1") (pintype "passive"))
      (node (ref "C49") (pin "1") (pinfunction "1_1") (pintype "passive"))
      (node (ref "U5") (pin "70") (pinfunction "REGCAP_70") (pintype "passive"))
    )
    (net (code "48") (name "ADC_2_REGCAPD") (class "Default")
      (node (ref "C50") (pin "1") (pinfunction "1_1") (pintype "passive"))
      (node (ref "C51") (pin "1") (pinfunction "1_1") (pintype "passive"))
      (node (ref "U5") (pin "52") (pinfunction "REGCAPD_52") (pintype "passive"))
    )
    (net (code "49") (name "ADC_2_RST") (class "Default")
      (node (ref "R4") (pin "1") (pinfunction "1_1") (pintype "passive"))
      (node (ref "S2") (pin "1") (pinfunction "S_1") (pintype "passive"))
      (node (ref "U5") (pin "36") (pinfunction "*RESET_36") (pintype "passive"))
    )
    (net (code "50") (name "ADC_2_VREF") (class "Default")
      (node (ref "C28") (pin "+") (pinfunction "+_+") (pintype "passive"))
      (node (ref "C35") (pin "1") (pinfunction "1_1") (pintype "passive"))
      (node (ref "C36") (pin "1") (pinfunction "1_1") (pintype "passive"))
      (node (ref "R6") (pin "2") (pinfunction "2_2") (pintype "passive"))
      (node (ref "U4") (pin "6") (pinfunction "VOUT_6") (pintype "passive"))
    )
    (net (code "51") (name "BT2_1_AIN1_+") (class "Default")
      (node (ref "J33") (pin "3") (pinfunction "3_3") (pintype "passive"))
      (node (ref "U38") (pin "10") (pinfunction "AIN1(+)_10") (pintype "passive"))
    )
    (net (code "52") (name "BT2_1_AIN1_-") (class "Default")
      (node (ref "J33") (pin "4") (pinfunction "4_4") (pintype "passive"))
      (node (ref "U38") (pin "11") (pinfunction "AIN1(-)_11") (pintype "passive"))
    )
    (net (code "53") (name "BT2_1_AIN2_+") (class "Default")
      (node (ref "J34") (pin "3") (pinfunction "3_3") (pintype "passive"))
      (node (ref "U38") (pin "12") (pinfunction "AIN2(+)D1_12") (pintype "passive"))
    )
    (net (code "54") (name "BT2_1_AIN2_-") (class "Default")
      (node (ref "J34") (pin "4") (pinfunction "4_4") (pintype "passive"))
      (node (ref "U38") (pin "13") (pinfunction "AIN2(-)D0_13") (pintype "passive"))
    )
    (net (code "55") (name "BT2_1_MCLK_OUT") (class "Default")
      (node (ref "U38") (pin "3") (pinfunction "MCLK_OUT_3") (pintype "passive"))
      (node (ref "U39") (pin "2") (pinfunction "MCLK_IN_2") (pintype "passive"))
    )
    (net (code "56") (name "BT2_2_AIN1_+") (class "Default")
      (node (ref "J35") (pin "3") (pinfunction "3_3") (pintype "passive"))
      (node (ref "U39") (pin "10") (pinfunction "AIN1(+)_10") (pintype "passive"))
    )
    (net (code "57") (name "BT2_2_AIN1_-") (class "Default")
      (node (ref "J35") (pin "4") (pinfunction "4_4") (pintype "passive"))
      (node (ref "U39") (pin "11") (pinfunction "AIN1(-)_11") (pintype "passive"))
    )
    (net (code "58") (name "BT2_2_AIN2_+") (class "Default")
      (node (ref "J36") (pin "3") (pinfunction "3_3") (pintype "passive"))
      (node (ref "U39") (pin "12") (pinfunction "AIN2(+)D1_12") (pintype "passive"))
    )
    (net (code "59") (name "BT2_2_AIN2_-") (class "Default")
      (node (ref "J36") (pin "4") (pinfunction "4_4") (pintype "passive"))
      (node (ref "U39") (pin "13") (pinfunction "AIN2(-)D0_13") (pintype "passive"))
    )
    (net (code "60") (name "BT2_2_MCLK_OUT") (class "Default")
      (node (ref "U39") (pin "3") (pinfunction "MCLK_OUT_3") (pintype "passive"))
      (node (ref "U41") (pin "2") (pinfunction "MCLK_IN_2") (pintype "passive"))
    )
    (net (code "61") (name "BT2_3_AIN1_+") (class "Default")
      (node (ref "J37") (pin "3") (pinfunction "3_3") (pintype "passive"))
      (node (ref "U41") (pin "10") (pinfunction "AIN1(+)_10") (pintype "passive"))
    )
    (net (code "62") (name "BT2_3_AIN1_-") (class "Default")
      (node (ref "J37") (pin "4") (pinfunction "4_4") (pintype "passive"))
      (node (ref "U41") (pin "11") (pinfunction "AIN1(-)_11") (pintype "passive"))
    )
    (net (code "63") (name "BT2_3_AIN2_+") (class "Default")
      (node (ref "J38") (pin "3") (pinfunction "3_3") (pintype "passive"))
      (node (ref "U41") (pin "12") (pinfunction "AIN2(+)D1_12") (pintype "passive"))
    )
    (net (code "64") (name "BT2_3_AIN2_-") (class "Default")
      (node (ref "J38") (pin "4") (pinfunction "4_4") (pintype "passive"))
      (node (ref "U41") (pin "13") (pinfunction "AIN2(-)D0_13") (pintype "passive"))
    )
    (net (code "65") (name "BT2_3_MCLK_OUT") (class "Default")
      (node (ref "U41") (pin "3") (pinfunction "MCLK_OUT_3") (pintype "passive"))
      (node (ref "U42") (pin "2") (pinfunction "MCLK_IN_2") (pintype "passive"))
    )
    (net (code "66") (name "BT2_4_AIN1_+") (class "Default")
      (node (ref "J39") (pin "3") (pinfunction "3_3") (pintype "passive"))
      (node (ref "U42") (pin "10") (pinfunction "AIN1(+)_10") (pintype "passive"))
    )
    (net (code "67") (name "BT2_4_AIN1_-") (class "Default")
      (node (ref "J39") (pin "4") (pinfunction "4_4") (pintype "passive"))
      (node (ref "U42") (pin "11") (pinfunction "AIN1(-)_11") (pintype "passive"))
    )
    (net (code "68") (name "BT2_4_AIN2_+") (class "Default")
      (node (ref "J40") (pin "3") (pinfunction "3_3") (pintype "passive"))
      (node (ref "U42") (pin "12") (pinfunction "AIN2(+)D1_12") (pintype "passive"))
    )
    (net (code "69") (name "BT2_4_AIN2_-") (class "Default")
      (node (ref "J40") (pin "4") (pinfunction "4_4") (pintype "passive"))
      (node (ref "U42") (pin "13") (pinfunction "AIN2(-)D0_13") (pintype "passive"))
    )
    (net (code "70") (name "BT2_4_MCLK_OUT") (class "Default")
      (node (ref "U42") (pin "3") (pinfunction "MCLK_OUT_3") (pintype "passive"))
      (node (ref "U43") (pin "2") (pinfunction "MCLK_IN_2") (pintype "passive"))
    )
    (net (code "71") (name "BT2_5_AIN1_+") (class "Default")
      (node (ref "J41") (pin "3") (pinfunction "3_3") (pintype "passive"))
      (node (ref "U43") (pin "10") (pinfunction "AIN1(+)_10") (pintype "passive"))
    )
    (net (code "72") (name "BT2_5_AIN1_-") (class "Default")
      (node (ref "J41") (pin "4") (pinfunction "4_4") (pintype "passive"))
      (node (ref "U43") (pin "11") (pinfunction "AIN1(-)_11") (pintype "passive"))
    )
    (net (code "73") (name "BT2_5_AIN2_+") (class "Default")
      (node (ref "J42") (pin "3") (pinfunction "3_3") (pintype "passive"))
      (node (ref "U43") (pin "12") (pinfunction "AIN2(+)D1_12") (pintype "passive"))
    )
    (net (code "74") (name "BT2_5_AIN2_-") (class "Default")
      (node (ref "J42") (pin "4") (pinfunction "4_4") (pintype "passive"))
      (node (ref "U43") (pin "13") (pinfunction "AIN2(-)D0_13") (pintype "passive"))
    )
    (net (code "75") (name "BT2_5_MCLK_OUT") (class "Default")
      (node (ref "U43") (pin "3") (pinfunction "MCLK_OUT_3") (pintype "passive"))
      (node (ref "U44") (pin "2") (pinfunction "MCLK_IN_2") (pintype "passive"))
    )
    (net (code "76") (name "BT2_6_AIN1_+") (class "Default")
      (node (ref "J43") (pin "3") (pinfunction "3_3") (pintype "passive"))
      (node (ref "U44") (pin "10") (pinfunction "AIN1(+)_10") (pintype "passive"))
    )
    (net (code "77") (name "BT2_6_AIN1_-") (class "Default")
      (node (ref "J43") (pin "4") (pinfunction "4_4") (pintype "passive"))
      (node (ref "U44") (pin "11") (pinfunction "AIN1(-)_11") (pintype "passive"))
    )
    (net (code "78") (name "BT2_6_AIN2_+") (class "Default")
      (node (ref "J44") (pin "3") (pinfunction "3_3") (pintype "passive"))
      (node (ref "U44") (pin "12") (pinfunction "AIN2(+)D1_12") (pintype "passive"))
    )
    (net (code "79") (name "BT2_6_AIN2_-") (class "Default")
      (node (ref "J44") (pin "4") (pinfunction "4_4") (pintype "passive"))
      (node (ref "U44") (pin "13") (pinfunction "AIN2(-)D0_13") (pintype "passive"))
    )
    (net (code "80") (name "BT2_6_MCLK_OUT") (class "Default")
      (node (ref "U44") (pin "3") (pinfunction "MCLK_OUT_3") (pintype "passive"))
      (node (ref "U45") (pin "2") (pinfunction "MCLK_IN_2") (pintype "passive"))
    )
    (net (code "81") (name "BT2_7_AIN1_+") (class "Default")
      (node (ref "J45") (pin "3") (pinfunction "3_3") (pintype "passive"))
      (node (ref "U45") (pin "10") (pinfunction "AIN1(+)_10") (pintype "passive"))
    )
    (net (code "82") (name "BT2_7_AIN1_-") (class "Default")
      (node (ref "J45") (pin "4") (pinfunction "4_4") (pintype "passive"))
      (node (ref "U45") (pin "11") (pinfunction "AIN1(-)_11") (pintype "passive"))
    )
    (net (code "83") (name "BT2_7_AIN2_+") (class "Default")
      (node (ref "J46") (pin "3") (pinfunction "3_3") (pintype "passive"))
      (node (ref "U45") (pin "12") (pinfunction "AIN2(+)D1_12") (pintype "passive"))
    )
    (net (code "84") (name "BT2_7_AIN2_-") (class "Default")
      (node (ref "J46") (pin "4") (pinfunction "4_4") (pintype "passive"))
      (node (ref "U45") (pin "13") (pinfunction "AIN2(-)D0_13") (pintype "passive"))
    )
    (net (code "85") (name "BT2_7_MCLK_OUT") (class "Default")
      (node (ref "U45") (pin "3") (pinfunction "MCLK_OUT_3") (pintype "passive"))
      (node (ref "U46") (pin "2") (pinfunction "MCLK_IN_2") (pintype "passive"))
    )
    (net (code "86") (name "BT2_8_AIN1_+") (class "Default")
      (node (ref "J47") (pin "3") (pinfunction "3_3") (pintype "passive"))
      (node (ref "U46") (pin "10") (pinfunction "AIN1(+)_10") (pintype "passive"))
    )
    (net (code "87") (name "BT2_8_AIN1_-") (class "Default")
      (node (ref "J47") (pin "4") (pinfunction "4_4") (pintype "passive"))
      (node (ref "U46") (pin "11") (pinfunction "AIN1(-)_11") (pintype "passive"))
    )
    (net (code "88") (name "BT2_8_AIN2_+") (class "Default")
      (node (ref "J48") (pin "3") (pinfunction "3_3") (pintype "passive"))
      (node (ref "U46") (pin "12") (pinfunction "AIN2(+)D1_12") (pintype "passive"))
    )
    (net (code "89") (name "BT2_8_AIN2_-") (class "Default")
      (node (ref "J48") (pin "4") (pinfunction "4_4") (pintype "passive"))
      (node (ref "U46") (pin "13") (pinfunction "AIN2(-)D0_13") (pintype "passive"))
    )
    (net (code "90") (name "BT_1_AIN1_+") (class "Default")
      (node (ref "J49") (pin "3") (pinfunction "3_3") (pintype "passive"))
      (node (ref "U18") (pin "10") (pinfunction "AIN1(+)_10") (pintype "passive"))
    )
    (net (code "91") (name "BT_1_AIN1_-") (class "Default")
      (node (ref "J49") (pin "4") (pinfunction "4_4") (pintype "passive"))
      (node (ref "U18") (pin "11") (pinfunction "AIN1(-)_11") (pintype "passive"))
    )
    (net (code "92") (name "BT_1_AIN2_+") (class "Default")
      (node (ref "J50") (pin "3") (pinfunction "3_3") (pintype "passive"))
      (node (ref "U18") (pin "12") (pinfunction "AIN2(+)D1_12") (pintype "passive"))
    )
    (net (code "93") (name "BT_1_AIN2_-") (class "Default")
      (node (ref "J50") (pin "4") (pinfunction "4_4") (pintype "passive"))
      (node (ref "U18") (pin "13") (pinfunction "AIN2(-)D0_13") (pintype "passive"))
    )
    (net (code "94") (name "BT_1_MCLK_OUT") (class "Default")
      (node (ref "U18") (pin "3") (pinfunction "MCLK_OUT_3") (pintype "passive"))
      (node (ref "U21") (pin "2") (pinfunction "MCLK_IN_2") (pintype "passive"))
    )
    (net (code "95") (name "BT_2_AIN1_+") (class "Default")
      (node (ref "J51") (pin "3") (pinfunction "3_3") (pintype "passive"))
      (node (ref "U21") (pin "10") (pinfunction "AIN1(+)_10") (pintype "passive"))
    )
    (net (code "96") (name "BT_2_AIN1_-") (class "Default")
      (node (ref "J51") (pin "4") (pinfunction "4_4") (pintype "passive"))
      (node (ref "U21") (pin "11") (pinfunction "AIN1(-)_11") (pintype "passive"))
    )
    (net (code "97") (name "BT_2_AIN2_+") (class "Default")
      (node (ref "J52") (pin "3") (pinfunction "3_3") (pintype "passive"))
      (node (ref "U21") (pin "12") (pinfunction "AIN2(+)D1_12") (pintype "passive"))
    )
    (net (code "98") (name "BT_2_AIN2_-") (class "Default")
      (node (ref "J52") (pin "4") (pinfunction "4_4") (pintype "passive"))
      (node (ref "U21") (pin "13") (pinfunction "AIN2(-)D0_13") (pintype "passive"))
    )
    (net (code "99") (name "BT_2_MCLK_OUT") (class "Default")
      (node (ref "U21") (pin "3") (pinfunction "MCLK_OUT_3") (pintype "passive"))
      (node (ref "U23") (pin "2") (pinfunction "MCLK_IN_2") (pintype "passive"))
    )
    (net (code "100") (name "BT_3_AIN1_+") (class "Default")
      (node (ref "J53") (pin "3") (pinfunction "3_3") (pintype "passive"))
      (node (ref "U23") (pin "10") (pinfunction "AIN1(+)_10") (pintype "passive"))
    )
    (net (code "101") (name "BT_3_AIN1_-") (class "Default")
      (node (ref "J53") (pin "4") (pinfunction "4_4") (pintype "passive"))
      (node (ref "U23") (pin "11") (pinfunction "AIN1(-)_11") (pintype "passive"))
    )
    (net (code "102") (name "BT_3_AIN2_+") (class "Default")
      (node (ref "J54") (pin "3") (pinfunction "3_3") (pintype "passive"))
      (node (ref "U23") (pin "12") (pinfunction "AIN2(+)D1_12") (pintype "passive"))
    )
    (net (code "103") (name "BT_3_AIN2_-") (class "Default")
      (node (ref "J54") (pin "4") (pinfunction "4_4") (pintype "passive"))
      (node (ref "U23") (pin "13") (pinfunction "AIN2(-)D0_13") (pintype "passive"))
    )
    (net (code "104") (name "BT_3_MCLK_OUT") (class "Default")
      (node (ref "U23") (pin "3") (pinfunction "MCLK_OUT_3") (pintype "passive"))
      (node (ref "U24") (pin "2") (pinfunction "MCLK_IN_2") (pintype "passive"))
    )
    (net (code "105") (name "BT_4_AIN1_+") (class "Default")
      (node (ref "J55") (pin "3") (pinfunction "3_3") (pintype "passive"))
      (node (ref "U24") (pin "10") (pinfunction "AIN1(+)_10") (pintype "passive"))
    )
    (net (code "106") (name "BT_4_AIN1_-") (class "Default")
      (node (ref "J55") (pin "4") (pinfunction "4_4") (pintype "passive"))
      (node (ref "U24") (pin "11") (pinfunction "AIN1(-)_11") (pintype "passive"))
    )
    (net (code "107") (name "BT_4_AIN2_+") (class "Default")
      (node (ref "J56") (pin "3") (pinfunction "3_3") (pintype "passive"))
      (node (ref "U24") (pin "12") (pinfunction "AIN2(+)D1_12") (pintype "passive"))
    )
    (net (code "108") (name "BT_4_AIN2_-") (class "Default")
      (node (ref "J56") (pin "4") (pinfunction "4_4") (pintype "passive"))
      (node (ref "U24") (pin "13") (pinfunction "AIN2(-)D0_13") (pintype "passive"))
    )
    (net (code "109") (name "BT_4_MCLK_OUT") (class "Default")
      (node (ref "U24") (pin "3") (pinfunction "MCLK_OUT_3") (pintype "passive"))
      (node (ref "U25") (pin "2") (pinfunction "MCLK_IN_2") (pintype "passive"))
    )
    (net (code "110") (name "BT_5_AIN1_+") (class "Default")
      (node (ref "J57") (pin "3") (pinfunction "3_3") (pintype "passive"))
      (node (ref "U25") (pin "10") (pinfunction "AIN1(+)_10") (pintype "passive"))
    )
    (net (code "111") (name "BT_5_AIN1_-") (class "Default")
      (node (ref "J57") (pin "4") (pinfunction "4_4") (pintype "passive"))
      (node (ref "U25") (pin "11") (pinfunction "AIN1(-)_11") (pintype "passive"))
    )
    (net (code "112") (name "BT_5_AIN2_+") (class "Default")
      (node (ref "J58") (pin "3") (pinfunction "3_3") (pintype "passive"))
      (node (ref "U25") (pin "12") (pinfunction "AIN2(+)D1_12") (pintype "passive"))
    )
    (net (code "113") (name "BT_5_AIN2_-") (class "Default")
      (node (ref "J58") (pin "4") (pinfunction "4_4") (pintype "passive"))
      (node (ref "U25") (pin "13") (pinfunction "AIN2(-)D0_13") (pintype "passive"))
    )
    (net (code "114") (name "BT_5_MCLK_OUT") (class "Default")
      (node (ref "U25") (pin "3") (pinfunction "MCLK_OUT_3") (pintype "passive"))
      (node (ref "U26") (pin "2") (pinfunction "MCLK_IN_2") (pintype "passive"))
    )
    (net (code "115") (name "BT_6_AIN1_+") (class "Default")
      (node (ref "J59") (pin "3") (pinfunction "3_3") (pintype "passive"))
      (node (ref "U26") (pin "10") (pinfunction "AIN1(+)_10") (pintype "passive"))
    )
    (net (code "116") (name "BT_6_AIN1_-") (class "Default")
      (node (ref "J59") (pin "4") (pinfunction "4_4") (pintype "passive"))
      (node (ref "U26") (pin "11") (pinfunction "AIN1(-)_11") (pintype "passive"))
    )
    (net (code "117") (name "BT_6_AIN2_+") (class "Default")
      (node (ref "J60") (pin "3") (pinfunction "3_3") (pintype "passive"))
      (node (ref "U26") (pin "12") (pinfunction "AIN2(+)D1_12") (pintype "passive"))
    )
    (net (code "118") (name "BT_6_AIN2_-") (class "Default")
      (node (ref "J60") (pin "4") (pinfunction "4_4") (pintype "passive"))
      (node (ref "U26") (pin "13") (pinfunction "AIN2(-)D0_13") (pintype "passive"))
    )
    (net (code "119") (name "BT_6_MCLK_OUT") (class "Default")
      (node (ref "U26") (pin "3") (pinfunction "MCLK_OUT_3") (pintype "passive"))
      (node (ref "U27") (pin "2") (pinfunction "MCLK_IN_2") (pintype "passive"))
    )
    (net (code "120") (name "BT_7_AIN1_+") (class "Default")
      (node (ref "J61") (pin "3") (pinfunction "3_3") (pintype "passive"))
      (node (ref "U27") (pin "10") (pinfunction "AIN1(+)_10") (pintype "passive"))
    )
    (net (code "121") (name "BT_7_AIN1_-") (class "Default")
      (node (ref "J61") (pin "4") (pinfunction "4_4") (pintype "passive"))
      (node (ref "U27") (pin "11") (pinfunction "AIN1(-)_11") (pintype "passive"))
    )
    (net (code "122") (name "BT_7_AIN2_+") (class "Default")
      (node (ref "J62") (pin "3") (pinfunction "3_3") (pintype "passive"))
      (node (ref "U27") (pin "12") (pinfunction "AIN2(+)D1_12") (pintype "passive"))
    )
    (net (code "123") (name "BT_7_AIN2_-") (class "Default")
      (node (ref "J62") (pin "4") (pinfunction "4_4") (pintype "passive"))
      (node (ref "U27") (pin "13") (pinfunction "AIN2(-)D0_13") (pintype "passive"))
    )
    (net (code "124") (name "BT_7_MCLK_OUT") (class "Default")
      (node (ref "U27") (pin "3") (pinfunction "MCLK_OUT_3") (pintype "passive"))
      (node (ref "U28") (pin "2") (pinfunction "MCLK_IN_2") (pintype "passive"))
    )
    (net (code "125") (name "BT_8_AIN1_+") (class "Default")
      (node (ref "J63") (pin "3") (pinfunction "3_3") (pintype "passive"))
      (node (ref "U28") (pin "10") (pinfunction "AIN1(+)_10") (pintype "passive"))
    )
    (net (code "126") (name "BT_8_AIN1_-") (class "Default")
      (node (ref "J63") (pin "4") (pinfunction "4_4") (pintype "passive"))
      (node (ref "U28") (pin "11") (pinfunction "AIN1(-)_11") (pintype "passive"))
    )
    (net (code "127") (name "BT_8_AIN2_+") (class "Default")
      (node (ref "J64") (pin "3") (pinfunction "3_3") (pintype "passive"))
      (node (ref "U28") (pin "12") (pinfunction "AIN2(+)D1_12") (pintype "passive"))
    )
    (net (code "128") (name "BT_8_AIN2_-") (class "Default")
      (node (ref "J64") (pin "4") (pinfunction "4_4") (pintype "passive"))
      (node (ref "U28") (pin "13") (pinfunction "AIN2(-)D0_13") (pintype "passive"))
    )
    (net (code "129") (name "CONVST") (class "Default")
      (node (ref "SV1") (pin "11") (pinfunction "11_11") (pintype "passive"))
      (node (ref "U6") (pin "2") (pinfunction "A_2") (pintype "input"))
      (node (ref "U9") (pin "2") (pinfunction "A_2") (pintype "input"))
    )
    (net (code "130") (name "DAC1_0") (class "Default")
      (node (ref "U1") (pin "15") (pinfunction "15_15") (pintype "passive"))
      (node (ref "U15") (pin "34") (pinfunction "VOUT0_34") (pintype "passive"))
    )
    (net (code "131") (name "DAC1_1") (class "Default")
      (node (ref "U1") (pin "13") (pinfunction "13_13") (pintype "passive"))
      (node (ref "U15") (pin "35") (pinfunction "VOUT1_35") (pintype "passive"))
    )
    (net (code "132") (name "DAC1_2") (class "Default")
      (node (ref "U1") (pin "11") (pinfunction "11_11") (pintype "passive"))
      (node (ref "U15") (pin "36") (pinfunction "VOUT2_36") (pintype "passive"))
    )
    (net (code "133") (name "DAC1_3") (class "Default")
      (node (ref "U1") (pin "9") (pinfunction "9_9") (pintype "passive"))
      (node (ref "U15") (pin "37") (pinfunction "VOUT3_37") (pintype "passive"))
    )
    (net (code "134") (name "DAC1_4") (class "Default")
      (node (ref "U1") (pin "7") (pinfunction "7_7") (pintype "passive"))
      (node (ref "U15") (pin "39") (pinfunction "VOUT4_39") (pintype "passive"))
    )
    (net (code "135") (name "DAC1_5") (class "Default")
      (node (ref "U1") (pin "5") (pinfunction "5_5") (pintype "passive"))
      (node (ref "U15") (pin "40") (pinfunction "VOUT5_40") (pintype "passive"))
    )
    (net (code "136") (name "DAC1_6") (class "Default")
      (node (ref "U1") (pin "3") (pinfunction "3_3") (pintype "passive"))
      (node (ref "U15") (pin "41") (pinfunction "VOUT6_41") (pintype "passive"))
    )
    (net (code "137") (name "DAC1_7") (class "Default")
      (node (ref "U1") (pin "1") (pinfunction "1_1") (pintype "passive"))
      (node (ref "U15") (pin "42") (pinfunction "VOUT7_42") (pintype "passive"))
    )
    (net (code "138") (name "DAC1_8") (class "Default")
      (node (ref "U1") (pin "31") (pinfunction "31_31") (pintype "passive"))
      (node (ref "U15") (pin "15") (pinfunction "VOUT8_15") (pintype "passive"))
    )
    (net (code "139") (name "DAC1_9") (class "Default")
      (node (ref "U1") (pin "29") (pinfunction "29_29") (pintype "passive"))
      (node (ref "U15") (pin "16") (pinfunction "VOUT9_16") (pintype "passive"))
    )
    (net (code "140") (name "DAC1_10") (class "Default")
      (node (ref "U1") (pin "27") (pinfunction "27_27") (pintype "passive"))
      (node (ref "U15") (pin "17") (pinfunction "VOUT10_17") (pintype "passive"))
    )
    (net (code "141") (name "DAC1_11") (class "Default")
      (node (ref "U1") (pin "25") (pinfunction "25_25") (pintype "passive"))
      (node (ref "U15") (pin "18") (pinfunction "VOUT11_18") (pintype "passive"))
    )
    (net (code "142") (name "DAC1_12") (class "Default")
      (node (ref "U1") (pin "23") (pinfunction "23_23") (pintype "passive"))
      (node (ref "U15") (pin "20") (pinfunction "VOUT12_20") (pintype "passive"))
    )
    (net (code "143") (name "DAC1_13") (class "Default")
      (node (ref "U1") (pin "21") (pinfunction "21_21") (pintype "passive"))
      (node (ref "U15") (pin "21") (pinfunction "VOUT13_21") (pintype "passive"))
    )
    (net (code "144") (name "DAC1_14") (class "Default")
      (node (ref "U1") (pin "19") (pinfunction "19_19") (pintype "passive"))
      (node (ref "U15") (pin "22") (pinfunction "VOUT14_22") (pintype "passive"))
    )
    (net (code "145") (name "DAC1_15") (class "Default")
      (node (ref "U1") (pin "17") (pinfunction "17_17") (pintype "passive"))
      (node (ref "U15") (pin "23") (pinfunction "VOUT15_23") (pintype "passive"))
    )
    (net (code "146") (name "DAC2_0") (class "Default")
      (node (ref "U19") (pin "34") (pinfunction "VOUT0_34") (pintype "passive"))
      (node (ref "U2") (pin "15") (pinfunction "15_15") (pintype "passive"))
    )
    (net (code "147") (name "DAC2_1") (class "Default")
      (node (ref "U19") (pin "35") (pinfunction "VOUT1_35") (pintype "passive"))
      (node (ref "U2") (pin "13") (pinfunction "13_13") (pintype "passive"))
    )
    (net (code "148") (name "DAC2_2") (class "Default")
      (node (ref "U19") (pin "36") (pinfunction "VOUT2_36") (pintype "passive"))
      (node (ref "U2") (pin "11") (pinfunction "11_11") (pintype "passive"))
    )
    (net (code "149") (name "DAC2_3") (class "Default")
      (node (ref "U19") (pin "37") (pinfunction "VOUT3_37") (pintype "passive"))
      (node (ref "U2") (pin "9") (pinfunction "9_9") (pintype "passive"))
    )
    (net (code "150") (name "DAC2_4") (class "Default")
      (node (ref "U19") (pin "39") (pinfunction "VOUT4_39") (pintype "passive"))
      (node (ref "U2") (pin "7") (pinfunction "7_7") (pintype "passive"))
    )
    (net (code "151") (name "DAC2_5") (class "Default")
      (node (ref "U19") (pin "40") (pinfunction "VOUT5_40") (pintype "passive"))
      (node (ref "U2") (pin "5") (pinfunction "5_5") (pintype "passive"))
    )
    (net (code "152") (name "DAC2_6") (class "Default")
      (node (ref "U19") (pin "41") (pinfunction "VOUT6_41") (pintype "passive"))
      (node (ref "U2") (pin "3") (pinfunction "3_3") (pintype "passive"))
    )
    (net (code "153") (name "DAC2_7") (class "Default")
      (node (ref "U19") (pin "42") (pinfunction "VOUT7_42") (pintype "passive"))
      (node (ref "U2") (pin "1") (pinfunction "1_1") (pintype "passive"))
    )
    (net (code "154") (name "DAC2_8") (class "Default")
      (node (ref "U19") (pin "15") (pinfunction "VOUT8_15") (pintype "passive"))
      (node (ref "U2") (pin "31") (pinfunction "31_31") (pintype "passive"))
    )
    (net (code "155") (name "DAC2_9") (class "Default")
      (node (ref "U19") (pin "16") (pinfunction "VOUT9_16") (pintype "passive"))
      (node (ref "U2") (pin "29") (pinfunction "29_29") (pintype "passive"))
    )
    (net (code "156") (name "DAC2_10") (class "Default")
      (node (ref "U19") (pin "17") (pinfunction "VOUT10_17") (pintype "passive"))
      (node (ref "U2") (pin "27") (pinfunction "27_27") (pintype "passive"))
    )
    (net (code "157") (name "DAC2_11") (class "Default")
      (node (ref "U19") (pin "18") (pinfunction "VOUT11_18") (pintype "passive"))
      (node (ref "U2") (pin "25") (pinfunction "25_25") (pintype "passive"))
    )
    (net (code "158") (name "DAC2_12") (class "Default")
      (node (ref "U19") (pin "20") (pinfunction "VOUT12_20") (pintype "passive"))
      (node (ref "U2") (pin "23") (pinfunction "23_23") (pintype "passive"))
    )
    (net (code "159") (name "DAC2_13") (class "Default")
      (node (ref "U19") (pin "21") (pinfunction "VOUT13_21") (pintype "passive"))
      (node (ref "U2") (pin "21") (pinfunction "21_21") (pintype "passive"))
    )
    (net (code "160") (name "DAC2_14") (class "Default")
      (node (ref "U19") (pin "22") (pinfunction "VOUT14_22") (pintype "passive"))
      (node (ref "U2") (pin "19") (pinfunction "19_19") (pintype "passive"))
    )
    (net (code "161") (name "DAC2_15") (class "Default")
      (node (ref "U19") (pin "23") (pinfunction "VOUT15_23") (pintype "passive"))
      (node (ref "U2") (pin "17") (pinfunction "17_17") (pintype "passive"))
    )
    (net (code "162") (name "DAC_1_CLR") (class "Default")
      (node (ref "R16") (pin "2") (pinfunction "2_2") (pintype "passive"))
      (node (ref "U15") (pin "2") (pinfunction "*CLR_2") (pintype "passive"))
    )
    (net (code "163") (name "DAC_1_RST") (class "Default")
      (node (ref "R15") (pin "2") (pinfunction "2_2") (pintype "passive"))
      (node (ref "S6") (pin "4") (pinfunction "P1_4") (pintype "passive"))
      (node (ref "U15") (pin "3") (pinfunction "*RESET_3") (pintype "passive"))
    )
    (net (code "164") (name "DAC_2_CLR") (class "Default")
      (node (ref "R20") (pin "2") (pinfunction "2_2") (pintype "passive"))
      (node (ref "U19") (pin "2") (pinfunction "*CLR_2") (pintype "passive"))
    )
    (net (code "165") (name "DAC_2_RST") (class "Default")
      (node (ref "R19") (pin "2") (pinfunction "2_2") (pintype "passive"))
      (node (ref "S8") (pin "4") (pinfunction "P1_4") (pintype "passive"))
      (node (ref "U19") (pin "3") (pinfunction "*RESET_3") (pintype "passive"))
    )
    (net (code "166") (name "DVCC") (class "Default")
      (node (ref "C1") (pin "+") (pinfunction "+_+") (pintype "passive"))
      (node (ref "C102") (pin "1") (pinfunction "1_1") (pintype "passive"))
      (node (ref "C103") (pin "1") (pinfunction "1_1") (pintype "passive"))
      (node (ref "C11") (pin "2") (pinfunction "2_2") (pintype "passive"))
      (node (ref "C12") (pin "2") (pinfunction "2_2") (pintype "passive"))
      (node (ref "C13") (pin "1") (pinfunction "1_1") (pintype "passive"))
      (node (ref "C136") (pin "1") (pinfunction "1_1") (pintype "passive"))
      (node (ref "C137") (pin "1") (pinfunction "1_1") (pintype "passive"))
      (node (ref "C14") (pin "1") (pinfunction "1_1") (pintype "passive"))
      (node (ref "C15") (pin "1") (pinfunction "1_1") (pintype "passive"))
      (node (ref "C16") (pin "1") (pinfunction "1_1") (pintype "passive"))
      (node (ref "C19") (pin "1") (pinfunction "1_1") (pintype "passive"))
      (node (ref "C2") (pin "+") (pinfunction "+_+") (pintype "passive"))
      (node (ref "C20") (pin "1") (pinfunction "1_1") (pintype "passive"))
      (node (ref "C21") (pin "+") (pinfunction "+_+") (pintype "passive"))
      (node (ref "C22") (pin "+") (pinfunction "+_+") (pintype "passive"))
      (node (ref "C46") (pin "1") (pinfunction "1_1") (pintype "passive"))
      (node (ref "C47") (pin "1") (pinfunction "1_1") (pintype "passive"))
      (node (ref "C52") (pin "2") (pinfunction "2_2") (pintype "passive"))
      (node (ref "C53") (pin "2") (pinfunction "2_2") (pintype "passive"))
      (node (ref "C54") (pin "1") (pinfunction "1_1") (pintype "passive"))
      (node (ref "C55") (pin "1") (pinfunction "1_1") (pintype "passive"))
      (node (ref "C56") (pin "1") (pinfunction "1_1") (pintype "passive"))
      (node (ref "C57") (pin "1") (pinfunction "1_1") (pintype "passive"))
      (node (ref "C60") (pin "1") (pinfunction "1_1") (pintype "passive"))
      (node (ref "C61") (pin "1") (pinfunction "1_1") (pintype "passive"))
      (node (ref "C77") (pin "1") (pinfunction "1_1") (pintype "passive"))
      (node (ref "C78") (pin "1") (pinfunction "1_1") (pintype "passive"))
      (node (ref "PL1") (pin "2") (pinfunction "S_2") (pintype "passive"))
      (node (ref "Q1") (pin "C") (pinfunction "C_C") (pintype "passive"))
      (node (ref "R15") (pin "1") (pinfunction "1_1") (pintype "passive"))
      (node (ref "R16") (pin "1") (pinfunction "1_1") (pintype "passive"))
      (node (ref "R19") (pin "1") (pinfunction "1_1") (pintype "passive"))
      (node (ref "R2") (pin "2") (pinfunction "2_2") (pintype "passive"))
      (node (ref "R20") (pin "1") (pinfunction "1_1") (pintype "passive"))
      (node (ref "R3") (pin "2") (pinfunction "2_2") (pintype "passive"))
      (node (ref "R4") (pin "2") (pinfunction "2_2") (pintype "passive"))
      (node (ref "R7") (pin "2") (pinfunction "2_2") (pintype "passive"))
      (node (ref "R8") (pin "2") (pinfunction "2_2") (pintype "passive"))
      (node (ref "SV10") (pin "1") (pinfunction "1_1") (pintype "passive"))
      (node (ref "SV21") (pin "1") (pinfunction "1_1") (pintype "passive"))
      (node (ref "U15") (pin "44") (pinfunction "DVCC_2_44") (pintype "passive"))
      (node (ref "U15") (pin "50") (pinfunction "DVCC_50") (pintype "passive"))
      (node (ref "U18") (pin "18") (pinfunction "*STANDBY_18") (pintype "passive"))
      (node (ref "U18") (pin "23") (pinfunction "DVDD_23") (pintype "passive"))
      (node (ref "U18") (pin "5") (pinfunction "*SYNC_5") (pintype "passive"))
      (node (ref "U18") (pin "6") (pinfunction "*RESET_6") (pintype "passive"))
      (node (ref "U19") (pin "44") (pinfunction "DVCC_2_44") (pintype "passive"))
      (node (ref "U19") (pin "50") (pinfunction "DVCC_50") (pintype "passive"))
      (node (ref "U21") (pin "18") (pinfunction "*STANDBY_18") (pintype "passive"))
      (node (ref "U21") (pin "23") (pinfunction "DVDD_23") (pintype "passive"))
      (node (ref "U21") (pin "5") (pinfunction "*SYNC_5") (pintype "passive"))
      (node (ref "U21") (pin "6") (pinfunction "*RESET_6") (pintype "passive"))
      (node (ref "U22") (pin "1") (pinfunction "VBAT_1") (pintype "input"))
      (node (ref "U22") (pin "13") (pinfunction "VDDA_13") (pintype "power_in"))
      (node (ref "U22") (pin "19") (pinfunction "VDD_4_19") (pintype "power_in"))
      (node (ref "U22") (pin "32") (pinfunction "VDD_1_32") (pintype "power_in"))
      (node (ref "U22") (pin "48") (pinfunction "VDD_2_48") (pintype "power_in"))
      (node (ref "U22") (pin "64") (pinfunction "VDD_3_64") (pintype "power_in"))
      (node (ref "U23") (pin "18") (pinfunction "*STANDBY_18") (pintype "passive"))
      (node (ref "U23") (pin "23") (pinfunction "DVDD_23") (pintype "passive"))
      (node (ref "U23") (pin "5") (pinfunction "*SYNC_5") (pintype "passive"))
      (node (ref "U23") (pin "6") (pinfunction "*RESET_6") (pintype "passive"))
      (node (ref "U24") (pin "18") (pinfunction "*STANDBY_18") (pintype "passive"))
      (node (ref "U24") (pin "23") (pinfunction "DVDD_23") (pintype "passive"))
      (node (ref "U24") (pin "5") (pinfunction "*SYNC_5") (pintype "passive"))
      (node (ref "U24") (pin "6") (pinfunction "*RESET_6") (pintype "passive"))
      (node (ref "U25") (pin "18") (pinfunction "*STANDBY_18") (pintype "passive"))
      (node (ref "U25") (pin "23") (pinfunction "DVDD_23") (pintype "passive"))
      (node (ref "U25") (pin "5") (pinfunction "*SYNC_5") (pintype "passive"))
      (node (ref "U25") (pin "6") (pinfunction "*RESET_6") (pintype "passive"))
      (node (ref "U26") (pin "18") (pinfunction "*STANDBY_18") (pintype "passive"))
      (node (ref "U26") (pin "23") (pinfunction "DVDD_23") (pintype "passive"))
      (node (ref "U26") (pin "5") (pinfunction "*SYNC_5") (pintype "passive"))
      (node (ref "U26") (pin "6") (pinfunction "*RESET_6") (pintype "passive"))
      (node (ref "U27") (pin "18") (pinfunction "*STANDBY_18") (pintype "passive"))
      (node (ref "U27") (pin "23") (pinfunction "DVDD_23") (pintype "passive"))
      (node (ref "U27") (pin "5") (pinfunction "*SYNC_5") (pintype "passive"))
      (node (ref "U27") (pin "6") (pinfunction "*RESET_6") (pintype "passive"))
      (node (ref "U28") (pin "18") (pinfunction "*STANDBY_18") (pintype "passive"))
      (node (ref "U28") (pin "23") (pinfunction "DVDD_23") (pintype "passive"))
      (node (ref "U28") (pin "5") (pinfunction "*SYNC_5") (pintype "passive"))
      (node (ref "U28") (pin "6") (pinfunction "*RESET_6") (pintype "passive"))
      (node (ref "U38") (pin "18") (pinfunction "*STANDBY_18") (pintype "passive"))
      (node (ref "U38") (pin "23") (pinfunction "DVDD_23") (pintype "passive"))
      (node (ref "U38") (pin "5") (pinfunction "*SYNC_5") (pintype "passive"))
      (node (ref "U38") (pin "6") (pinfunction "*RESET_6") (pintype "passive"))
      (node (ref "U39") (pin "18") (pinfunction "*STANDBY_18") (pintype "passive"))
      (node (ref "U39") (pin "23") (pinfunction "DVDD_23") (pintype "passive"))
      (node (ref "U39") (pin "5") (pinfunction "*SYNC_5") (pintype "passive"))
      (node (ref "U39") (pin "6") (pinfunction "*RESET_6") (pintype "passive"))
      (node (ref "U40") (pin "1") (pinfunction "VBAT_1") (pintype "input"))
      (node (ref "U40") (pin "13") (pinfunction "VDDA_13") (pintype "power_in"))
      (node (ref "U40") (pin "19") (pinfunction "VDD_4_19") (pintype "power_in"))
      (node (ref "U40") (pin "32") (pinfunction "VDD_1_32") (pintype "power_in"))
      (node (ref "U40") (pin "48") (pinfunction "VDD_2_48") (pintype "power_in"))
      (node (ref "U40") (pin "64") (pinfunction "VDD_3_64") (pintype "power_in"))
      (node (ref "U41") (pin "18") (pinfunction "*STANDBY_18") (pintype "passive"))
      (node (ref "U41") (pin "23") (pinfunction "DVDD_23") (pintype "passive"))
      (node (ref "U41") (pin "5") (pinfunction "*SYNC_5") (pintype "passive"))
      (node (ref "U41") (pin "6") (pinfunction "*RESET_6") (pintype "passive"))
      (node (ref "U42") (pin "18") (pinfunction "*STANDBY_18") (pintype "passive"))
      (node (ref "U42") (pin "23") (pinfunction "DVDD_23") (pintype "passive"))
      (node (ref "U42") (pin "5") (pinfunction "*SYNC_5") (pintype "passive"))
      (node (ref "U42") (pin "6") (pinfunction "*RESET_6") (pintype "passive"))
      (node (ref "U43") (pin "18") (pinfunction "*STANDBY_18") (pintype "passive"))
      (node (ref "U43") (pin "23") (pinfunction "DVDD_23") (pintype "passive"))
      (node (ref "U43") (pin "5") (pinfunction "*SYNC_5") (pintype "passive"))
      (node (ref "U43") (pin "6") (pinfunction "*RESET_6") (pintype "passive"))
      (node (ref "U44") (pin "18") (pinfunction "*STANDBY_18") (pintype "passive"))
      (node (ref "U44") (pin "23") (pinfunction "DVDD_23") (pintype "passive"))
      (node (ref "U44") (pin "5") (pinfunction "*SYNC_5") (pintype "passive"))
      (node (ref "U44") (pin "6") (pinfunction "*RESET_6") (pintype "passive"))
      (node (ref "U45") (pin "18") (pinfunction "*STANDBY_18") (pintype "passive"))
      (node (ref "U45") (pin "23") (pinfunction "DVDD_23") (pintype "passive"))
      (node (ref "U45") (pin "5") (pinfunction "*SYNC_5") (pintype "passive"))
      (node (ref "U45") (pin "6") (pinfunction "*RESET_6") (pintype "passive"))
      (node (ref "U46") (pin "18") (pinfunction "*STANDBY_18") (pintype "passive"))
      (node (ref "U46") (pin "23") (pinfunction "DVDD_23") (pintype "passive"))
      (node (ref "U46") (pin "5") (pinfunction "*SYNC_5") (pintype "passive"))
      (node (ref "U46") (pin "6") (pinfunction "*RESET_6") (pintype "passive"))
      (node (ref "U5") (pin "49") (pinfunction "VDRIVE_49") (pintype "passive"))
      (node (ref "U6") (pin "5") (pinfunction "VCC_5") (pintype "power_in"))
      (node (ref "U8") (pin "49") (pinfunction "VDRIVE_49") (pintype "passive"))
      (node (ref "U9") (pin "5") (pinfunction "VCC_5") (pintype "power_in"))
      (node (ref "Y3") (pin "4") (pinfunction "VCC_4") (pintype "bidirectional"))
      (node (ref "Y7") (pin "4") (pinfunction "VCC_4") (pintype "bidirectional"))
    )
    (net (code "167") (name "DVCC_CURR_LIM") (class "Default")
      (node (ref "LED3") (pin "A") (pinfunction "A_A") (pintype "passive"))
      (node (ref "R3") (pin "1") (pinfunction "1_1") (pintype "passive"))
    )
    (net (code "168") (name "GND") (class "Default")
      (node (ref "C1") (pin "-") (pinfunction "-_-") (pintype "passive"))
      (node (ref "C10") (pin "-") (pinfunction "-_-") (pintype "passive"))
      (node (ref "C102") (pin "2") (pinfunction "2_2") (pintype "passive"))
      (node (ref "C103") (pin "2") (pinfunction "2_2") (pintype "passive"))
      (node (ref "C107") (pin "2") (pinfunction "2_2") (pintype "passive"))
      (node (ref "C109") (pin "2") (pinfunction "2_2") (pintype "passive"))
      (node (ref "C11") (pin "1") (pinfunction "1_1") (pintype "passive"))
      (node (ref "C111") (pin "2") (pinfunction "2_2") (pintype "passive"))
      (node (ref "C113") (pin "2") (pinfunction "2_2") (pintype "passive"))
      (node (ref "C114") (pin "2") (pinfunction "2_2") (pintype "passive"))
      (node (ref "C116") (pin "2") (pinfunction "2_2") (pintype "passive"))
      (node (ref "C117") (pin "2") (pinfunction "2_2") (pintype "passive"))
      (node (ref "C12") (pin "1") (pinfunction "1_1") (pintype "passive"))
      (node (ref "C13") (pin "2") (pinfunction "2_2") (pintype "passive"))
      (node (ref "C136") (pin "2") (pinfunction "2_2") (pintype "passive"))
      (node (ref "C137") (pin "2") (pinfunction "2_2") (pintype "passive"))
      (node (ref "C14") (pin "2") (pinfunction "2_2") (pintype "passive"))
      (node (ref "C141") (pin "2") (pinfunction "2_2") (pintype "passive"))
      (node (ref "C143") (pin "2") (pinfunction "2_2") (pintype "passive"))
      (node (ref "C145") (pin "2") (pinfunction "2_2") (pintype "passive"))
      (node (ref "C147") (pin "2") (pinfunction "2_2") (pintype "passive"))
      (node (ref "C148") (pin "2") (pinfunction "2_2") (pintype "passive"))
      (node (ref "C15") (pin "2") (pinfunction "2_2") (pintype "passive"))
      (node (ref "C150") (pin "2") (pinfunction "2_2") (pintype "passive"))
      (node (ref "C151") (pin "2") (pinfunction "2_2") (pintype "passive"))
      (node (ref "C16") (pin "2") (pinfunction "2_2") (pintype "passive"))
      (node (ref "C17") (pin "2") (pinfunction "2_2") (pintype "passive"))
      (node (ref "C18") (pin "2") (pinfunction "2_2") (pintype "passive"))
      (node (ref "C19") (pin "2") (pinfunction "2_2") (pintype "passive"))
      (node (ref "C2") (pin "-") (pinfunction "-_-") (pintype "passive"))
      (node (ref "C20") (pin "2") (pinfunction "2_2") (pintype "passive"))
      (node (ref "C21") (pin "-") (pinfunction "-_-") (pintype "passive"))
      (node (ref "C22") (pin "-") (pinfunction "-_-") (pintype "passive"))
      (node (ref "C23") (pin "-") (pinfunction "-_-") (pintype "passive"))
      (node (ref "C24") (pin "-") (pinfunction "-_-") (pintype "passive"))
      (node (ref "C25") (pin "+") (pinfunction "+_+") (pintype "passive"))
      (node (ref "C26") (pin "+") (pinfunction "+_+") (pintype "passive"))
      (node (ref "C27") (pin "-") (pinfunction "-_-") (pintype "passive"))
      (node (ref "C28") (pin "-") (pinfunction "-_-") (pintype "passive"))
      (node (ref "C29") (pin "-") (pinfunction "-_-") (pintype "passive"))
      (node (ref "C3") (pin "-") (pinfunction "-_-") (pintype "passive"))
      (node (ref "C30") (pin "-") (pinfunction "-_-") (pintype "passive"))
      (node (ref "C32") (pin "2") (pinfunction "2_2") (pintype "passive"))
      (node (ref "C33") (pin "2") (pinfunction "2_2") (pintype "passive"))
      (node (ref "C35") (pin "2") (pinfunction "2_2") (pintype "passive"))
      (node (ref "C36") (pin "2") (pinfunction "2_2") (pintype "passive"))
      (node (ref "C38") (pin "2") (pinfunction "2_2") (pintype "passive"))
      (node (ref "C39") (pin "2") (pinfunction "2_2") (pintype "passive"))
      (node (ref "C4") (pin "-") (pinfunction "-_-") (pintype "passive"))
      (node (ref "C40") (pin "2") (pinfunction "2_2") (pintype "passive"))
      (node (ref "C41") (pin "2") (pinfunction "2_2") (pintype "passive"))
      (node (ref "C42") (pin "2") (pinfunction "2_2") (pintype "passive"))
      (node (ref "C43") (pin "2") (pinfunction "2_2") (pintype "passive"))
      (node (ref "C44") (pin "2") (pinfunction "2_2") (pintype "passive"))
      (node (ref "C45") (pin "1") (pinfunction "1_1") (pintype "passive"))
      (node (ref "C46") (pin "2") (pinfunction "2_2") (pintype "passive"))
      (node (ref "C47") (pin "2") (pinfunction "2_2") (pintype "passive"))
      (node (ref "C48") (pin "2") (pinfunction "2_2") (pintype "passive"))
      (node (ref "C49") (pin "2") (pinfunction "2_2") (pintype "passive"))
      (node (ref "C5") (pin "-") (pinfunction "-_-") (pintype "passive"))
      (node (ref "C50") (pin "2") (pinfunction "2_2") (pintype "passive"))
      (node (ref "C51") (pin "2") (pinfunction "2_2") (pintype "passive"))
      (node (ref "C52") (pin "1") (pinfunction "1_1") (pintype "passive"))
      (node (ref "C53") (pin "1") (pinfunction "1_1") (pintype "passive"))
      (node (ref "C54") (pin "2") (pinfunction "2_2") (pintype "passive"))
      (node (ref "C55") (pin "2") (pinfunction "2_2") (pintype "passive"))
      (node (ref "C56") (pin "2") (pinfunction "2_2") (pintype "passive"))
      (node (ref "C57") (pin "2") (pinfunction "2_2") (pintype "passive"))
      (node (ref "C58") (pin "2") (pinfunction "2_2") (pintype "passive"))
      (node (ref "C59") (pin "2") (pinfunction "2_2") (pintype "passive"))
      (node (ref "C6") (pin "-") (pinfunction "-_-") (pintype "passive"))
      (node (ref "C60") (pin "2") (pinfunction "2_2") (pintype "passive"))
      (node (ref "C61") (pin "2") (pinfunction "2_2") (pintype "passive"))
      (node (ref "C62") (pin "1") (pinfunction "1_1") (pintype "passive"))
      (node (ref "C63") (pin "2") (pinfunction "2_2") (pintype "passive"))
      (node (ref "C64") (pin "2") (pinfunction "2_2") (pintype "passive"))
      (node (ref "C66") (pin "2") (pinfunction "2_2") (pintype "passive"))
      (node (ref "C67") (pin "2") (pinfunction "2_2") (pintype "passive"))
      (node (ref "C69") (pin "2") (pinfunction "2_2") (pintype "passive"))
      (node (ref "C7") (pin "+") (pinfunction "+_+") (pintype "passive"))
      (node (ref "C70") (pin "2") (pinfunction "2_2") (pintype "passive"))
      (node (ref "C71") (pin "2") (pinfunction "2_2") (pintype "passive"))
      (node (ref "C72") (pin "2") (pinfunction "2_2") (pintype "passive"))
      (node (ref "C73") (pin "2") (pinfunction "2_2") (pintype "passive"))
      (node (ref "C74") (pin "2") (pinfunction "2_2") (pintype "passive"))
      (node (ref "C75") (pin "2") (pinfunction "2_2") (pintype "passive"))
      (node (ref "C76") (pin "1") (pinfunction "1_1") (pintype "passive"))
      (node (ref "C77") (pin "2") (pinfunction "2_2") (pintype "passive"))
      (node (ref "C78") (pin "2") (pinfunction "2_2") (pintype "passive"))
      (node (ref "C79") (pin "2") (pinfunction "2_2") (pintype "passive"))
      (node (ref "C8") (pin "+") (pinfunction "+_+") (pintype "passive"))
      (node (ref "C80") (pin "2") (pinfunction "2_2") (pintype "passive"))
      (node (ref "C81") (pin "2") (pinfunction "2_2") (pintype "passive"))
      (node (ref "C82") (pin "2") (pinfunction "2_2") (pintype "passive"))
      (node (ref "C83") (pin "1") (pinfunction "1_1") (pintype "passive"))
      (node (ref "C9") (pin "-") (pinfunction "-_-") (pintype "passive"))
      (node (ref "J1") (pin "2") (pinfunction "2_2") (pintype "input"))
      (node (ref "J10") (pin "2") (pinfunction "2_2") (pintype "input"))
      (node (ref "J11") (pin "2") (pinfunction "2_2") (pintype "input"))
      (node (ref "J12") (pin "2") (pinfunction "2_2") (pintype "input"))
      (node (ref "J13") (pin "2") (pinfunction "2_2") (pintype "input"))
      (node (ref "J14") (pin "2") (pinfunction "2_2") (pintype "input"))
      (node (ref "J15") (pin "2") (pinfunction "2_2") (pintype "input"))
      (node (ref "J16") (pin "2") (pinfunction "2_2") (pintype "input"))
      (node (ref "J17") (pin "2") (pinfunction "2_2") (pintype "input"))
      (node (ref "J18") (pin "2") (pinfunction "2_2") (pintype "input"))
      (node (ref "J19") (pin "2") (pinfunction "2_2") (pintype "input"))
      (node (ref "J2") (pin "2") (pinfunction "2_2") (pintype "input"))
      (node (ref "J20") (pin "2") (pinfunction "2_2") (pintype "input"))
      (node (ref "J21") (pin "2") (pinfunction "2_2") (pintype "input"))
      (node (ref "J22") (pin "2") (pinfunction "2_2") (pintype "input"))
      (node (ref "J23") (pin "2") (pinfunction "2_2") (pintype "input"))
      (node (ref "J24") (pin "2") (pinfunction "2_2") (pintype "input"))
      (node (ref "J25") (pin "2") (pinfunction "2_2") (pintype "input"))
      (node (ref "J26") (pin "2") (pinfunction "2_2") (pintype "input"))
      (node (ref "J27") (pin "2") (pinfunction "2_2") (pintype "input"))
      (node (ref "J28") (pin "2") (pinfunction "2_2") (pintype "input"))
      (node (ref "J29") (pin "2") (pinfunction "2_2") (pintype "input"))
      (node (ref "J3") (pin "2") (pinfunction "2_2") (pintype "input"))
      (node (ref "J30") (pin "2") (pinfunction "2_2") (pintype "input"))
      (node (ref "J31") (pin "2") (pinfunction "2_2") (pintype "input"))
      (node (ref "J32") (pin "2") (pinfunction "2_2") (pintype "input"))
      (node (ref "J33") (pin "2") (pinfunction "2_2") (pintype "passive"))
      (node (ref "J34") (pin "2") (pinfunction "2_2") (pintype "passive"))
      (node (ref "J35") (pin "2") (pinfunction "2_2") (pintype "passive"))
      (node (ref "J36") (pin "2") (pinfunction "2_2") (pintype "passive"))
      (node (ref "J37") (pin "2") (pinfunction "2_2") (pintype "passive"))
      (node (ref "J38") (pin "2") (pinfunction "2_2") (pintype "passive"))
      (node (ref "J39") (pin "2") (pinfunction "2_2") (pintype "passive"))
      (node (ref "J4") (pin "2") (pinfunction "2_2") (pintype "input"))
      (node (ref "J40") (pin "2") (pinfunction "2_2") (pintype "passive"))
      (node (ref "J41") (pin "2") (pinfunction "2_2") (pintype "passive"))
      (node (ref "J42") (pin "2") (pinfunction "2_2") (pintype "passive"))
      (node (ref "J43") (pin "2") (pinfunction "2_2") (pintype "passive"))
      (node (ref "J44") (pin "2") (pinfunction "2_2") (pintype "passive"))
      (node (ref "J45") (pin "2") (pinfunction "2_2") (pintype "passive"))
      (node (ref "J46") (pin "2") (pinfunction "2_2") (pintype "passive"))
      (node (ref "J47") (pin "2") (pinfunction "2_2") (pintype "passive"))
      (node (ref "J48") (pin "2") (pinfunction "2_2") (pintype "passive"))
      (node (ref "J49") (pin "2") (pinfunction "2_2") (pintype "passive"))
      (node (ref "J5") (pin "2") (pinfunction "2_2") (pintype "input"))
      (node (ref "J50") (pin "2") (pinfunction "2_2") (pintype "passive"))
      (node (ref "J51") (pin "2") (pinfunction "2_2") (pintype "passive"))
      (node (ref "J52") (pin "2") (pinfunction "2_2") (pintype "passive"))
      (node (ref "J53") (pin "2") (pinfunction "2_2") (pintype "passive"))
      (node (ref "J54") (pin "2") (pinfunction "2_2") (pintype "passive"))
      (node (ref "J55") (pin "2") (pinfunction "2_2") (pintype "passive"))
      (node (ref "J56") (pin "2") (pinfunction "2_2") (pintype "passive"))
      (node (ref "J57") (pin "2") (pinfunction "2_2") (pintype "passive"))
      (node (ref "J58") (pin "2") (pinfunction "2_2") (pintype "passive"))
      (node (ref "J59") (pin "2") (pinfunction "2_2") (pintype "passive"))
      (node (ref "J6") (pin "2") (pinfunction "2_2") (pintype "input"))
      (node (ref "J60") (pin "2") (pinfunction "2_2") (pintype "passive"))
      (node (ref "J61") (pin "2") (pinfunction "2_2") (pintype "passive"))
      (node (ref "J62") (pin "2") (pinfunction "2_2") (pintype "passive"))
      (node (ref "J63") (pin "2") (pinfunction "2_2") (pintype "passive"))
      (node (ref "J64") (pin "2") (pinfunction "2_2") (pintype "passive"))
      (node (ref "J7") (pin "2") (pinfunction "2_2") (pintype "input"))
      (node (ref "J8") (pin "2") (pinfunction "2_2") (pintype "input"))
      (node (ref "J9") (pin "2") (pinfunction "2_2") (pintype "input"))
      (node (ref "LED1") (pin "C") (pinfunction "C_C") (pintype "passive"))
      (node (ref "LED2") (pin "C") (pinfunction "C_C") (pintype "passive"))
      (node (ref "LED3") (pin "C") (pinfunction "C_C") (pintype "passive"))
      (node (ref "LED4") (pin "C") (pinfunction "C_C") (pintype "passive"))
      (node (ref "LED5") (pin "C") (pinfunction "C_C") (pintype "passive"))
      (node (ref "PL1") (pin "15") (pinfunction "S_15") (pintype "passive"))
      (node (ref "PL1") (pin "17") (pinfunction "S_17") (pintype "passive"))
      (node (ref "PL1") (pin "18") (pinfunction "S_18") (pintype "passive"))
      (node (ref "PL1") (pin "19") (pinfunction "S_19") (pintype "passive"))
      (node (ref "PL1") (pin "24") (pinfunction "S_24") (pintype "passive"))
      (node (ref "PL1") (pin "3") (pinfunction "S_3") (pintype "passive"))
      (node (ref "PL1") (pin "5") (pinfunction "S_5") (pintype "passive"))
      (node (ref "PL1") (pin "7") (pinfunction "S_7") (pintype "passive"))
      (node (ref "S1") (pin "3") (pinfunction "3_3") (pintype "passive"))
      (node (ref "S2") (pin "3") (pinfunction "P_3") (pintype "passive"))
      (node (ref "S2") (pin "4") (pinfunction "P1_4") (pintype "passive"))
      (node (ref "S3") (pin "3") (pinfunction "P_3") (pintype "passive"))
      (node (ref "S3") (pin "4") (pinfunction "P1_4") (pintype "passive"))
      (node (ref "S6") (pin "1") (pinfunction "S_1") (pintype "passive"))
      (node (ref "S6") (pin "2") (pinfunction "S1_2") (pintype "passive"))
      (node (ref "S8") (pin "1") (pinfunction "S_1") (pintype "passive"))
      (node (ref "S8") (pin "2") (pinfunction "S1_2") (pintype "passive"))
      (node (ref "SV1") (pin "14") (pinfunction "14_14") (pintype "passive"))
      (node (ref "SV1") (pin "20") (pinfunction "20_20") (pintype "passive"))
      (node (ref "SV1") (pin "25") (pinfunction "25_25") (pintype "passive"))
      (node (ref "SV1") (pin "30") (pinfunction "30_30") (pintype "passive"))
      (node (ref "SV1") (pin "34") (pinfunction "34_34") (pintype "passive"))
      (node (ref "SV1") (pin "39") (pinfunction "39_39") (pintype "passive"))
      (node (ref "SV1") (pin "6") (pinfunction "6_6") (pintype "passive"))
      (node (ref "SV1") (pin "9") (pinfunction "9_9") (pintype "passive"))
      (node (ref "SV10") (pin "2") (pinfunction "2_2") (pintype "passive"))
      (node (ref "SV10") (pin "5") (pinfunction "5_5") (pintype "passive"))
      (node (ref "SV21") (pin "2") (pinfunction "2_2") (pintype "passive"))
      (node (ref "SV21") (pin "5") (pinfunction "5_5") (pintype "passive"))
      (node (ref "U1") (pin "10") (pinfunction "10_10") (pintype "passive"))
      (node (ref "U1") (pin "12") (pinfunction "12_12") (pintype "passive"))
      (node (ref "U1") (pin "14") (pinfunction "14_14") (pintype "passive"))
      (node (ref "U1") (pin "16") (pinfunction "16_16") (pintype "passive"))
      (node (ref "U1") (pin "18") (pinfunction "18_18") (pintype "passive"))
      (node (ref "U1") (pin "2") (pinfunction "2_2") (pintype "passive"))
      (node (ref "U1") (pin "20") (pinfunction "20_20") (pintype "passive"))
      (node (ref "U1") (pin "22") (pinfunction "22_22") (pintype "passive"))
      (node (ref "U1") (pin "24") (pinfunction "24_24") (pintype "passive"))
      (node (ref "U1") (pin "26") (pinfunction "26_26") (pintype "passive"))
      (node (ref "U1") (pin "28") (pinfunction "28_28") (pintype "passive"))
      (node (ref "U1") (pin "30") (pinfunction "30_30") (pintype "passive"))
      (node (ref "U1") (pin "32") (pinfunction "32_32") (pintype "passive"))
      (node (ref "U1") (pin "4") (pinfunction "4_4") (pintype "passive"))
      (node (ref "U1") (pin "6") (pinfunction "6_6") (pintype "passive"))
      (node (ref "U1") (pin "8") (pinfunction "8_8") (pintype "passive"))
      (node (ref "U15") (pin "19") (pinfunction "SIGGND1_19") (pintype "passive"))
      (node (ref "U15") (pin "38") (pinfunction "SIGGND0_38") (pintype "passive"))
      (node (ref "U15") (pin "4") (pinfunction "*BIN/2SCOMP_4") (pintype "passive"))
      (node (ref "U15") (pin "43") (pinfunction "DGND_2_43") (pintype "passive"))
      (node (ref "U15") (pin "51") (pinfunction "DGND_51") (pintype "passive"))
      (node (ref "U15") (pin "52") (pinfunction "AGND_52") (pintype "passive"))
      (node (ref "U16") (pin "4") (pinfunction "GND_4") (pintype "passive"))
      (node (ref "U18") (pin "15") (pinfunction "REF_IN(-)_15") (pintype "passive"))
      (node (ref "U18") (pin "24") (pinfunction "DGND_24") (pintype "passive"))
      (node (ref "U18") (pin "4") (pinfunction "POL_4") (pintype "passive"))
      (node (ref "U18") (pin "8") (pinfunction "AGND_8") (pintype "passive"))
      (node (ref "U19") (pin "19") (pinfunction "SIGGND1_19") (pintype "passive"))
      (node (ref "U19") (pin "38") (pinfunction "SIGGND0_38") (pintype "passive"))
      (node (ref "U19") (pin "4") (pinfunction "*BIN/2SCOMP_4") (pintype "passive"))
      (node (ref "U19") (pin "43") (pinfunction "DGND_2_43") (pintype "passive"))
      (node (ref "U19") (pin "51") (pinfunction "DGND_51") (pintype "passive"))
      (node (ref "U19") (pin "52") (pinfunction "AGND_52") (pintype "passive"))
      (node (ref "U2") (pin "10") (pinfunction "10_10") (pintype "passive"))
      (node (ref "U2") (pin "12") (pinfunction "12_12") (pintype "passive"))
      (node (ref "U2") (pin "14") (pinfunction "14_14") (pintype "passive"))
      (node (ref "U2") (pin "16") (pinfunction "16_16") (pintype "passive"))
      (node (ref "U2") (pin "18") (pinfunction "18_18") (pintype "passive"))
      (node (ref "U2") (pin "2") (pinfunction "2_2") (pintype "passive"))
      (node (ref "U2") (pin "20") (pinfunction "20_20") (pintype "passive"))
      (node (ref "U2") (pin "22") (pinfunction "22_22") (pintype "passive"))
      (node (ref "U2") (pin "24") (pinfunction "24_24") (pintype "passive"))
      (node (ref "U2") (pin "26") (pinfunction "26_26") (pintype "passive"))
      (node (ref "U2") (pin "28") (pinfunction "28_28") (pintype "passive"))
      (node (ref "U2") (pin "30") (pinfunction "30_30") (pintype "passive"))
      (node (ref "U2") (pin "32") (pinfunction "32_32") (pintype "passive"))
      (node (ref "U2") (pin "4") (pinfunction "4_4") (pintype "passive"))
      (node (ref "U2") (pin "6") (pinfunction "6_6") (pintype "passive"))
      (node (ref "U2") (pin "8") (pinfunction "8_8") (pintype "passive"))
      (node (ref "U20") (pin "4") (pinfunction "GND_4") (pintype "passive"))
      (node (ref "U21") (pin "15") (pinfunction "REF_IN(-)_15") (pintype "passive"))
      (node (ref "U21") (pin "24") (pinfunction "DGND_24") (pintype "passive"))
      (node (ref "U21") (pin "4") (pinfunction "POL_4") (pintype "passive"))
      (node (ref "U21") (pin "8") (pinfunction "AGND_8") (pintype "passive"))
      (node (ref "U22") (pin "12") (pinfunction "VSSA_12") (pintype "passive"))
      (node (ref "U22") (pin "18") (pinfunction "VSS_4_18") (pintype "passive"))
      (node (ref "U22") (pin "31") (pinfunction "VSS_1_31") (pintype "passive"))
      (node (ref "U22") (pin "47") (pinfunction "VSS_2_47") (pintype "passive"))
      (node (ref "U22") (pin "63") (pinfunction "VSS_3_63") (pintype "passive"))
      (node (ref "U23") (pin "15") (pinfunction "REF_IN(-)_15") (pintype "passive"))
      (node (ref "U23") (pin "24") (pinfunction "DGND_24") (pintype "passive"))
      (node (ref "U23") (pin "4") (pinfunction "POL_4") (pintype "passive"))
      (node (ref "U23") (pin "8") (pinfunction "AGND_8") (pintype "passive"))
      (node (ref "U24") (pin "15") (pinfunction "REF_IN(-)_15") (pintype "passive"))
      (node (ref "U24") (pin "24") (pinfunction "DGND_24") (pintype "passive"))
      (node (ref "U24") (pin "4") (pinfunction "POL_4") (pintype "passive"))
      (node (ref "U24") (pin "8") (pinfunction "AGND_8") (pintype "passive"))
      (node (ref "U25") (pin "15") (pinfunction "REF_IN(-)_15") (pintype "passive"))
      (node (ref "U25") (pin "24") (pinfunction "DGND_24") (pintype "passive"))
      (node (ref "U25") (pin "4") (pinfunction "POL_4") (pintype "passive"))
      (node (ref "U25") (pin "8") (pinfunction "AGND_8") (pintype "passive"))
      (node (ref "U26") (pin "15") (pinfunction "REF_IN(-)_15") (pintype "passive"))
      (node (ref "U26") (pin "24") (pinfunction "DGND_24") (pintype "passive"))
      (node (ref "U26") (pin "4") (pinfunction "POL_4") (pintype "passive"))
      (node (ref "U26") (pin "8") (pinfunction "AGND_8") (pintype "passive"))
      (node (ref "U27") (pin "15") (pinfunction "REF_IN(-)_15") (pintype "passive"))
      (node (ref "U27") (pin "24") (pinfunction "DGND_24") (pintype "passive"))
      (node (ref "U27") (pin "4") (pinfunction "POL_4") (pintype "passive"))
      (node (ref "U27") (pin "8") (pinfunction "AGND_8") (pintype "passive"))
      (node (ref "U28") (pin "15") (pinfunction "REF_IN(-)_15") (pintype "passive"))
      (node (ref "U28") (pin "24") (pinfunction "DGND_24") (pintype "passive"))
      (node (ref "U28") (pin "4") (pinfunction "POL_4") (pintype "passive"))
      (node (ref "U28") (pin "8") (pinfunction "AGND_8") (pintype "passive"))
      (node (ref "U38") (pin "15") (pinfunction "REF_IN(-)_15") (pintype "passive"))
      (node (ref "U38") (pin "24") (pinfunction "DGND_24") (pintype "passive"))
      (node (ref "U38") (pin "4") (pinfunction "POL_4") (pintype "passive"))
      (node (ref "U38") (pin "8") (pinfunction "AGND_8") (pintype "passive"))
      (node (ref "U39") (pin "15") (pinfunction "REF_IN(-)_15") (pintype "passive"))
      (node (ref "U39") (pin "24") (pinfunction "DGND_24") (pintype "passive"))
      (node (ref "U39") (pin "4") (pinfunction "POL_4") (pintype "passive"))
      (node (ref "U39") (pin "8") (pinfunction "AGND_8") (pintype "passive"))
      (node (ref "U4") (pin "4") (pinfunction "GND_4") (pintype "passive"))
      (node (ref "U40") (pin "12") (pinfunction "VSSA_12") (pintype "passive"))
      (node (ref "U40") (pin "18") (pinfunction "VSS_4_18") (pintype "passive"))
      (node (ref "U40") (pin "31") (pinfunction "VSS_1_31") (pintype "passive"))
      (node (ref "U40") (pin "47") (pinfunction "VSS_2_47") (pintype "passive"))
      (node (ref "U40") (pin "63") (pinfunction "VSS_3_63") (pintype "passive"))
      (node (ref "U41") (pin "15") (pinfunction "REF_IN(-)_15") (pintype "passive"))
      (node (ref "U41") (pin "24") (pinfunction "DGND_24") (pintype "passive"))
      (node (ref "U41") (pin "4") (pinfunction "POL_4") (pintype "passive"))
      (node (ref "U41") (pin "8") (pinfunction "AGND_8") (pintype "passive"))
      (node (ref "U42") (pin "15") (pinfunction "REF_IN(-)_15") (pintype "passive"))
      (node (ref "U42") (pin "24") (pinfunction "DGND_24") (pintype "passive"))
      (node (ref "U42") (pin "4") (pinfunction "POL_4") (pintype "passive"))
      (node (ref "U42") (pin "8") (pinfunction "AGND_8") (pintype "passive"))
      (node (ref "U43") (pin "15") (pinfunction "REF_IN(-)_15") (pintype "passive"))
      (node (ref "U43") (pin "24") (pinfunction "DGND_24") (pintype "passive"))
      (node (ref "U43") (pin "4") (pinfunction "POL_4") (pintype "passive"))
      (node (ref "U43") (pin "8") (pinfunction "AGND_8") (pintype "passive"))
      (node (ref "U44") (pin "15") (pinfunction "REF_IN(-)_15") (pintype "passive"))
      (node (ref "U44") (pin "24") (pinfunction "DGND_24") (pintype "passive"))
      (node (ref "U44") (pin "4") (pinfunction "POL_4") (pintype "passive"))
      (node (ref "U44") (pin "8") (pinfunction "AGND_8") (pintype "passive"))
      (node (ref "U45") (pin "15") (pinfunction "REF_IN(-)_15") (pintype "passive"))
      (node (ref "U45") (pin "24") (pinfunction "DGND_24") (pintype "passive"))
      (node (ref "U45") (pin "4") (pinfunction "POL_4") (pintype "passive"))
      (node (ref "U45") (pin "8") (pinfunction "AGND_8") (pintype "passive"))
      (node (ref "U46") (pin "15") (pinfunction "REF_IN(-)_15") (pintype "passive"))
      (node (ref "U46") (pin "24") (pinfunction "DGND_24") (pintype "passive"))
      (node (ref "U46") (pin "4") (pinfunction "POL_4") (pintype "passive"))
      (node (ref "U46") (pin "8") (pinfunction "AGND_8") (pintype "passive"))
      (node (ref "U5") (pin "1") (pinfunction "V4BGND_1") (pintype "passive"))
      (node (ref "U5") (pin "10") (pinfunction "V7BGND_10") (pintype "passive"))
      (node (ref "U5") (pin "11") (pinfunction "V7AGND_11") (pintype "passive"))
      (node (ref "U5") (pin "13") (pinfunction "V6AGND_13") (pintype "passive"))
      (node (ref "U5") (pin "16") (pinfunction "AGND_4_16") (pintype "passive"))
      (node (ref "U5") (pin "18") (pinfunction "V5AGND_18") (pintype "passive"))
      (node (ref "U5") (pin "20") (pinfunction "V4AGND_20") (pintype "passive"))
      (node (ref "U5") (pin "21") (pinfunction "V3AGND_21") (pintype "passive"))
      (node (ref "U5") (pin "23") (pinfunction "V2AGND_23") (pintype "passive"))
      (node (ref "U5") (pin "25") (pinfunction "V1AGND_25") (pintype "passive"))
      (node (ref "U5") (pin "27") (pinfunction "V0AGND_27") (pintype "passive"))
      (node (ref "U5") (pin "29") (pinfunction "AGND_29") (pintype "passive"))
      (node (ref "U5") (pin "3") (pinfunction "V5BGND_3") (pintype "passive"))
      (node (ref "U5") (pin "32") (pinfunction "REFGND_32") (pintype "passive"))
      (node (ref "U5") (pin "34") (pinfunction "REFINOUTGND_34") (pintype "passive"))
      (node (ref "U5") (pin "35") (pinfunction "REFSEL_35") (pintype "passive"))
      (node (ref "U5") (pin "37") (pinfunction "SEQEN_37") (pintype "passive"))
      (node (ref "U5") (pin "38") (pinfunction "HW_RNGSEL1_38") (pintype "passive"))
      (node (ref "U5") (pin "39") (pinfunction "HW_RNGSEL0_39") (pintype "passive"))
      (node (ref "U5") (pin "41") (pinfunction "DB0_41") (pintype "passive"))
      (node (ref "U5") (pin "42") (pinfunction "DB1_42") (pintype "passive"))
      (node (ref "U5") (pin "43") (pinfunction "DB2_43") (pintype "passive"))
      (node (ref "U5") (pin "44") (pinfunction "DB3_44") (pintype "passive"))
      (node (ref "U5") (pin "45") (pinfunction "DB4/*SER1W_45") (pintype "passive"))
      (node (ref "U5") (pin "46") (pinfunction "DB5/CRCEN_46") (pintype "passive"))
      (node (ref "U5") (pin "47") (pinfunction "DB6_47") (pintype "passive"))
      (node (ref "U5") (pin "48") (pinfunction "DB7_48") (pintype "passive"))
      (node (ref "U5") (pin "5") (pinfunction "AGND_2_5") (pintype "passive"))
      (node (ref "U5") (pin "50") (pinfunction "DGND_50") (pintype "passive"))
      (node (ref "U5") (pin "51") (pinfunction "REGGNDD_51") (pintype "passive"))
      (node (ref "U5") (pin "53") (pinfunction "DB8_53") (pintype "passive"))
      (node (ref "U5") (pin "54") (pinfunction "DB9_54") (pintype "passive"))
      (node (ref "U5") (pin "58") (pinfunction "DB13/OS0_58") (pintype "passive"))
      (node (ref "U5") (pin "59") (pinfunction "DB14/OS1_59") (pintype "passive"))
      (node (ref "U5") (pin "60") (pinfunction "DB15/OS2_60") (pintype "passive"))
      (node (ref "U5") (pin "61") (pinfunction "*WR/BURST_61") (pintype "passive"))
      (node (ref "U5") (pin "64") (pinfunction "CHSEL0_64") (pintype "passive"))
      (node (ref "U5") (pin "65") (pinfunction "CHSEL1_65") (pintype "passive"))
      (node (ref "U5") (pin "66") (pinfunction "CHSEL2_66") (pintype "passive"))
      (node (ref "U5") (pin "69") (pinfunction "REGGND_69") (pintype "passive"))
      (node (ref "U5") (pin "72") (pinfunction "AGND_3_72") (pintype "passive"))
      (node (ref "U5") (pin "74") (pinfunction "V0BGND_74") (pintype "passive"))
      (node (ref "U5") (pin "76") (pinfunction "V1BGND_76") (pintype "passive"))
      (node (ref "U5") (pin "78") (pinfunction "V2BGND_78") (pintype "passive"))
      (node (ref "U5") (pin "8") (pinfunction "V6BGND_8") (pintype "passive"))
      (node (ref "U5") (pin "80") (pinfunction "V3BGND_80") (pintype "passive"))
      (node (ref "U6") (pin "3") (pinfunction "GND_3") (pintype "passive"))
      (node (ref "U7") (pin "4") (pinfunction "GND_4") (pintype "passive"))
      (node (ref "U8") (pin "1") (pinfunction "V4BGND_1") (pintype "passive"))
      (node (ref "U8") (pin "10") (pinfunction "V7BGND_10") (pintype "passive"))
      (node (ref "U8") (pin "11") (pinfunction "V7AGND_11") (pintype "passive"))
      (node (ref "U8") (pin "13") (pinfunction "V6AGND_13") (pintype "passive"))
      (node (ref "U8") (pin "16") (pinfunction "AGND_4_16") (pintype "passive"))
      (node (ref "U8") (pin "18") (pinfunction "V5AGND_18") (pintype "passive"))
      (node (ref "U8") (pin "20") (pinfunction "V4AGND_20") (pintype "passive"))
      (node (ref "U8") (pin "21") (pinfunction "V3AGND_21") (pintype "passive"))
      (node (ref "U8") (pin "23") (pinfunction "V2AGND_23") (pintype "passive"))
      (node (ref "U8") (pin "25") (pinfunction "V1AGND_25") (pintype "passive"))
      (node (ref "U8") (pin "27") (pinfunction "V0AGND_27") (pintype "passive"))
      (node (ref "U8") (pin "29") (pinfunction "AGND_29") (pintype "passive"))
      (node (ref "U8") (pin "3") (pinfunction "V5BGND_3") (pintype "passive"))
      (node (ref "U8") (pin "32") (pinfunction "REFGND_32") (pintype "passive"))
      (node (ref "U8") (pin "34") (pinfunction "REFINOUTGND_34") (pintype "passive"))
      (node (ref "U8") (pin "35") (pinfunction "REFSEL_35") (pintype "passive"))
      (node (ref "U8") (pin "37") (pinfunction "SEQEN_37") (pintype "passive"))
      (node (ref "U8") (pin "38") (pinfunction "HW_RNGSEL1_38") (pintype "passive"))
      (node (ref "U8") (pin "39") (pinfunction "HW_RNGSEL0_39") (pintype "passive"))
      (node (ref "U8") (pin "41") (pinfunction "DB0_41") (pintype "passive"))
      (node (ref "U8") (pin "42") (pinfunction "DB1_42") (pintype "passive"))
      (node (ref "U8") (pin "43") (pinfunction "DB2_43") (pintype "passive"))
      (node (ref "U8") (pin "44") (pinfunction "DB3_44") (pintype "passive"))
      (node (ref "U8") (pin "45") (pinfunction "DB4/*SER1W_45") (pintype "passive"))
      (node (ref "U8") (pin "46") (pinfunction "DB5/CRCEN_46") (pintype "passive"))
      (node (ref "U8") (pin "47") (pinfunction "DB6_47") (pintype "passive"))
      (node (ref "U8") (pin "48") (pinfunction "DB7_48") (pintype "passive"))
      (node (ref "U8") (pin "5") (pinfunction "AGND_2_5") (pintype "passive"))
      (node (ref "U8") (pin "50") (pinfunction "DGND_50") (pintype "passive"))
      (node (ref "U8") (pin "51") (pinfunction "REGGNDD_51") (pintype "passive"))
      (node (ref "U8") (pin "53") (pinfunction "DB8_53") (pintype "passive"))
      (node (ref "U8") (pin "54") (pinfunction "DB9_54") (pintype "passive"))
      (node (ref "U8") (pin "58") (pinfunction "DB13/OS0_58") (pintype "passive"))
      (node (ref "U8") (pin "59") (pinfunction "DB14/OS1_59") (pintype "passive"))
      (node (ref "U8") (pin "60") (pinfunction "DB15/OS2_60") (pintype "passive"))
      (node (ref "U8") (pin "61") (pinfunction "*WR/BURST_61") (pintype "passive"))
      (node (ref "U8") (pin "64") (pinfunction "CHSEL0_64") (pintype "passive"))
      (node (ref "U8") (pin "65") (pinfunction "CHSEL1_65") (pintype "passive"))
      (node (ref "U8") (pin "66") (pinfunction "CHSEL2_66") (pintype "passive"))
      (node (ref "U8") (pin "69") (pinfunction "REGGND_69") (pintype "passive"))
      (node (ref "U8") (pin "72") (pinfunction "AGND_3_72") (pintype "passive"))
      (node (ref "U8") (pin "74") (pinfunction "V0BGND_74") (pintype "passive"))
      (node (ref "U8") (pin "76") (pinfunction "V1BGND_76") (pintype "passive"))
      (node (ref "U8") (pin "78") (pinfunction "V2BGND_78") (pintype "passive"))
      (node (ref "U8") (pin "8") (pinfunction "V6BGND_8") (pintype "passive"))
      (node (ref "U8") (pin "80") (pinfunction "V3BGND_80") (pintype "passive"))
      (node (ref "U9") (pin "3") (pinfunction "GND_3") (pintype "passive"))
      (node (ref "X1") (pin "3") (pinfunction "S_3") (pintype "passive"))
      (node (ref "Y3") (pin "2") (pinfunction "GND_2") (pintype "bidirectional"))
      (node (ref "Y4") (pin "2") (pinfunction "GND1_2") (pintype "bidirectional"))
      (node (ref "Y4") (pin "4") (pinfunction "GND2_4") (pintype "bidirectional"))
      (node (ref "Y7") (pin "2") (pinfunction "GND_2") (pintype "bidirectional"))
      (node (ref "Y8") (pin "2") (pinfunction "GND1_2") (pintype "bidirectional"))
      (node (ref "Y8") (pin "4") (pinfunction "GND2_4") (pintype "bidirectional"))
    )
    (net (code "169") (name "HB_CURR_LIM") (class "Default")
      (node (ref "LED1") (pin "A") (pinfunction "A_A") (pintype "passive"))
      (node (ref "R11") (pin "1") (pinfunction "1_1") (pintype "passive"))
    )
    (net (code "170") (name "HEARTBEAT") (class "Default")
      (node (ref "R11") (pin "2") (pinfunction "2_2") (pintype "passive"))
      (node (ref "SV1") (pin "3") (pinfunction "3_3") (pintype "passive"))
    )
    (net (code "171") (name "LC_1_CS0") (class "Default")
      (node (ref "U18") (pin "19") (pinfunction "*CS_19") (pintype "passive"))
      (node (ref "U22") (pin "14") (pinfunction "PA0-WKUP_14") (pintype "bidirectional"))
    )
    (net (code "172") (name "LC_1_CS1") (class "Default")
      (node (ref "U21") (pin "19") (pinfunction "*CS_19") (pintype "passive"))
      (node (ref "U22") (pin "15") (pinfunction "PA1_15") (pintype "bidirectional"))
    )
    (net (code "173") (name "LC_1_CS2") (class "Default")
      (node (ref "U22") (pin "16") (pinfunction "PA2_16") (pintype "bidirectional"))
      (node (ref "U23") (pin "19") (pinfunction "*CS_19") (pintype "passive"))
    )
    (net (code "174") (name "LC_1_CS3") (class "Default")
      (node (ref "U22") (pin "24") (pinfunction "PC4_24") (pintype "passive"))
      (node (ref "U24") (pin "19") (pinfunction "*CS_19") (pintype "passive"))
    )
    (net (code "175") (name "LC_1_CS4") (class "Default")
      (node (ref "U22") (pin "25") (pinfunction "PC5_25") (pintype "bidirectional"))
      (node (ref "U25") (pin "19") (pinfunction "*CS_19") (pintype "passive"))
    )
    (net (code "176") (name "LC_1_CS5") (class "Default")
      (node (ref "U22") (pin "26") (pinfunction "PB0_26") (pintype "bidirectional"))
      (node (ref "U26") (pin "19") (pinfunction "*CS_19") (pintype "passive"))
    )
    (net (code "177") (name "LC_1_CS6") (class "Default")
      (node (ref "U22") (pin "27") (pinfunction "PB1_27") (pintype "bidirectional"))
      (node (ref "U27") (pin "19") (pinfunction "*CS_19") (pintype "passive"))
    )
    (net (code "178") (name "LC_1_CS7") (class "Default")
      (node (ref "U22") (pin "28") (pinfunction "PB1_2_28") (pintype "bidirectional"))
      (node (ref "U28") (pin "19") (pinfunction "*CS_19") (pintype "passive"))
    )
    (net (code "179") (name "LC_1_MCLK") (class "Default")
      (node (ref "U18") (pin "2") (pinfunction "MCLK_IN_2") (pintype "passive"))
      (node (ref "Y3") (pin "3") (pinfunction "OUT_3") (pintype "bidirectional"))
    )
    (net (code "180") (name "LC_1_NRST") (class "Default")
      (node (ref "SV10") (pin "4") (pinfunction "4_4") (pintype "passive"))
      (node (ref "U22") (pin "7") (pinfunction "NRST_7") (pintype "output"))
    )
    (net (code "181") (name "LC_1_OSC_IN") (class "Default")
      (node (ref "C18") (pin "1") (pinfunction "1_1") (pintype "passive"))
      (node (ref "U22") (pin "5") (pinfunction "PD0_OSC_IN_5") (pintype "input"))
      (node (ref "Y4") (pin "1") (pinfunction "OSC1_1") (pintype "bidirectional"))
    )
    (net (code "182") (name "LC_1_OSC_OUT") (class "Default")
      (node (ref "C17") (pin "1") (pinfunction "1_1") (pintype "passive"))
      (node (ref "U22") (pin "6") (pinfunction "PD1_OSC_OUT_6") (pintype "output"))
      (node (ref "Y4") (pin "3") (pinfunction "OSC2_3") (pintype "bidirectional"))
    )
    (net (code "183") (name "LC_1_PB7") (class "Default")
      (node (ref "U22") (pin "59") (pinfunction "PB7_59") (pintype "power_in"))
    )
    (net (code "184") (name "LC_1_RDY0") (class "Default")
      (node (ref "U18") (pin "20") (pinfunction "*RDY_20") (pintype "passive"))
      (node (ref "U22") (pin "45") (pinfunction "PA12_45") (pintype "bidirectional"))
    )
    (net (code "185") (name "LC_1_RDY1") (class "Default")
      (node (ref "U21") (pin "20") (pinfunction "*RDY_20") (pintype "passive"))
      (node (ref "U22") (pin "44") (pinfunction "PA11_44") (pintype "bidirectional"))
    )
    (net (code "186") (name "LC_1_RDY2") (class "Default")
      (node (ref "U22") (pin "43") (pinfunction "PA10_43") (pintype "bidirectional"))
      (node (ref "U23") (pin "20") (pinfunction "*RDY_20") (pintype "passive"))
    )
    (net (code "187") (name "LC_1_RDY3") (class "Default")
      (node (ref "U22") (pin "42") (pinfunction "PA9_42") (pintype "bidirectional"))
      (node (ref "U24") (pin "20") (pinfunction "*RDY_20") (pintype "passive"))
    )
    (net (code "188") (name "LC_1_RDY4") (class "Default")
      (node (ref "U22") (pin "41") (pinfunction "PA8_41") (pintype "bidirectional"))
      (node (ref "U25") (pin "20") (pinfunction "*RDY_20") (pintype "passive"))
    )
    (net (code "189") (name "LC_1_RDY5") (class "Default")
      (node (ref "U22") (pin "40") (pinfunction "PC9_40") (pintype "bidirectional"))
      (node (ref "U26") (pin "20") (pinfunction "*RDY_20") (pintype "passive"))
    )
    (net (code "190") (name "LC_1_RDY6") (class "Default")
      (node (ref "U22") (pin "39") (pinfunction "PC8_39") (pintype "bidirectional"))
      (node (ref "U27") (pin "20") (pinfunction "*RDY_20") (pintype "passive"))
    )
    (net (code "191") (name "LC_1_RDY7") (class "Default")
      (node (ref "U22") (pin "38") (pinfunction "PC7_38") (pintype "bidirectional"))
      (node (ref "U28") (pin "20") (pinfunction "*RDY_20") (pintype "passive"))
    )
    (net (code "192") (name "LC_1_SPI1_MISO") (class "Default")
      (node (ref "U18") (pin "21") (pinfunction "DOUT_21") (pintype "passive"))
      (node (ref "U21") (pin "21") (pinfunction "DOUT_21") (pintype "passive"))
      (node (ref "U22") (pin "22") (pinfunction "PA6_22") (pintype "bidirectional"))
      (node (ref "U23") (pin "21") (pinfunction "DOUT_21") (pintype "passive"))
      (node (ref "U24") (pin "21") (pinfunction "DOUT_21") (pintype "passive"))
      (node (ref "U25") (pin "21") (pinfunction "DOUT_21") (pintype "passive"))
      (node (ref "U26") (pin "21") (pinfunction "DOUT_21") (pintype "passive"))
      (node (ref "U27") (pin "21") (pinfunction "DOUT_21") (pintype "passive"))
      (node (ref "U28") (pin "21") (pinfunction "DOUT_21") (pintype "passive"))
    )
    (net (code "193") (name "LC_1_SPI1_MOSI") (class "Default")
      (node (ref "U18") (pin "22") (pinfunction "DIN_22") (pintype "passive"))
      (node (ref "U21") (pin "22") (pinfunction "DIN_22") (pintype "passive"))
      (node (ref "U22") (pin "23") (pinfunction "PA7_23") (pintype "power_in"))
      (node (ref "U23") (pin "22") (pinfunction "DIN_22") (pintype "passive"))
      (node (ref "U24") (pin "22") (pinfunction "DIN_22") (pintype "passive"))
      (node (ref "U25") (pin "22") (pinfunction "DIN_22") (pintype "passive"))
      (node (ref "U26") (pin "22") (pinfunction "DIN_22") (pintype "passive"))
      (node (ref "U27") (pin "22") (pinfunction "DIN_22") (pintype "passive"))
      (node (ref "U28") (pin "22") (pinfunction "DIN_22") (pintype "passive"))
    )
    (net (code "194") (name "LC_1_SPI1_SCK") (class "Default")
      (node (ref "U18") (pin "1") (pinfunction "SCLK_1") (pintype "passive"))
      (node (ref "U21") (pin "1") (pinfunction "SCLK_1") (pintype "passive"))
      (node (ref "U22") (pin "21") (pinfunction "PA5_21") (pintype "bidirectional"))
      (node (ref "U23") (pin "1") (pinfunction "SCLK_1") (pintype "passive"))
      (node (ref "U24") (pin "1") (pinfunction "SCLK_1") (pintype "passive"))
      (node (ref "U25") (pin "1") (pinfunction "SCLK_1") (pintype "passive"))
      (node (ref "U26") (pin "1") (pinfunction "SCLK_1") (pintype "passive"))
      (node (ref "U27") (pin "1") (pinfunction "SCLK_1") (pintype "passive"))
      (node (ref "U28") (pin "1") (pinfunction "SCLK_1") (pintype "passive"))
    )
    (net (code "195") (name "LC_1_SWDCLK") (class "Default")
      (node (ref "SV10") (pin "3") (pinfunction "3_3") (pintype "passive"))
      (node (ref "U22") (pin "49") (pinfunction "PA14_49") (pintype "bidirectional"))
    )
    (net (code "196") (name "LC_1_SWDIO") (class "Default")
      (node (ref "SV10") (pin "6") (pinfunction "6_6") (pintype "passive"))
      (node (ref "U22") (pin "46") (pinfunction "PA13_46") (pintype "bidirectional"))
    )
    (net (code "197") (name "LC_2_CS0") (class "Default")
      (node (ref "U38") (pin "19") (pinfunction "*CS_19") (pintype "passive"))
      (node (ref "U40") (pin "14") (pinfunction "PA0-WKUP_14") (pintype "bidirectional"))
    )
    (net (code "198") (name "LC_2_CS1") (class "Default")
      (node (ref "U39") (pin "19") (pinfunction "*CS_19") (pintype "passive"))
      (node (ref "U40") (pin "15") (pinfunction "PA1_15") (pintype "bidirectional"))
    )
    (net (code "199") (name "LC_2_CS2") (class "Default")
      (node (ref "U40") (pin "16") (pinfunction "PA2_16") (pintype "bidirectional"))
      (node (ref "U41") (pin "19") (pinfunction "*CS_19") (pintype "passive"))
    )
    (net (code "200") (name "LC_2_CS3") (class "Default")
      (node (ref "U40") (pin "24") (pinfunction "PC4_24") (pintype "passive"))
      (node (ref "U42") (pin "19") (pinfunction "*CS_19") (pintype "passive"))
    )
    (net (code "201") (name "LC_2_CS4") (class "Default")
      (node (ref "U40") (pin "25") (pinfunction "PC5_25") (pintype "bidirectional"))
      (node (ref "U43") (pin "19") (pinfunction "*CS_19") (pintype "passive"))
    )
    (net (code "202") (name "LC_2_CS5") (class "Default")
      (node (ref "U40") (pin "26") (pinfunction "PB0_26") (pintype "bidirectional"))
      (node (ref "U44") (pin "19") (pinfunction "*CS_19") (pintype "passive"))
    )
    (net (code "203") (name "LC_2_CS6") (class "Default")
      (node (ref "U40") (pin "27") (pinfunction "PB1_27") (pintype "bidirectional"))
      (node (ref "U45") (pin "19") (pinfunction "*CS_19") (pintype "passive"))
    )
    (net (code "204") (name "LC_2_CS7") (class "Default")
      (node (ref "U40") (pin "28") (pinfunction "PB1_2_28") (pintype "bidirectional"))
      (node (ref "U46") (pin "19") (pinfunction "*CS_19") (pintype "passive"))
    )
    (net (code "205") (name "LC_2_MCLK") (class "Default")
      (node (ref "U38") (pin "2") (pinfunction "MCLK_IN_2") (pintype "passive"))
      (node (ref "Y7") (pin "3") (pinfunction "OUT_3") (pintype "bidirectional"))
    )
    (net (code "206") (name "LC_2_NRST") (class "Default")
      (node (ref "SV21") (pin "4") (pinfunction "4_4") (pintype "passive"))
      (node (ref "U40") (pin "7") (pinfunction "NRST_7") (pintype "output"))
    )
    (net (code "207") (name "LC_2_OSC_IN") (class "Default")
      (node (ref "C59") (pin "1") (pinfunction "1_1") (pintype "passive"))
      (node (ref "U40") (pin "5") (pinfunction "PD0_OSC_IN_5") (pintype "input"))
      (node (ref "Y8") (pin "1") (pinfunction "OSC1_1") (pintype "bidirectional"))
    )
    (net (code "208") (name "LC_2_OSC_OUT") (class "Default")
      (node (ref "C58") (pin "1") (pinfunction "1_1") (pintype "passive"))
      (node (ref "U40") (pin "6") (pinfunction "PD1_OSC_OUT_6") (pintype "output"))
      (node (ref "Y8") (pin "3") (pinfunction "OSC2_3") (pintype "bidirectional"))
    )
    (net (code "209") (name "LC_2_PB7") (class "Default")
      (node (ref "U40") (pin "59") (pinfunction "PB7_59") (pintype "power_in"))
    )
    (net (code "210") (name "LC_2_RDY0") (class "Default")
      (node (ref "U38") (pin "20") (pinfunction "*RDY_20") (pintype "passive"))
      (node (ref "U40") (pin "45") (pinfunction "PA12_45") (pintype "bidirectional"))
    )
    (net (code "211") (name "LC_2_RDY1") (class "Default")
      (node (ref "U39") (pin "20") (pinfunction "*RDY_20") (pintype "passive"))
      (node (ref "U40") (pin "44") (pinfunction "PA11_44") (pintype "bidirectional"))
    )
    (net (code "212") (name "LC_2_RDY2") (class "Default")
      (node (ref "U40") (pin "43") (pinfunction "PA10_43") (pintype "bidirectional"))
      (node (ref "U41") (pin "20") (pinfunction "*RDY_20") (pintype "passive"))
    )
    (net (code "213") (name "LC_2_RDY3") (class "Default")
      (node (ref "U40") (pin "42") (pinfunction "PA9_42") (pintype "bidirectional"))
      (node (ref "U42") (pin "20") (pinfunction "*RDY_20") (pintype "passive"))
    )
    (net (code "214") (name "LC_2_RDY4") (class "Default")
      (node (ref "U40") (pin "41") (pinfunction "PA8_41") (pintype "bidirectional"))
      (node (ref "U43") (pin "20") (pinfunction "*RDY_20") (pintype "passive"))
    )
    (net (code "215") (name "LC_2_RDY5") (class "Default")
      (node (ref "U40") (pin "40") (pinfunction "PC9_40") (pintype "bidirectional"))
      (node (ref "U44") (pin "20") (pinfunction "*RDY_20") (pintype "passive"))
    )
    (net (code "216") (name "LC_2_RDY6") (class "Default")
      (node (ref "U40") (pin "39") (pinfunction "PC8_39") (pintype "bidirectional"))
      (node (ref "U45") (pin "20") (pinfunction "*RDY_20") (pintype "passive"))
    )
    (net (code "217") (name "LC_2_RDY7") (class "Default")
      (node (ref "U40") (pin "38") (pinfunction "PC7_38") (pintype "bidirectional"))
      (node (ref "U46") (pin "20") (pinfunction "*RDY_20") (pintype "passive"))
    )
    (net (code "218") (name "LC_2_SPI1_MISO") (class "Default")
      (node (ref "U38") (pin "21") (pinfunction "DOUT_21") (pintype "passive"))
      (node (ref "U39") (pin "21") (pinfunction "DOUT_21") (pintype "passive"))
      (node (ref "U40") (pin "22") (pinfunction "PA6_22") (pintype "bidirectional"))
      (node (ref "U41") (pin "21") (pinfunction "DOUT_21") (pintype "passive"))
      (node (ref "U42") (pin "21") (pinfunction "DOUT_21") (pintype "passive"))
      (node (ref "U43") (pin "21") (pinfunction "DOUT_21") (pintype "passive"))
      (node (ref "U44") (pin "21") (pinfunction "DOUT_21") (pintype "passive"))
      (node (ref "U45") (pin "21") (pinfunction "DOUT_21") (pintype "passive"))
      (node (ref "U46") (pin "21") (pinfunction "DOUT_21") (pintype "passive"))
    )
    (net (code "219") (name "LC_2_SPI1_MOSI") (class "Default")
      (node (ref "U38") (pin "22") (pinfunction "DIN_22") (pintype "passive"))
      (node (ref "U39") (pin "22") (pinfunction "DIN_22") (pintype "passive"))
      (node (ref "U40") (pin "23") (pinfunction "PA7_23") (pintype "power_in"))
      (node (ref "U41") (pin "22") (pinfunction "DIN_22") (pintype "passive"))
      (node (ref "U42") (pin "22") (pinfunction "DIN_22") (pintype "passive"))
      (node (ref "U43") (pin "22") (pinfunction "DIN_22") (pintype "passive"))
      (node (ref "U44") (pin "22") (pinfunction "DIN_22") (pintype "passive"))
      (node (ref "U45") (pin "22") (pinfunction "DIN_22") (pintype "passive"))
      (node (ref "U46") (pin "22") (pinfunction "DIN_22") (pintype "passive"))
    )
    (net (code "220") (name "LC_2_SPI1_SCK") (class "Default")
      (node (ref "U38") (pin "1") (pinfunction "SCLK_1") (pintype "passive"))
      (node (ref "U39") (pin "1") (pinfunction "SCLK_1") (pintype "passive"))
      (node (ref "U40") (pin "21") (pinfunction "PA5_21") (pintype "bidirectional"))
      (node (ref "U41") (pin "1") (pinfunction "SCLK_1") (pintype "passive"))
      (node (ref "U42") (pin "1") (pinfunction "SCLK_1") (pintype "passive"))
      (node (ref "U43") (pin "1") (pinfunction "SCLK_1") (pintype "passive"))
      (node (ref "U44") (pin "1") (pinfunction "SCLK_1") (pintype "passive"))
      (node (ref "U45") (pin "1") (pinfunction "SCLK_1") (pintype "passive"))
      (node (ref "U46") (pin "1") (pinfunction "SCLK_1") (pintype "passive"))
    )
    (net (code "221") (name "LC_2_SWDCLK") (class "Default")
      (node (ref "SV21") (pin "3") (pinfunction "3_3") (pintype "passive"))
      (node (ref "U40") (pin "49") (pinfunction "PA14_49") (pintype "bidirectional"))
    )
    (net (code "222") (name "LC_2_SWDIO") (class "Default")
      (node (ref "SV21") (pin "6") (pinfunction "6_6") (pintype "passive"))
      (node (ref "U40") (pin "46") (pinfunction "PA13_46") (pintype "bidirectional"))
    )
    (net (code "223") (name "LDAC") (class "Default")
      (node (ref "SV1") (pin "35") (pinfunction "35_35") (pintype "passive"))
      (node (ref "U15") (pin "1") (pinfunction "*LDAC_1") (pintype "passive"))
      (node (ref "U19") (pin "1") (pinfunction "*LDAC_1") (pintype "passive"))
    )
    (net (code "224") (name "MISO") (class "Default")
      (node (ref "SV1") (pin "21") (pinfunction "21_21") (pintype "passive"))
      (node (ref "U15") (pin "49") (pinfunction "SDO_49") (pintype "passive"))
      (node (ref "U19") (pin "49") (pinfunction "SDO_49") (pintype "passive"))
      (node (ref "U22") (pin "56") (pinfunction "PB4_56") (pintype "bidirectional"))
      (node (ref "U40") (pin "56") (pinfunction "PB4_56") (pintype "bidirectional"))
      (node (ref "U5") (pin "57") (pinfunction "DB12/SDOA_57") (pintype "passive"))
      (node (ref "U8") (pin "57") (pinfunction "DB12/SDOA_57") (pintype "passive"))
    )
    (net (code "225") (name "MOSI") (class "Default")
      (node (ref "SV1") (pin "19") (pinfunction "19_19") (pintype "passive"))
      (node (ref "U15") (pin "47") (pinfunction "SDI_47") (pintype "passive"))
      (node (ref "U19") (pin "47") (pinfunction "SDI_47") (pintype "passive"))
      (node (ref "U22") (pin "57") (pinfunction "PB5_57") (pintype "bidirectional"))
      (node (ref "U40") (pin "57") (pinfunction "PB5_57") (pintype "bidirectional"))
      (node (ref "U5") (pin "55") (pinfunction "DB10/SDI_55") (pintype "passive"))
      (node (ref "U8") (pin "55") (pinfunction "DB10/SDI_55") (pintype "passive"))
    )
    (net (code "226") (name "PG_CURR_LIM") (class "Default")
      (node (ref "LED4") (pin "A") (pinfunction "A_A") (pintype "passive"))
      (node (ref "R1") (pin "1") (pinfunction "1_1") (pintype "passive"))
    )
    (net (code "227") (name "PG_SIG") (class "Default")
      (node (ref "Q1") (pin "B") (pinfunction "B_B") (pintype "passive"))
      (node (ref "R12") (pin "1") (pinfunction "1_1") (pintype "passive"))
    )
    (net (code "228") (name "POWER_GOOD") (class "Default")
      (node (ref "PL1") (pin "8") (pinfunction "S_8") (pintype "passive"))
      (node (ref "R12") (pin "2") (pinfunction "2_2") (pintype "passive"))
    )
    (net (code "229") (name "POWER_GOOD_SUPP") (class "Default")
      (node (ref "Q1") (pin "E") (pinfunction "E_E") (pintype "passive"))
      (node (ref "R1") (pin "2") (pinfunction "2_2") (pintype "passive"))
    )
    (net (code "230") (name "PSU_ENABLE") (class "Default")
      (node (ref "PL1") (pin "16") (pinfunction "S_16") (pintype "passive"))
      (node (ref "S1") (pin "2") (pinfunction "2_2") (pintype "passive"))
    )
    (net (code "231") (name "RPI_PWR") (class "Default")
      (node (ref "JP1") (pin "2") (pinfunction "2_2") (pintype "passive"))
      (node (ref "SV1") (pin "2") (pinfunction "2_2") (pintype "passive"))
      (node (ref "SV1") (pin "4") (pinfunction "4_4") (pintype "passive"))
    )
    (net (code "232") (name "SCLK") (class "Default")
      (node (ref "SV1") (pin "23") (pinfunction "23_23") (pintype "passive"))
      (node (ref "U15") (pin "46") (pinfunction "SCLK_46") (pintype "passive"))
      (node (ref "U19") (pin "46") (pinfunction "SCLK_46") (pintype "passive"))
      (node (ref "U22") (pin "55") (pinfunction "PB3_55") (pintype "bidirectional"))
      (node (ref "U40") (pin "55") (pinfunction "PB3_55") (pintype "bidirectional"))
      (node (ref "U5") (pin "62") (pinfunction "SCLK/*RD_62") (pintype "passive"))
      (node (ref "U8") (pin "62") (pinfunction "SCLK/*RD_62") (pintype "passive"))
    )
    (net (code "233") (name "SS_ADC_1") (class "Default")
      (node (ref "SV1") (pin "7") (pinfunction "7_7") (pintype "passive"))
      (node (ref "U8") (pin "63") (pinfunction "*CS_63") (pintype "passive"))
    )
    (net (code "234") (name "SS_ADC_2") (class "Default")
      (node (ref "SV1") (pin "13") (pinfunction "13_13") (pintype "passive"))
      (node (ref "U5") (pin "63") (pinfunction "*CS_63") (pintype "passive"))
    )
    (net (code "235") (name "SS_DAC_1") (class "Default")
      (node (ref "SV1") (pin "36") (pinfunction "36_36") (pintype "passive"))
      (node (ref "U15") (pin "45") (pinfunction "*SYNC_45") (pintype "passive"))
    )
    (net (code "236") (name "SS_DAC_2") (class "Default")
      (node (ref "SV1") (pin "40") (pinfunction "40_40") (pintype "passive"))
      (node (ref "U19") (pin "45") (pinfunction "*SYNC_45") (pintype "passive"))
    )
    (net (code "237") (name "SS_LC_1") (class "Default")
      (node (ref "SV1") (pin "38") (pinfunction "38_38") (pintype "passive"))
      (node (ref "U40") (pin "50") (pinfunction "PA15_50") (pintype "bidirectional"))
    )
    (net (code "238") (name "SS_LC_2") (class "Default")
      (node (ref "SV1") (pin "37") (pinfunction "37_37") (pintype "passive"))
      (node (ref "U22") (pin "50") (pinfunction "PA15_50") (pintype "bidirectional"))
    )
    (net (code "239") (name "VDD") (class "Default")
      (node (ref "C107") (pin "1") (pinfunction "1_1") (pintype "passive"))
      (node (ref "C109") (pin "1") (pinfunction "1_1") (pintype "passive"))
      (node (ref "C114") (pin "1") (pinfunction "1_1") (pintype "passive"))
      (node (ref "C141") (pin "1") (pinfunction "1_1") (pintype "passive"))
      (node (ref "C143") (pin "1") (pinfunction "1_1") (pintype "passive"))
      (node (ref "C148") (pin "1") (pinfunction "1_1") (pintype "passive"))
      (node (ref "C23") (pin "+") (pinfunction "+_+") (pintype "passive"))
      (node (ref "C24") (pin "+") (pinfunction "+_+") (pintype "passive"))
      (node (ref "C27") (pin "+") (pinfunction "+_+") (pintype "passive"))
      (node (ref "C29") (pin "+") (pinfunction "+_+") (pintype "passive"))
      (node (ref "C3") (pin "+") (pinfunction "+_+") (pintype "passive"))
      (node (ref "C33") (pin "1") (pinfunction "1_1") (pintype "passive"))
      (node (ref "C5") (pin "+") (pinfunction "+_+") (pintype "passive"))
      (node (ref "C6") (pin "+") (pinfunction "+_+") (pintype "passive"))
      (node (ref "C64") (pin "1") (pinfunction "1_1") (pintype "passive"))
      (node (ref "C9") (pin "+") (pinfunction "+_+") (pintype "passive"))
      (node (ref "J1") (pin "1") (pinfunction "1_1") (pintype "input"))
      (node (ref "J10") (pin "1") (pinfunction "1_1") (pintype "input"))
      (node (ref "J11") (pin "1") (pinfunction "1_1") (pintype "input"))
      (node (ref "J12") (pin "1") (pinfunction "1_1") (pintype "input"))
      (node (ref "J13") (pin "1") (pinfunction "1_1") (pintype "input"))
      (node (ref "J14") (pin "1") (pinfunction "1_1") (pintype "input"))
      (node (ref "J15") (pin "1") (pinfunction "1_1") (pintype "input"))
      (node (ref "J16") (pin "1") (pinfunction "1_1") (pintype "input"))
      (node (ref "J17") (pin "1") (pinfunction "1_1") (pintype "input"))
      (node (ref "J18") (pin "1") (pinfunction "1_1") (pintype "input"))
      (node (ref "J19") (pin "1") (pinfunction "1_1") (pintype "input"))
      (node (ref "J2") (pin "1") (pinfunction "1_1") (pintype "input"))
      (node (ref "J20") (pin "1") (pinfunction "1_1") (pintype "input"))
      (node (ref "J21") (pin "1") (pinfunction "1_1") (pintype "input"))
      (node (ref "J22") (pin "1") (pinfunction "1_1") (pintype "input"))
      (node (ref "J23") (pin "1") (pinfunction "1_1") (pintype "input"))
      (node (ref "J24") (pin "1") (pinfunction "1_1") (pintype "input"))
      (node (ref "J25") (pin "1") (pinfunction "1_1") (pintype "input"))
      (node (ref "J26") (pin "1") (pinfunction "1_1") (pintype "input"))
      (node (ref "J27") (pin "1") (pinfunction "1_1") (pintype "input"))
      (node (ref "J28") (pin "1") (pinfunction "1_1") (pintype "input"))
      (node (ref "J29") (pin "1") (pinfunction "1_1") (pintype "input"))
      (node (ref "J3") (pin "1") (pinfunction "1_1") (pintype "input"))
      (node (ref "J30") (pin "1") (pinfunction "1_1") (pintype "input"))
      (node (ref "J31") (pin "1") (pinfunction "1_1") (pintype "input"))
      (node (ref "J32") (pin "1") (pinfunction "1_1") (pintype "input"))
      (node (ref "J4") (pin "1") (pinfunction "1_1") (pintype "input"))
      (node (ref "J5") (pin "1") (pinfunction "1_1") (pintype "input"))
      (node (ref "J6") (pin "1") (pinfunction "1_1") (pintype "input"))
      (node (ref "J7") (pin "1") (pinfunction "1_1") (pintype "input"))
      (node (ref "J8") (pin "1") (pinfunction "1_1") (pintype "input"))
      (node (ref "J9") (pin "1") (pinfunction "1_1") (pintype "input"))
      (node (ref "PL1") (pin "11") (pinfunction "S_11") (pintype "passive"))
      (node (ref "R10") (pin "2") (pinfunction "2_2") (pintype "passive"))
      (node (ref "U15") (pin "11") (pinfunction "VDD_11") (pintype "passive"))
      (node (ref "U15") (pin "28") (pinfunction "VDD_2_28") (pintype "passive"))
      (node (ref "U16") (pin "2") (pinfunction "VIN_2") (pintype "passive"))
      (node (ref "U19") (pin "11") (pinfunction "VDD_11") (pintype "passive"))
      (node (ref "U19") (pin "28") (pinfunction "VDD_2_28") (pintype "passive"))
      (node (ref "U20") (pin "2") (pinfunction "VIN_2") (pintype "passive"))
      (node (ref "U4") (pin "2") (pinfunction "VIN_2") (pintype "passive"))
      (node (ref "U7") (pin "2") (pinfunction "VIN_2") (pintype "passive"))
      (node (ref "X1") (pin "2") (pinfunction "S_2") (pintype "passive"))
    )
    (net (code "240") (name "VDD_CURR_LIM") (class "Default")
      (node (ref "LED5") (pin "A") (pinfunction "A_A") (pintype "passive"))
      (node (ref "R10") (pin "1") (pinfunction "1_1") (pintype "passive"))
    )
    (net (code "241") (name "VREF_1") (class "Default")
      (node (ref "C116") (pin "1") (pinfunction "1_1") (pintype "passive"))
      (node (ref "C117") (pin "1") (pinfunction "1_1") (pintype "passive"))
      (node (ref "C4") (pin "+") (pinfunction "+_+") (pintype "passive"))
      (node (ref "U15") (pin "13") (pinfunction "VREF1_13") (pintype "passive"))
      (node (ref "U15") (pin "31") (pinfunction "VREF0_31") (pintype "passive"))
      (node (ref "U16") (pin "6") (pinfunction "VOUT_6") (pintype "passive"))
    )
    (net (code "242") (name "VREF_2") (class "Default")
      (node (ref "C10") (pin "+") (pinfunction "+_+") (pintype "passive"))
      (node (ref "C150") (pin "1") (pinfunction "1_1") (pintype "passive"))
      (node (ref "C151") (pin "1") (pinfunction "1_1") (pintype "passive"))
      (node (ref "U19") (pin "13") (pinfunction "VREF1_13") (pintype "passive"))
      (node (ref "U19") (pin "31") (pinfunction "VREF0_31") (pintype "passive"))
      (node (ref "U20") (pin "6") (pinfunction "VOUT_6") (pintype "passive"))
    )
    (net (code "243") (name "VSS") (class "Default")
      (node (ref "C111") (pin "1") (pinfunction "1_1") (pintype "passive"))
      (node (ref "C113") (pin "1") (pinfunction "1_1") (pintype "passive"))
      (node (ref "C145") (pin "1") (pinfunction "1_1") (pintype "passive"))
      (node (ref "C147") (pin "1") (pinfunction "1_1") (pintype "passive"))
      (node (ref "C25") (pin "-") (pinfunction "-_-") (pintype "passive"))
      (node (ref "C26") (pin "-") (pinfunction "-_-") (pintype "passive"))
      (node (ref "C7") (pin "-") (pinfunction "-_-") (pintype "passive"))
      (node (ref "C8") (pin "-") (pinfunction "-_-") (pintype "passive"))
      (node (ref "PL1") (pin "14") (pinfunction "S_14") (pintype "passive"))
      (node (ref "U15") (pin "12") (pinfunction "VSS_2_12") (pintype "passive"))
      (node (ref "U15") (pin "29") (pinfunction "VSS_29") (pintype "passive"))
      (node (ref "U19") (pin "12") (pinfunction "VSS_2_12") (pintype "passive"))
      (node (ref "U19") (pin "29") (pinfunction "VSS_29") (pintype "passive"))
    )
    (net (code "244") (name "unconnected-(PL1A-S-Pad1)") (class "Default")
      (node (ref "PL1") (pin "1") (pinfunction "S_1") (pintype "passive"))
    )
    (net (code "245") (name "unconnected-(PL1B-S-Pad10)") (class "Default")
      (node (ref "PL1") (pin "10") (pinfunction "S_10") (pintype "passive"))
    )
    (net (code "246") (name "unconnected-(PL1D-S-Pad12)") (class "Default")
      (node (ref "PL1") (pin "12") (pinfunction "S_12") (pintype "passive"))
    )
    (net (code "247") (name "unconnected-(PL1E-S-Pad13)") (class "Default")
      (node (ref "PL1") (pin "13") (pinfunction "S_13") (pintype "passive"))
    )
    (net (code "248") (name "unconnected-(PL1M-S-Pad20)") (class "Default")
      (node (ref "PL1") (pin "20") (pinfunction "S_20") (pintype "passive"))
    )
    (net (code "249") (name "unconnected-(PL1N-S-Pad21)") (class "Default")
      (node (ref "PL1") (pin "21") (pinfunction "S_21") (pintype "passive"))
    )
    (net (code "250") (name "unconnected-(PL1O-S-Pad22)") (class "Default")
      (node (ref "PL1") (pin "22") (pinfunction "S_22") (pintype "passive"))
    )
    (net (code "251") (name "unconnected-(PL1S-S-Pad4)") (class "Default")
      (node (ref "PL1") (pin "4") (pinfunction "S_4") (pintype "passive"))
    )
    (net (code "252") (name "unconnected-(PL1U-S-Pad6)") (class "Default")
      (node (ref "PL1") (pin "6") (pinfunction "S_6") (pintype "passive"))
    )
    (net (code "253") (name "unconnected-(PL1X-S-Pad9)") (class "Default")
      (node (ref "PL1") (pin "9") (pinfunction "S_9") (pintype "passive"))
    )
    (net (code "254") (name "unconnected-(S1-Pad1)") (class "Default")
      (node (ref "S1") (pin "1") (pinfunction "1_1") (pintype "passive"))
    )
    (net (code "255") (name "unconnected-(S2-S1-Pad2)") (class "Default")
      (node (ref "S2") (pin "2") (pinfunction "S1_2") (pintype "passive"))
    )
    (net (code "256") (name "unconnected-(S3-S1-Pad2)") (class "Default")
      (node (ref "S3") (pin "2") (pinfunction "S1_2") (pintype "passive"))
    )
    (net (code "257") (name "unconnected-(S6-P-Pad3)") (class "Default")
      (node (ref "S6") (pin "3") (pinfunction "P_3") (pintype "passive"))
    )
    (net (code "258") (name "unconnected-(S8-P-Pad3)") (class "Default")
      (node (ref "S8") (pin "3") (pinfunction "P_3") (pintype "passive"))
    )
    (net (code "259") (name "unconnected-(SV1-Pad1)") (class "Default")
      (node (ref "SV1") (pin "1") (pinfunction "1_1") (pintype "passive"))
    )
    (net (code "260") (name "unconnected-(SV1-Pad5)") (class "Default")
      (node (ref "SV1") (pin "5") (pinfunction "5_5") (pintype "passive"))
    )
    (net (code "261") (name "unconnected-(SV1-Pad8)") (class "Default")
      (node (ref "SV1") (pin "8") (pinfunction "8_8") (pintype "passive"))
    )
    (net (code "262") (name "unconnected-(SV1-Pad10)") (class "Default")
      (node (ref "SV1") (pin "10") (pinfunction "10_10") (pintype "passive"))
    )
    (net (code "263") (name "unconnected-(SV1-Pad12)") (class "Default")
      (node (ref "SV1") (pin "12") (pinfunction "12_12") (pintype "passive"))
    )
    (net (code "264") (name "unconnected-(SV1-Pad15)") (class "Default")
      (node (ref "SV1") (pin "15") (pinfunction "15_15") (pintype "passive"))
    )
    (net (code "265") (name "unconnected-(SV1-Pad16)") (class "Default")
      (node (ref "SV1") (pin "16") (pinfunction "16_16") (pintype "passive"))
    )
    (net (code "266") (name "unconnected-(SV1-Pad17)") (class "Default")
      (node (ref "SV1") (pin "17") (pinfunction "17_17") (pintype "passive"))
    )
    (net (code "267") (name "unconnected-(SV1-Pad18)") (class "Default")
      (node (ref "SV1") (pin "18") (pinfunction "18_18") (pintype "passive"))
    )
    (net (code "268") (name "unconnected-(SV1-Pad22)") (class "Default")
      (node (ref "SV1") (pin "22") (pinfunction "22_22") (pintype "passive"))
    )
    (net (code "269") (name "unconnected-(SV1-Pad24)") (class "Default")
      (node (ref "SV1") (pin "24") (pinfunction "24_24") (pintype "passive"))
    )
    (net (code "270") (name "unconnected-(SV1-Pad26)") (class "Default")
      (node (ref "SV1") (pin "26") (pinfunction "26_26") (pintype "passive"))
    )
    (net (code "271") (name "unconnected-(SV1-Pad27)") (class "Default")
      (node (ref "SV1") (pin "27") (pinfunction "27_27") (pintype "passive"))
    )
    (net (code "272") (name "unconnected-(SV1-Pad28)") (class "Default")
      (node (ref "SV1") (pin "28") (pinfunction "28_28") (pintype "passive"))
    )
    (net (code "273") (name "unconnected-(SV1-Pad29)") (class "Default")
      (node (ref "SV1") (pin "29") (pinfunction "29_29") (pintype "passive"))
    )
    (net (code "274") (name "unconnected-(SV1-Pad31)") (class "Default")
      (node (ref "SV1") (pin "31") (pinfunction "31_31") (pintype "passive"))
    )
    (net (code "275") (name "unconnected-(SV1-Pad32)") (class "Default")
      (node (ref "SV1") (pin "32") (pinfunction "32_32") (pintype "passive"))
    )
    (net (code "276") (name "unconnected-(SV1-Pad33)") (class "Default")
      (node (ref "SV1") (pin "33") (pinfunction "33_33") (pintype "passive"))
    )
    (net (code "277") (name "unconnected-(U1-Pad33)") (class "Default")
      (node (ref "U1") (pin "33") (pinfunction "33_33") (pintype "passive"))
    )
    (net (code "278") (name "unconnected-(U1-Pad34)") (class "Default")
      (node (ref "U1") (pin "34") (pinfunction "34_34") (pintype "passive"))
    )
    (net (code "279") (name "unconnected-(U2-Pad33)") (class "Default")
      (node (ref "U2") (pin "33") (pinfunction "33_33") (pintype "passive"))
    )
    (net (code "280") (name "unconnected-(U2-Pad34)") (class "Default")
      (node (ref "U2") (pin "34") (pinfunction "34_34") (pintype "passive"))
    )
    (net (code "281") (name "unconnected-(U4-NIC-Pad7)") (class "Default")
      (node (ref "U4") (pin "7") (pinfunction "NIC_7") (pintype "passive"))
    )
    (net (code "282") (name "unconnected-(U4-NIC_2-Pad3)") (class "Default")
      (node (ref "U4") (pin "3") (pinfunction "NIC_2_3") (pintype "passive"))
    )
    (net (code "283") (name "unconnected-(U4-TP-Pad8)") (class "Default")
      (node (ref "U4") (pin "8") (pinfunction "TP_8") (pintype "passive"))
    )
    (net (code "284") (name "unconnected-(U4-TP_2-Pad1)") (class "Default")
      (node (ref "U4") (pin "1") (pinfunction "TP_2_1") (pintype "passive"))
    )
    (net (code "285") (name "unconnected-(U4-TRIM-Pad5)") (class "Default")
      (node (ref "U4") (pin "5") (pinfunction "TRIM_5") (pintype "passive"))
    )
    (net (code "286") (name "unconnected-(U5-BUSY-Pad67)") (class "Default")
      (node (ref "U5") (pin "67") (pinfunction "BUSY_67") (pintype "passive"))
    )
    (net (code "287") (name "unconnected-(U5-DB11{slash}SDOB-Pad56)") (class "Default")
      (node (ref "U5") (pin "56") (pinfunction "DB11/SDOB_56") (pintype "passive"))
    )
    (net (code "288") (name "unconnected-(U6-N.C-Pad1)") (class "Default")
      (node (ref "U6") (pin "1") (pinfunction "N.C_1") (pintype "no_connect"))
    )
    (net (code "289") (name "unconnected-(U7-NIC-Pad7)") (class "Default")
      (node (ref "U7") (pin "7") (pinfunction "NIC_7") (pintype "passive"))
    )
    (net (code "290") (name "unconnected-(U7-NIC_2-Pad3)") (class "Default")
      (node (ref "U7") (pin "3") (pinfunction "NIC_2_3") (pintype "passive"))
    )
    (net (code "291") (name "unconnected-(U7-TP-Pad8)") (class "Default")
      (node (ref "U7") (pin "8") (pinfunction "TP_8") (pintype "passive"))
    )
    (net (code "292") (name "unconnected-(U7-TP_2-Pad1)") (class "Default")
      (node (ref "U7") (pin "1") (pinfunction "TP_2_1") (pintype "passive"))
    )
    (net (code "293") (name "unconnected-(U7-TRIM-Pad5)") (class "Default")
      (node (ref "U7") (pin "5") (pinfunction "TRIM_5") (pintype "passive"))
    )
    (net (code "294") (name "unconnected-(U8-BUSY-Pad67)") (class "Default")
      (node (ref "U8") (pin "67") (pinfunction "BUSY_67") (pintype "passive"))
    )
    (net (code "295") (name "unconnected-(U8-DB11{slash}SDOB-Pad56)") (class "Default")
      (node (ref "U8") (pin "56") (pinfunction "DB11/SDOB_56") (pintype "passive"))
    )
    (net (code "296") (name "unconnected-(U9-N.C-Pad1)") (class "Default")
      (node (ref "U9") (pin "1") (pinfunction "N.C_1") (pintype "no_connect"))
    )
    (net (code "297") (name "unconnected-(U15-*BUSY-Pad5)") (class "Default")
      (node (ref "U15") (pin "5") (pinfunction "*BUSY_5") (pintype "passive"))
    )
    (net (code "298") (name "unconnected-(U15-*PEC-Pad48)") (class "Default")
      (node (ref "U15") (pin "48") (pinfunction "*PEC_48") (pintype "passive"))
    )
    (net (code "299") (name "unconnected-(U15-GPIO-Pad6)") (class "Default")
      (node (ref "U15") (pin "6") (pinfunction "GPIO_6") (pintype "passive"))
    )
    (net (code "300") (name "unconnected-(U15-MON_IN0-Pad8)") (class "Default")
      (node (ref "U15") (pin "8") (pinfunction "MON_IN0_8") (pintype "passive"))
    )
    (net (code "301") (name "unconnected-(U15-MON_IN1-Pad32)") (class "Default")
      (node (ref "U15") (pin "32") (pinfunction "MON_IN1_32") (pintype "passive"))
    )
    (net (code "302") (name "unconnected-(U15-MON_OUT-Pad7)") (class "Default")
      (node (ref "U15") (pin "7") (pinfunction "MON_OUT_7") (pintype "passive"))
    )
    (net (code "303") (name "unconnected-(U15-NC-Pad26)") (class "Default")
      (node (ref "U15") (pin "26") (pinfunction "NC_26") (pintype "passive"))
    )
    (net (code "304") (name "unconnected-(U15-NC_2-Pad27)") (class "Default")
      (node (ref "U15") (pin "27") (pinfunction "NC_2_27") (pintype "passive"))
    )
    (net (code "305") (name "unconnected-(U15-NC_3-Pad30)") (class "Default")
      (node (ref "U15") (pin "30") (pinfunction "NC_3_30") (pintype "passive"))
    )
    (net (code "306") (name "unconnected-(U15-NC_4-Pad9)") (class "Default")
      (node (ref "U15") (pin "9") (pinfunction "NC_4_9") (pintype "passive"))
    )
    (net (code "307") (name "unconnected-(U15-NC_5-Pad10)") (class "Default")
      (node (ref "U15") (pin "10") (pinfunction "NC_5_10") (pintype "passive"))
    )
    (net (code "308") (name "unconnected-(U15-NC_6-Pad14)") (class "Default")
      (node (ref "U15") (pin "14") (pinfunction "NC_6_14") (pintype "passive"))
    )
    (net (code "309") (name "unconnected-(U15-NC_7-Pad24)") (class "Default")
      (node (ref "U15") (pin "24") (pinfunction "NC_7_24") (pintype "passive"))
    )
    (net (code "310") (name "unconnected-(U15-NC_8-Pad25)") (class "Default")
      (node (ref "U15") (pin "25") (pinfunction "NC_8_25") (pintype "passive"))
    )
    (net (code "311") (name "unconnected-(U15-TEMP_OUT-Pad33)") (class "Default")
      (node (ref "U15") (pin "33") (pinfunction "TEMP_OUT_33") (pintype "passive"))
    )
    (net (code "312") (name "unconnected-(U16-NIC-Pad7)") (class "Default")
      (node (ref "U16") (pin "7") (pinfunction "NIC_7") (pintype "passive"))
    )
    (net (code "313") (name "unconnected-(U16-NIC_2-Pad3)") (class "Default")
      (node (ref "U16") (pin "3") (pinfunction "NIC_2_3") (pintype "passive"))
    )
    (net (code "314") (name "unconnected-(U16-TP-Pad8)") (class "Default")
      (node (ref "U16") (pin "8") (pinfunction "TP_8") (pintype "passive"))
    )
    (net (code "315") (name "unconnected-(U16-TP_2-Pad1)") (class "Default")
      (node (ref "U16") (pin "1") (pinfunction "TP_2_1") (pintype "passive"))
    )
    (net (code "316") (name "unconnected-(U16-TRIM-Pad5)") (class "Default")
      (node (ref "U16") (pin "5") (pinfunction "TRIM_5") (pintype "passive"))
    )
    (net (code "317") (name "unconnected-(U18-*ACX-Pad17)") (class "Default")
      (node (ref "U18") (pin "17") (pinfunction "*ACX_17") (pintype "passive"))
    )
    (net (code "318") (name "unconnected-(U18-ACX-Pad16)") (class "Default")
      (node (ref "U18") (pin "16") (pinfunction "ACX_16") (pintype "passive"))
    )
    (net (code "319") (name "unconnected-(U18-VBIAS-Pad7)") (class "Default")
      (node (ref "U18") (pin "7") (pinfunction "VBIAS_7") (pintype "passive"))
    )
    (net (code "320") (name "unconnected-(U19-*BUSY-Pad5)") (class "Default")
      (node (ref "U19") (pin "5") (pinfunction "*BUSY_5") (pintype "passive"))
    )
    (net (code "321") (name "unconnected-(U19-*PEC-Pad48)") (class "Default")
      (node (ref "U19") (pin "48") (pinfunction "*PEC_48") (pintype "passive"))
    )
    (net (code "322") (name "unconnected-(U19-GPIO-Pad6)") (class "Default")
      (node (ref "U19") (pin "6") (pinfunction "GPIO_6") (pintype "passive"))
    )
    (net (code "323") (name "unconnected-(U19-MON_IN0-Pad8)") (class "Default")
      (node (ref "U19") (pin "8") (pinfunction "MON_IN0_8") (pintype "passive"))
    )
    (net (code "324") (name "unconnected-(U19-MON_IN1-Pad32)") (class "Default")
      (node (ref "U19") (pin "32") (pinfunction "MON_IN1_32") (pintype "passive"))
    )
    (net (code "325") (name "unconnected-(U19-MON_OUT-Pad7)") (class "Default")
      (node (ref "U19") (pin "7") (pinfunction "MON_OUT_7") (pintype "passive"))
    )
    (net (code "326") (name "unconnected-(U19-NC-Pad26)") (class "Default")
      (node (ref "U19") (pin "26") (pinfunction "NC_26") (pintype "passive"))
    )
    (net (code "327") (name "unconnected-(U19-NC_2-Pad27)") (class "Default")
      (node (ref "U19") (pin "27") (pinfunction "NC_2_27") (pintype "passive"))
    )
    (net (code "328") (name "unconnected-(U19-NC_3-Pad30)") (class "Default")
      (node (ref "U19") (pin "30") (pinfunction "NC_3_30") (pintype "passive"))
    )
    (net (code "329") (name "unconnected-(U19-NC_4-Pad9)") (class "Default")
      (node (ref "U19") (pin "9") (pinfunction "NC_4_9") (pintype "passive"))
    )
    (net (code "330") (name "unconnected-(U19-NC_5-Pad10)") (class "Default")
      (node (ref "U19") (pin "10") (pinfunction "NC_5_10") (pintype "passive"))
    )
    (net (code "331") (name "unconnected-(U19-NC_6-Pad14)") (class "Default")
      (node (ref "U19") (pin "14") (pinfunction "NC_6_14") (pintype "passive"))
    )
    (net (code "332") (name "unconnected-(U19-NC_7-Pad24)") (class "Default")
      (node (ref "U19") (pin "24") (pinfunction "NC_7_24") (pintype "passive"))
    )
    (net (code "333") (name "unconnected-(U19-NC_8-Pad25)") (class "Default")
      (node (ref "U19") (pin "25") (pinfunction "NC_8_25") (pintype "passive"))
    )
    (net (code "334") (name "unconnected-(U19-TEMP_OUT-Pad33)") (class "Default")
      (node (ref "U19") (pin "33") (pinfunction "TEMP_OUT_33") (pintype "passive"))
    )
    (net (code "335") (name "unconnected-(U20-NIC-Pad7)") (class "Default")
      (node (ref "U20") (pin "7") (pinfunction "NIC_7") (pintype "passive"))
    )
    (net (code "336") (name "unconnected-(U20-NIC_2-Pad3)") (class "Default")
      (node (ref "U20") (pin "3") (pinfunction "NIC_2_3") (pintype "passive"))
    )
    (net (code "337") (name "unconnected-(U20-TP-Pad8)") (class "Default")
      (node (ref "U20") (pin "8") (pinfunction "TP_8") (pintype "passive"))
    )
    (net (code "338") (name "unconnected-(U20-TP_2-Pad1)") (class "Default")
      (node (ref "U20") (pin "1") (pinfunction "TP_2_1") (pintype "passive"))
    )
    (net (code "339") (name "unconnected-(U20-TRIM-Pad5)") (class "Default")
      (node (ref "U20") (pin "5") (pinfunction "TRIM_5") (pintype "passive"))
    )
    (net (code "340") (name "unconnected-(U21-*ACX-Pad17)") (class "Default")
      (node (ref "U21") (pin "17") (pinfunction "*ACX_17") (pintype "passive"))
    )
    (net (code "341") (name "unconnected-(U21-ACX-Pad16)") (class "Default")
      (node (ref "U21") (pin "16") (pinfunction "ACX_16") (pintype "passive"))
    )
    (net (code "342") (name "unconnected-(U21-VBIAS-Pad7)") (class "Default")
      (node (ref "U21") (pin "7") (pinfunction "VBIAS_7") (pintype "passive"))
    )
    (net (code "343") (name "unconnected-(U22-BOOT0-Pad60)") (class "Default")
      (node (ref "U22") (pin "60") (pinfunction "BOOT0_60") (pintype "passive"))
    )
    (net (code "344") (name "unconnected-(U22-PA3-Pad17)") (class "Default")
      (node (ref "U22") (pin "17") (pinfunction "PA3_17") (pintype "bidirectional"))
    )
    (net (code "345") (name "unconnected-(U22-PA4-Pad20)") (class "Default")
      (node (ref "U22") (pin "20") (pinfunction "PA4_20") (pintype "bidirectional"))
    )
    (net (code "346") (name "unconnected-(U22-PB6-Pad58)") (class "Default")
      (node (ref "U22") (pin "58") (pinfunction "PB6_58") (pintype "bidirectional"))
    )
    (net (code "347") (name "unconnected-(U22-PB8-Pad61)") (class "Default")
      (node (ref "U22") (pin "61") (pinfunction "PB8_61") (pintype "bidirectional"))
    )
    (net (code "348") (name "unconnected-(U22-PB9-Pad62)") (class "Default")
      (node (ref "U22") (pin "62") (pinfunction "PB9_62") (pintype "bidirectional"))
    )
    (net (code "349") (name "unconnected-(U22-PB10-Pad29)") (class "Default")
      (node (ref "U22") (pin "29") (pinfunction "PB10_29") (pintype "bidirectional"))
    )
    (net (code "350") (name "unconnected-(U22-PB11-Pad30)") (class "Default")
      (node (ref "U22") (pin "30") (pinfunction "PB11_30") (pintype "bidirectional"))
    )
    (net (code "351") (name "unconnected-(U22-PB12-Pad33)") (class "Default")
      (node (ref "U22") (pin "33") (pinfunction "PB12_33") (pintype "bidirectional"))
    )
    (net (code "352") (name "unconnected-(U22-PB13-Pad34)") (class "Default")
      (node (ref "U22") (pin "34") (pinfunction "PB13_34") (pintype "bidirectional"))
    )
    (net (code "353") (name "unconnected-(U22-PB14-Pad35)") (class "Default")
      (node (ref "U22") (pin "35") (pinfunction "PB14_35") (pintype "bidirectional"))
    )
    (net (code "354") (name "unconnected-(U22-PB15-Pad36)") (class "Default")
      (node (ref "U22") (pin "36") (pinfunction "PB15_36") (pintype "bidirectional"))
    )
    (net (code "355") (name "unconnected-(U22-PC0-Pad8)") (class "Default")
      (node (ref "U22") (pin "8") (pinfunction "PC0_8") (pintype "bidirectional"))
    )
    (net (code "356") (name "unconnected-(U22-PC1-Pad9)") (class "Default")
      (node (ref "U22") (pin "9") (pinfunction "PC1_9") (pintype "bidirectional"))
    )
    (net (code "357") (name "unconnected-(U22-PC2-Pad10)") (class "Default")
      (node (ref "U22") (pin "10") (pinfunction "PC2_10") (pintype "bidirectional"))
    )
    (net (code "358") (name "unconnected-(U22-PC3-Pad11)") (class "Default")
      (node (ref "U22") (pin "11") (pinfunction "PC3_11") (pintype "bidirectional"))
    )
    (net (code "359") (name "unconnected-(U22-PC6-Pad37)") (class "Default")
      (node (ref "U22") (pin "37") (pinfunction "PC6_37") (pintype "bidirectional"))
    )
    (net (code "360") (name "unconnected-(U22-PC10-Pad51)") (class "Default")
      (node (ref "U22") (pin "51") (pinfunction "PC10_51") (pintype "bidirectional"))
    )
    (net (code "361") (name "unconnected-(U22-PC11-Pad52)") (class "Default")
      (node (ref "U22") (pin "52") (pinfunction "PC11_52") (pintype "bidirectional"))
    )
    (net (code "362") (name "unconnected-(U22-PC12-Pad53)") (class "Default")
      (node (ref "U22") (pin "53") (pinfunction "PC12_53") (pintype "bidirectional"))
    )
    (net (code "363") (name "unconnected-(U22-PC13-TAMPER-RTC-Pad2)") (class "Default")
      (node (ref "U22") (pin "2") (pinfunction "PC13-TAMPER-RTC_2") (pintype "input"))
    )
    (net (code "364") (name "unconnected-(U22-PC14-OSC32_IN-Pad3)") (class "Default")
      (node (ref "U22") (pin "3") (pinfunction "PC14-OSC32_IN_3") (pintype "input"))
    )
    (net (code "365") (name "unconnected-(U22-PC15-OSC32_OUT-Pad4)") (class "Default")
      (node (ref "U22") (pin "4") (pinfunction "PC15-OSC32_OUT_4") (pintype "output"))
    )
    (net (code "366") (name "unconnected-(U22-PD2-Pad54)") (class "Default")
      (node (ref "U22") (pin "54") (pinfunction "PD2_54") (pintype "bidirectional"))
    )
    (net (code "367") (name "unconnected-(U23-*ACX-Pad17)") (class "Default")
      (node (ref "U23") (pin "17") (pinfunction "*ACX_17") (pintype "passive"))
    )
    (net (code "368") (name "unconnected-(U23-ACX-Pad16)") (class "Default")
      (node (ref "U23") (pin "16") (pinfunction "ACX_16") (pintype "passive"))
    )
    (net (code "369") (name "unconnected-(U23-VBIAS-Pad7)") (class "Default")
      (node (ref "U23") (pin "7") (pinfunction "VBIAS_7") (pintype "passive"))
    )
    (net (code "370") (name "unconnected-(U24-*ACX-Pad17)") (class "Default")
      (node (ref "U24") (pin "17") (pinfunction "*ACX_17") (pintype "passive"))
    )
    (net (code "371") (name "unconnected-(U24-ACX-Pad16)") (class "Default")
      (node (ref "U24") (pin "16") (pinfunction "ACX_16") (pintype "passive"))
    )
    (net (code "372") (name "unconnected-(U24-VBIAS-Pad7)") (class "Default")
      (node (ref "U24") (pin "7") (pinfunction "VBIAS_7") (pintype "passive"))
    )
    (net (code "373") (name "unconnected-(U25-*ACX-Pad17)") (class "Default")
      (node (ref "U25") (pin "17") (pinfunction "*ACX_17") (pintype "passive"))
    )
    (net (code "374") (name "unconnected-(U25-ACX-Pad16)") (class "Default")
      (node (ref "U25") (pin "16") (pinfunction "ACX_16") (pintype "passive"))
    )
    (net (code "375") (name "unconnected-(U25-VBIAS-Pad7)") (class "Default")
      (node (ref "U25") (pin "7") (pinfunction "VBIAS_7") (pintype "passive"))
    )
    (net (code "376") (name "unconnected-(U26-*ACX-Pad17)") (class "Default")
      (node (ref "U26") (pin "17") (pinfunction "*ACX_17") (pintype "passive"))
    )
    (net (code "377") (name "unconnected-(U26-ACX-Pad16)") (class "Default")
      (node (ref "U26") (pin "16") (pinfunction "ACX_16") (pintype "passive"))
    )
    (net (code "378") (name "unconnected-(U26-VBIAS-Pad7)") (class "Default")
      (node (ref "U26") (pin "7") (pinfunction "VBIAS_7") (pintype "passive"))
    )
    (net (code "379") (name "unconnected-(U27-*ACX-Pad17)") (class "Default")
      (node (ref "U27") (pin "17") (pinfunction "*ACX_17") (pintype "passive"))
    )
    (net (code "380") (name "unconnected-(U27-ACX-Pad16)") (class "Default")
      (node (ref "U27") (pin "16") (pinfunction "ACX_16") (pintype "passive"))
    )
    (net (code "381") (name "unconnected-(U27-VBIAS-Pad7)") (class "Default")
      (node (ref "U27") (pin "7") (pinfunction "VBIAS_7") (pintype "passive"))
    )
    (net (code "382") (name "unconnected-(U28-*ACX-Pad17)") (class "Default")
      (node (ref "U28") (pin "17") (pinfunction "*ACX_17") (pintype "passive"))
    )
    (net (code "383") (name "unconnected-(U28-ACX-Pad16)") (class "Default")
      (node (ref "U28") (pin "16") (pinfunction "ACX_16") (pintype "passive"))
    )
    (net (code "384") (name "unconnected-(U28-MCLK_OUT-Pad3)") (class "Default")
      (node (ref "U28") (pin "3") (pinfunction "MCLK_OUT_3") (pintype "passive"))
    )
    (net (code "385") (name "unconnected-(U28-VBIAS-Pad7)") (class "Default")
      (node (ref "U28") (pin "7") (pinfunction "VBIAS_7") (pintype "passive"))
    )
    (net (code "386") (name "unconnected-(U38-*ACX-Pad17)") (class "Default")
      (node (ref "U38") (pin "17") (pinfunction "*ACX_17") (pintype "passive"))
    )
    (net (code "387") (name "unconnected-(U38-ACX-Pad16)") (class "Default")
      (node (ref "U38") (pin "16") (pinfunction "ACX_16") (pintype "passive"))
    )
    (net (code "388") (name "unconnected-(U38-VBIAS-Pad7)") (class "Default")
      (node (ref "U38") (pin "7") (pinfunction "VBIAS_7") (pintype "passive"))
    )
    (net (code "389") (name "unconnected-(U39-*ACX-Pad17)") (class "Default")
      (node (ref "U39") (pin "17") (pinfunction "*ACX_17") (pintype "passive"))
    )
    (net (code "390") (name "unconnected-(U39-ACX-Pad16)") (class "Default")
      (node (ref "U39") (pin "16") (pinfunction "ACX_16") (pintype "passive"))
    )
    (net (code "391") (name "unconnected-(U39-VBIAS-Pad7)") (class "Default")
      (node (ref "U39") (pin "7") (pinfunction "VBIAS_7") (pintype "passive"))
    )
    (net (code "392") (name "unconnected-(U40-BOOT0-Pad60)") (class "Default")
      (node (ref "U40") (pin "60") (pinfunction "BOOT0_60") (pintype "passive"))
    )
    (net (code "393") (name "unconnected-(U40-PA3-Pad17)") (class "Default")
      (node (ref "U40") (pin "17") (pinfunction "PA3_17") (pintype "bidirectional"))
    )
    (net (code "394") (name "unconnected-(U40-PA4-Pad20)") (class "Default")
      (node (ref "U40") (pin "20") (pinfunction "PA4_20") (pintype "bidirectional"))
    )
    (net (code "395") (name "unconnected-(U40-PB6-Pad58)") (class "Default")
      (node (ref "U40") (pin "58") (pinfunction "PB6_58") (pintype "bidirectional"))
    )
    (net (code "396") (name "unconnected-(U40-PB8-Pad61)") (class "Default")
      (node (ref "U40") (pin "61") (pinfunction "PB8_61") (pintype "bidirectional"))
    )
    (net (code "397") (name "unconnected-(U40-PB9-Pad62)") (class "Default")
      (node (ref "U40") (pin "62") (pinfunction "PB9_62") (pintype "bidirectional"))
    )
    (net (code "398") (name "unconnected-(U40-PB10-Pad29)") (class "Default")
      (node (ref "U40") (pin "29") (pinfunction "PB10_29") (pintype "bidirectional"))
    )
    (net (code "399") (name "unconnected-(U40-PB11-Pad30)") (class "Default")
      (node (ref "U40") (pin "30") (pinfunction "PB11_30") (pintype "bidirectional"))
    )
    (net (code "400") (name "unconnected-(U40-PB12-Pad33)") (class "Default")
      (node (ref "U40") (pin "33") (pinfunction "PB12_33") (pintype "bidirectional"))
    )
    (net (code "401") (name "unconnected-(U40-PB13-Pad34)") (class "Default")
      (node (ref "U40") (pin "34") (pinfunction "PB13_34") (pintype "bidirectional"))
    )
    (net (code "402") (name "unconnected-(U40-PB14-Pad35)") (class "Default")
      (node (ref "U40") (pin "35") (pinfunction "PB14_35") (pintype "bidirectional"))
    )
    (net (code "403") (name "unconnected-(U40-PB15-Pad36)") (class "Default")
      (node (ref "U40") (pin "36") (pinfunction "PB15_36") (pintype "bidirectional"))
    )
    (net (code "404") (name "unconnected-(U40-PC0-Pad8)") (class "Default")
      (node (ref "U40") (pin "8") (pinfunction "PC0_8") (pintype "bidirectional"))
    )
    (net (code "405") (name "unconnected-(U40-PC1-Pad9)") (class "Default")
      (node (ref "U40") (pin "9") (pinfunction "PC1_9") (pintype "bidirectional"))
    )
    (net (code "406") (name "unconnected-(U40-PC2-Pad10)") (class "Default")
      (node (ref "U40") (pin "10") (pinfunction "PC2_10") (pintype "bidirectional"))
    )
    (net (code "407") (name "unconnected-(U40-PC3-Pad11)") (class "Default")
      (node (ref "U40") (pin "11") (pinfunction "PC3_11") (pintype "bidirectional"))
    )
    (net (code "408") (name "unconnected-(U40-PC6-Pad37)") (class "Default")
      (node (ref "U40") (pin "37") (pinfunction "PC6_37") (pintype "bidirectional"))
    )
    (net (code "409") (name "unconnected-(U40-PC10-Pad51)") (class "Default")
      (node (ref "U40") (pin "51") (pinfunction "PC10_51") (pintype "bidirectional"))
    )
    (net (code "410") (name "unconnected-(U40-PC11-Pad52)") (class "Default")
      (node (ref "U40") (pin "52") (pinfunction "PC11_52") (pintype "bidirectional"))
    )
    (net (code "411") (name "unconnected-(U40-PC12-Pad53)") (class "Default")
      (node (ref "U40") (pin "53") (pinfunction "PC12_53") (pintype "bidirectional"))
    )
    (net (code "412") (name "unconnected-(U40-PC13-TAMPER-RTC-Pad2)") (class "Default")
      (node (ref "U40") (pin "2") (pinfunction "PC13-TAMPER-RTC_2") (pintype "input"))
    )
    (net (code "413") (name "unconnected-(U40-PC14-OSC32_IN-Pad3)") (class "Default")
      (node (ref "U40") (pin "3") (pinfunction "PC14-OSC32_IN_3") (pintype "input"))
    )
    (net (code "414") (name "unconnected-(U40-PC15-OSC32_OUT-Pad4)") (class "Default")
      (node (ref "U40") (pin "4") (pinfunction "PC15-OSC32_OUT_4") (pintype "output"))
    )
    (net (code "415") (name "unconnected-(U40-PD2-Pad54)") (class "Default")
      (node (ref "U40") (pin "54") (pinfunction "PD2_54") (pintype "bidirectional"))
    )
    (net (code "416") (name "unconnected-(U41-*ACX-Pad17)") (class "Default")
      (node (ref "U41") (pin "17") (pinfunction "*ACX_17") (pintype "passive"))
    )
    (net (code "417") (name "unconnected-(U41-ACX-Pad16)") (class "Default")
      (node (ref "U41") (pin "16") (pinfunction "ACX_16") (pintype "passive"))
    )
    (net (code "418") (name "unconnected-(U41-VBIAS-Pad7)") (class "Default")
      (node (ref "U41") (pin "7") (pinfunction "VBIAS_7") (pintype "passive"))
    )
    (net (code "419") (name "unconnected-(U42-*ACX-Pad17)") (class "Default")
      (node (ref "U42") (pin "17") (pinfunction "*ACX_17") (pintype "passive"))
    )
    (net (code "420") (name "unconnected-(U42-ACX-Pad16)") (class "Default")
      (node (ref "U42") (pin "16") (pinfunction "ACX_16") (pintype "passive"))
    )
    (net (code "421") (name "unconnected-(U42-VBIAS-Pad7)") (class "Default")
      (node (ref "U42") (pin "7") (pinfunction "VBIAS_7") (pintype "passive"))
    )
    (net (code "422") (name "unconnected-(U43-*ACX-Pad17)") (class "Default")
      (node (ref "U43") (pin "17") (pinfunction "*ACX_17") (pintype "passive"))
    )
    (net (code "423") (name "unconnected-(U43-ACX-Pad16)") (class "Default")
      (node (ref "U43") (pin "16") (pinfunction "ACX_16") (pintype "passive"))
    )
    (net (code "424") (name "unconnected-(U43-VBIAS-Pad7)") (class "Default")
      (node (ref "U43") (pin "7") (pinfunction "VBIAS_7") (pintype "passive"))
    )
    (net (code "425") (name "unconnected-(U44-*ACX-Pad17)") (class "Default")
      (node (ref "U44") (pin "17") (pinfunction "*ACX_17") (pintype "passive"))
    )
    (net (code "426") (name "unconnected-(U44-ACX-Pad16)") (class "Default")
      (node (ref "U44") (pin "16") (pinfunction "ACX_16") (pintype "passive"))
    )
    (net (code "427") (name "unconnected-(U44-VBIAS-Pad7)") (class "Default")
      (node (ref "U44") (pin "7") (pinfunction "VBIAS_7") (pintype "passive"))
    )
    (net (code "428") (name "unconnected-(U45-*ACX-Pad17)") (class "Default")
      (node (ref "U45") (pin "17") (pinfunction "*ACX_17") (pintype "passive"))
    )
    (net (code "429") (name "unconnected-(U45-ACX-Pad16)") (class "Default")
      (node (ref "U45") (pin "16") (pinfunction "ACX_16") (pintype "passive"))
    )
    (net (code "430") (name "unconnected-(U45-VBIAS-Pad7)") (class "Default")
      (node (ref "U45") (pin "7") (pinfunction "VBIAS_7") (pintype "passive"))
    )
    (net (code "431") (name "unconnected-(U46-*ACX-Pad17)") (class "Default")
      (node (ref "U46") (pin "17") (pinfunction "*ACX_17") (pintype "passive"))
    )
    (net (code "432") (name "unconnected-(U46-ACX-Pad16)") (class "Default")
      (node (ref "U46") (pin "16") (pinfunction "ACX_16") (pintype "passive"))
    )
    (net (code "433") (name "unconnected-(U46-MCLK_OUT-Pad3)") (class "Default")
      (node (ref "U46") (pin "3") (pinfunction "MCLK_OUT_3") (pintype "passive"))
    )
    (net (code "434") (name "unconnected-(U46-VBIAS-Pad7)") (class "Default")
      (node (ref "U46") (pin "7") (pinfunction "VBIAS_7") (pintype "passive"))
    )
    (net (code "435") (name "unconnected-(X1A-S-Pad1)") (class "Default")
      (node (ref "X1") (pin "1") (pinfunction "S_1") (pintype "passive"))
    )
    (net (code "436") (name "unconnected-(Y3-EN-Pad1)") (class "Default")
      (node (ref "Y3") (pin "1") (pinfunction "EN_1") (pintype "bidirectional"))
    )
    (net (code "437") (name "unconnected-(Y7-EN-Pad1)") (class "Default")
      (node (ref "Y7") (pin "1") (pinfunction "EN_1") (pintype "bidirectional"))
    )
  )
)
